# SPU_Rev_2_1.net
KiCad netlist of a schematic drawn in EAGLE
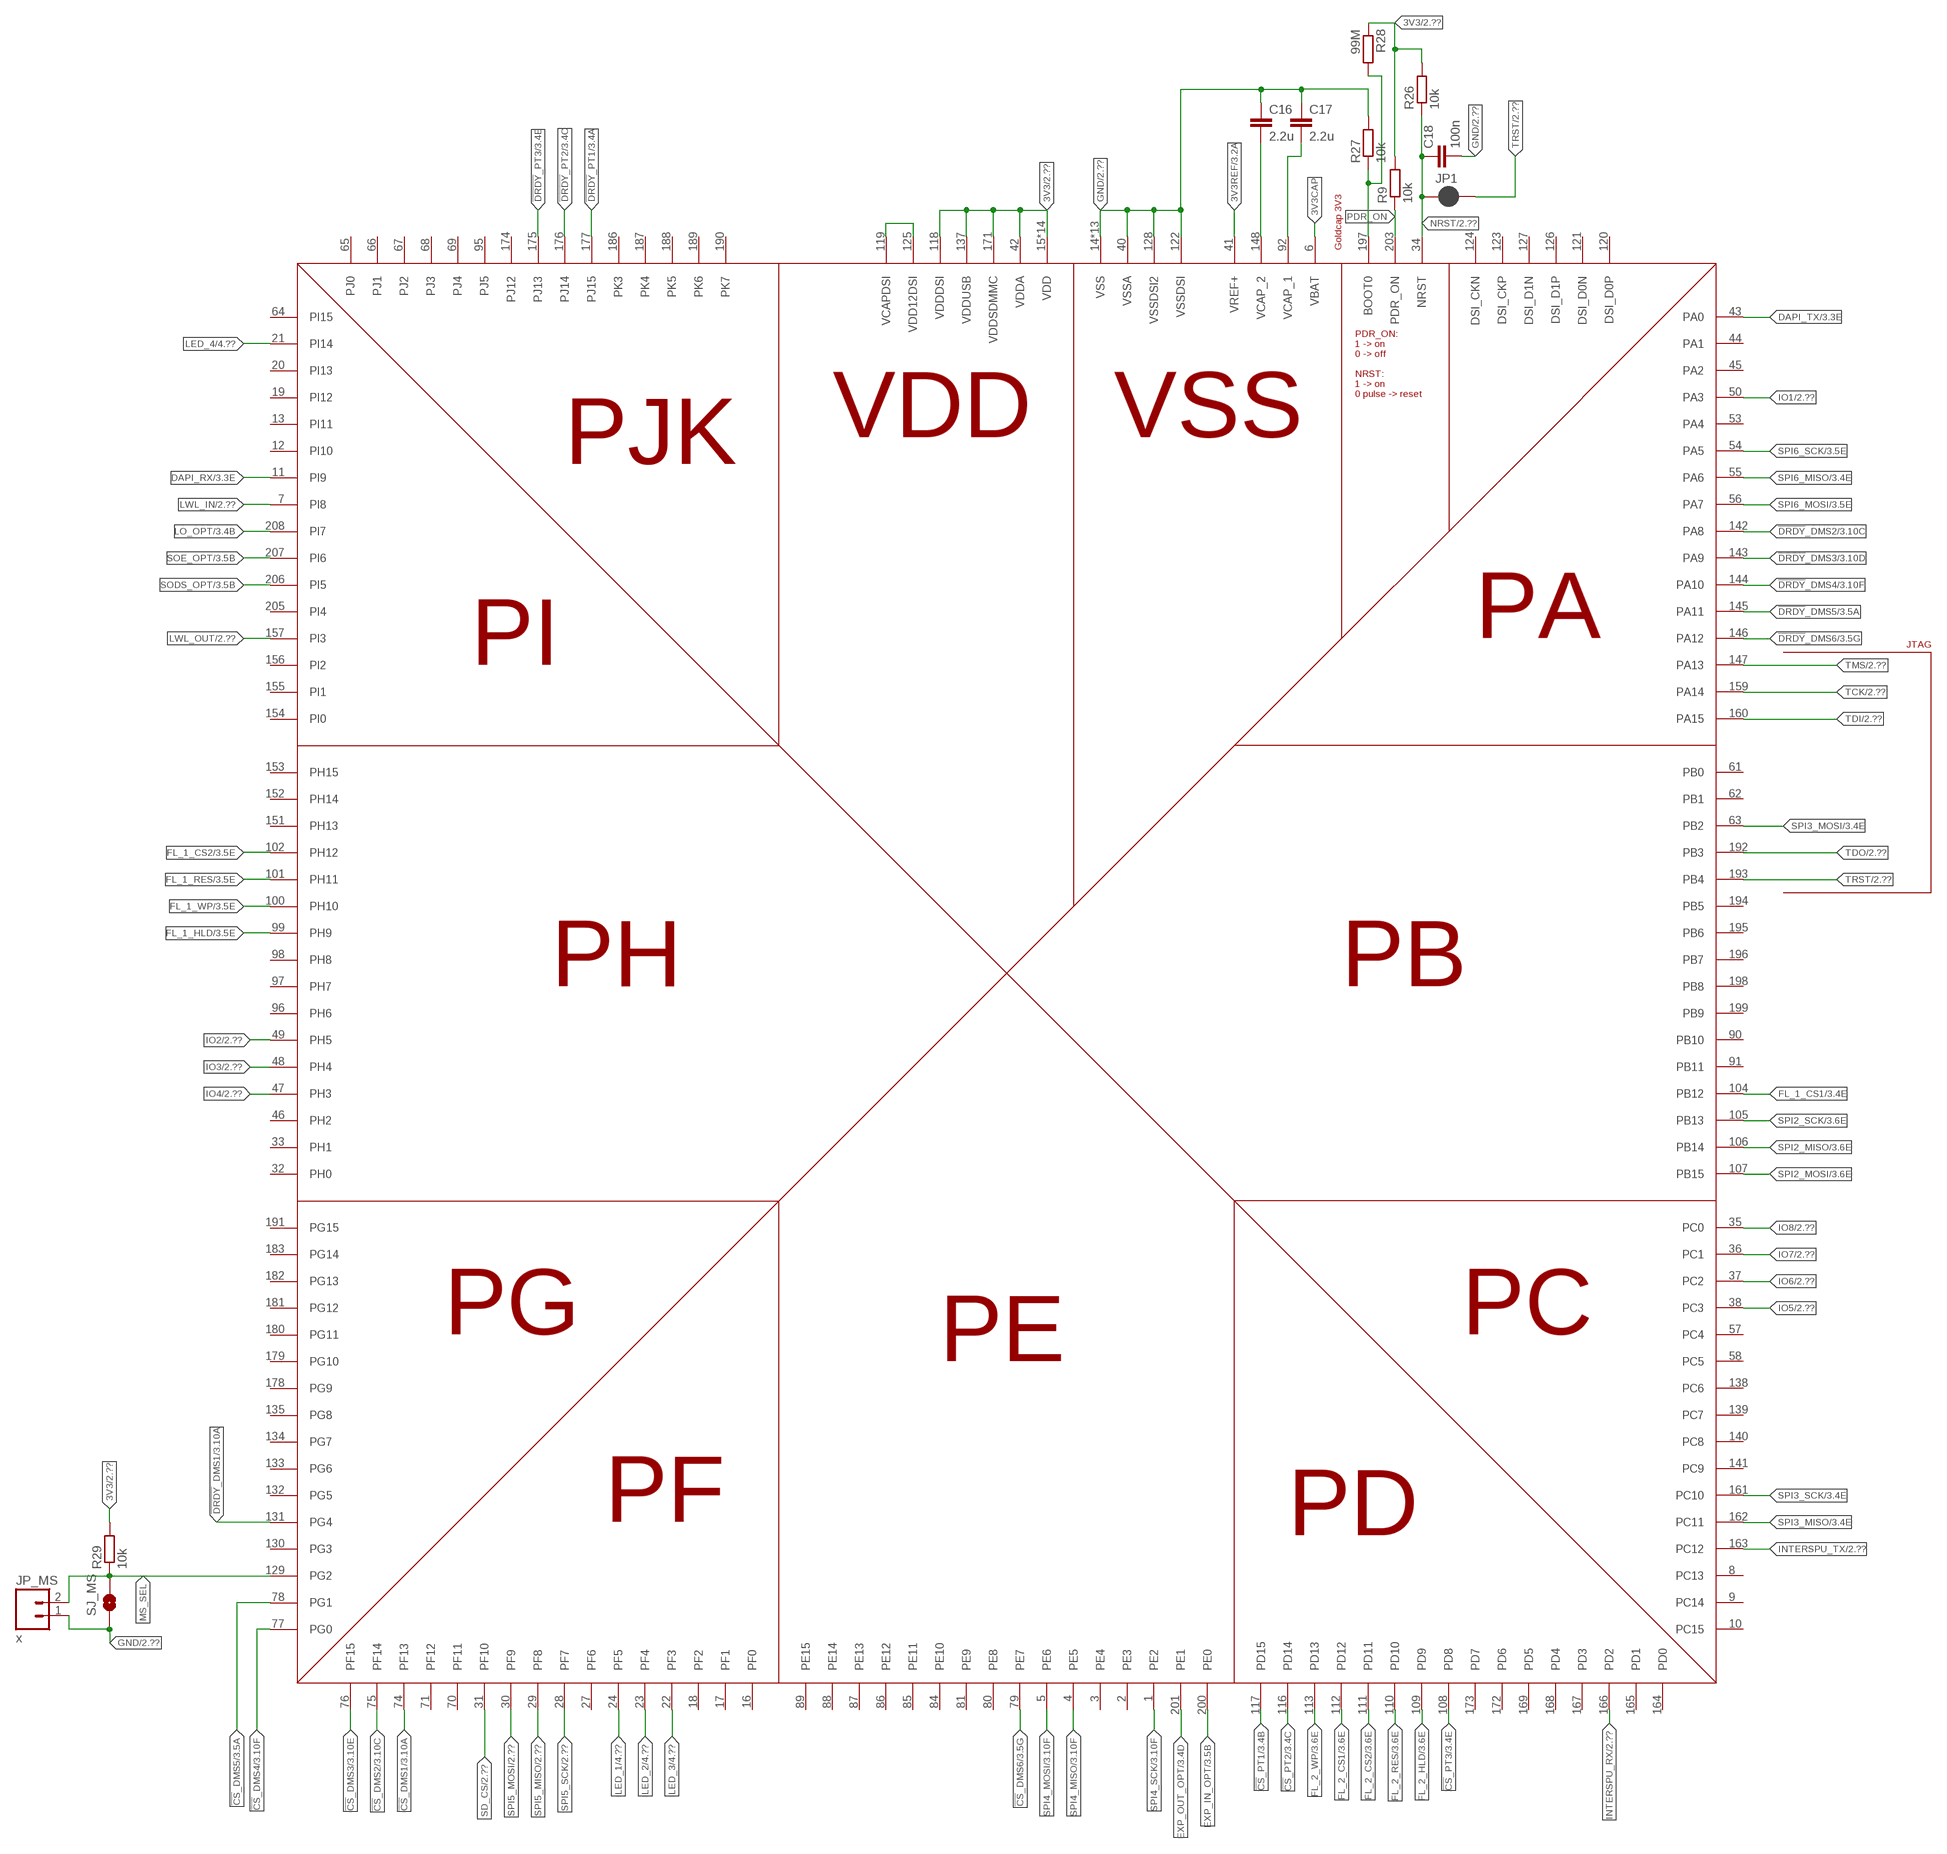
[diagram p0: schematic, sheet 1]
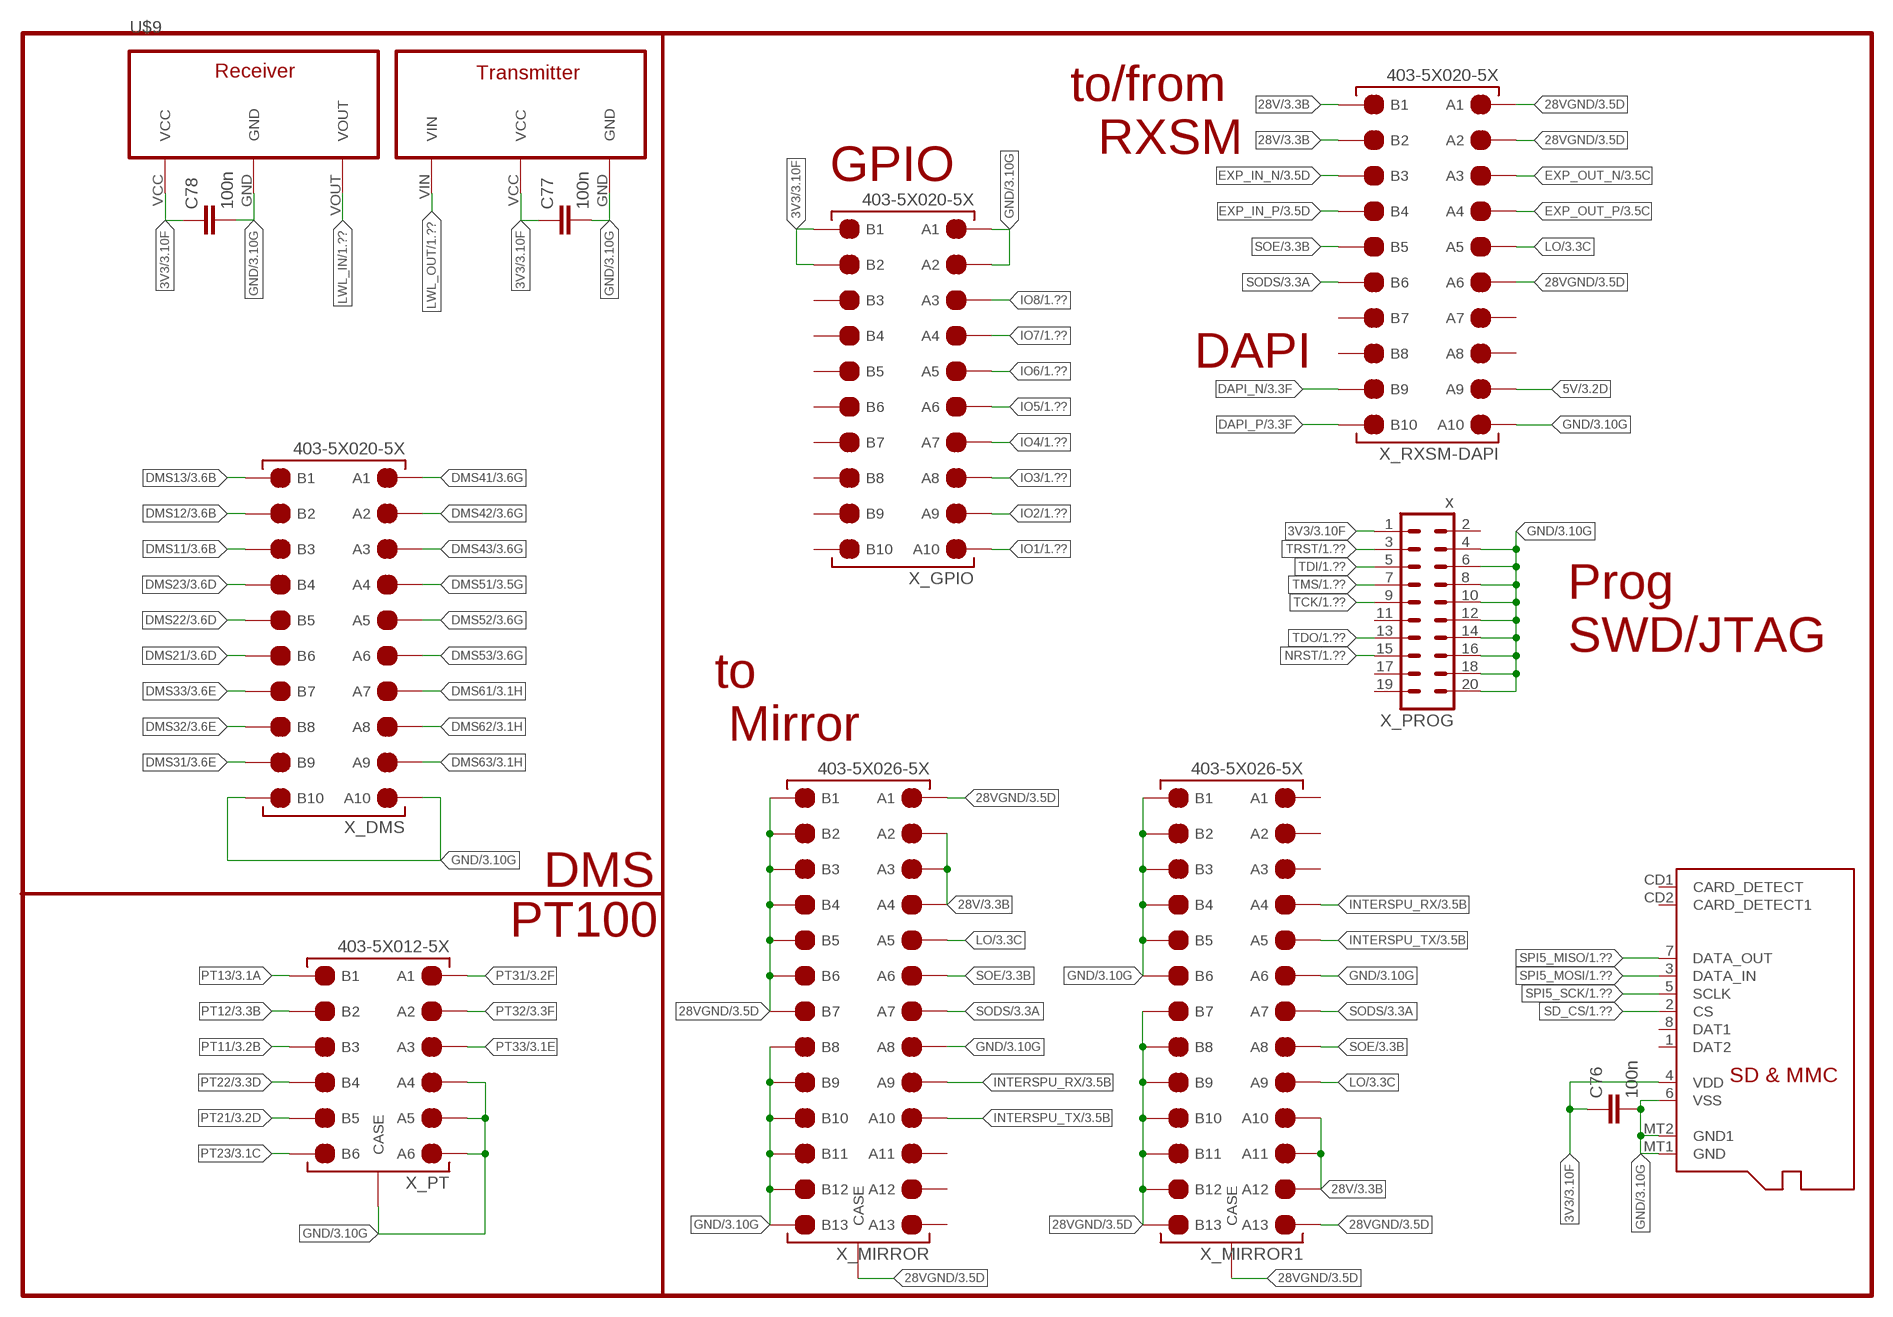
[diagram p1: schematic, sheet 2]
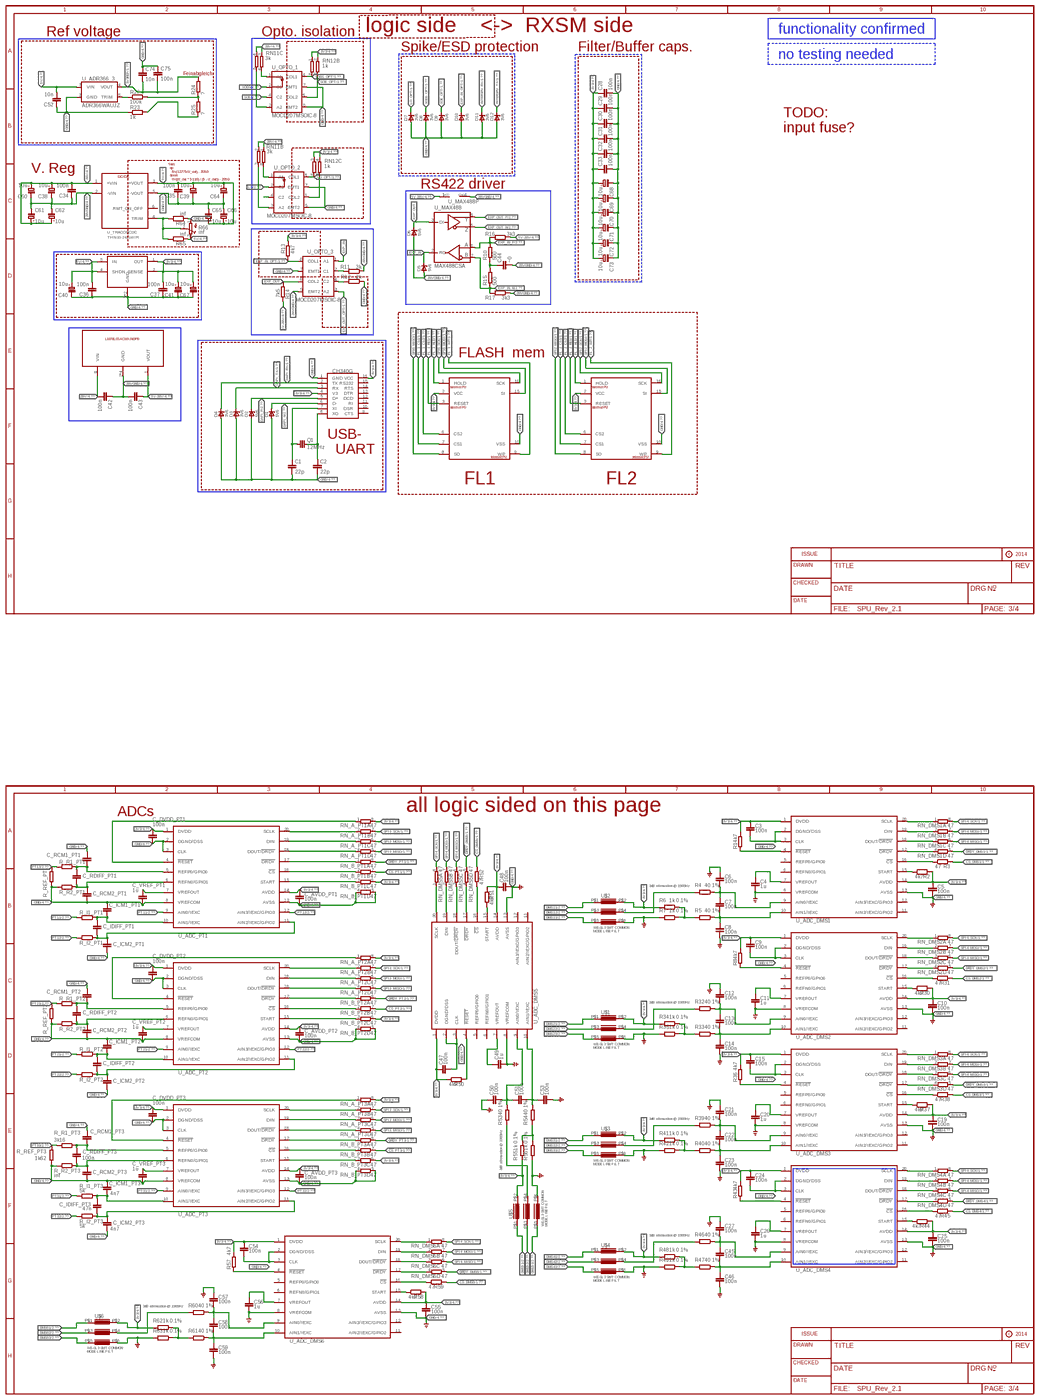
[diagram p2: schematic, sheet 3, overview]
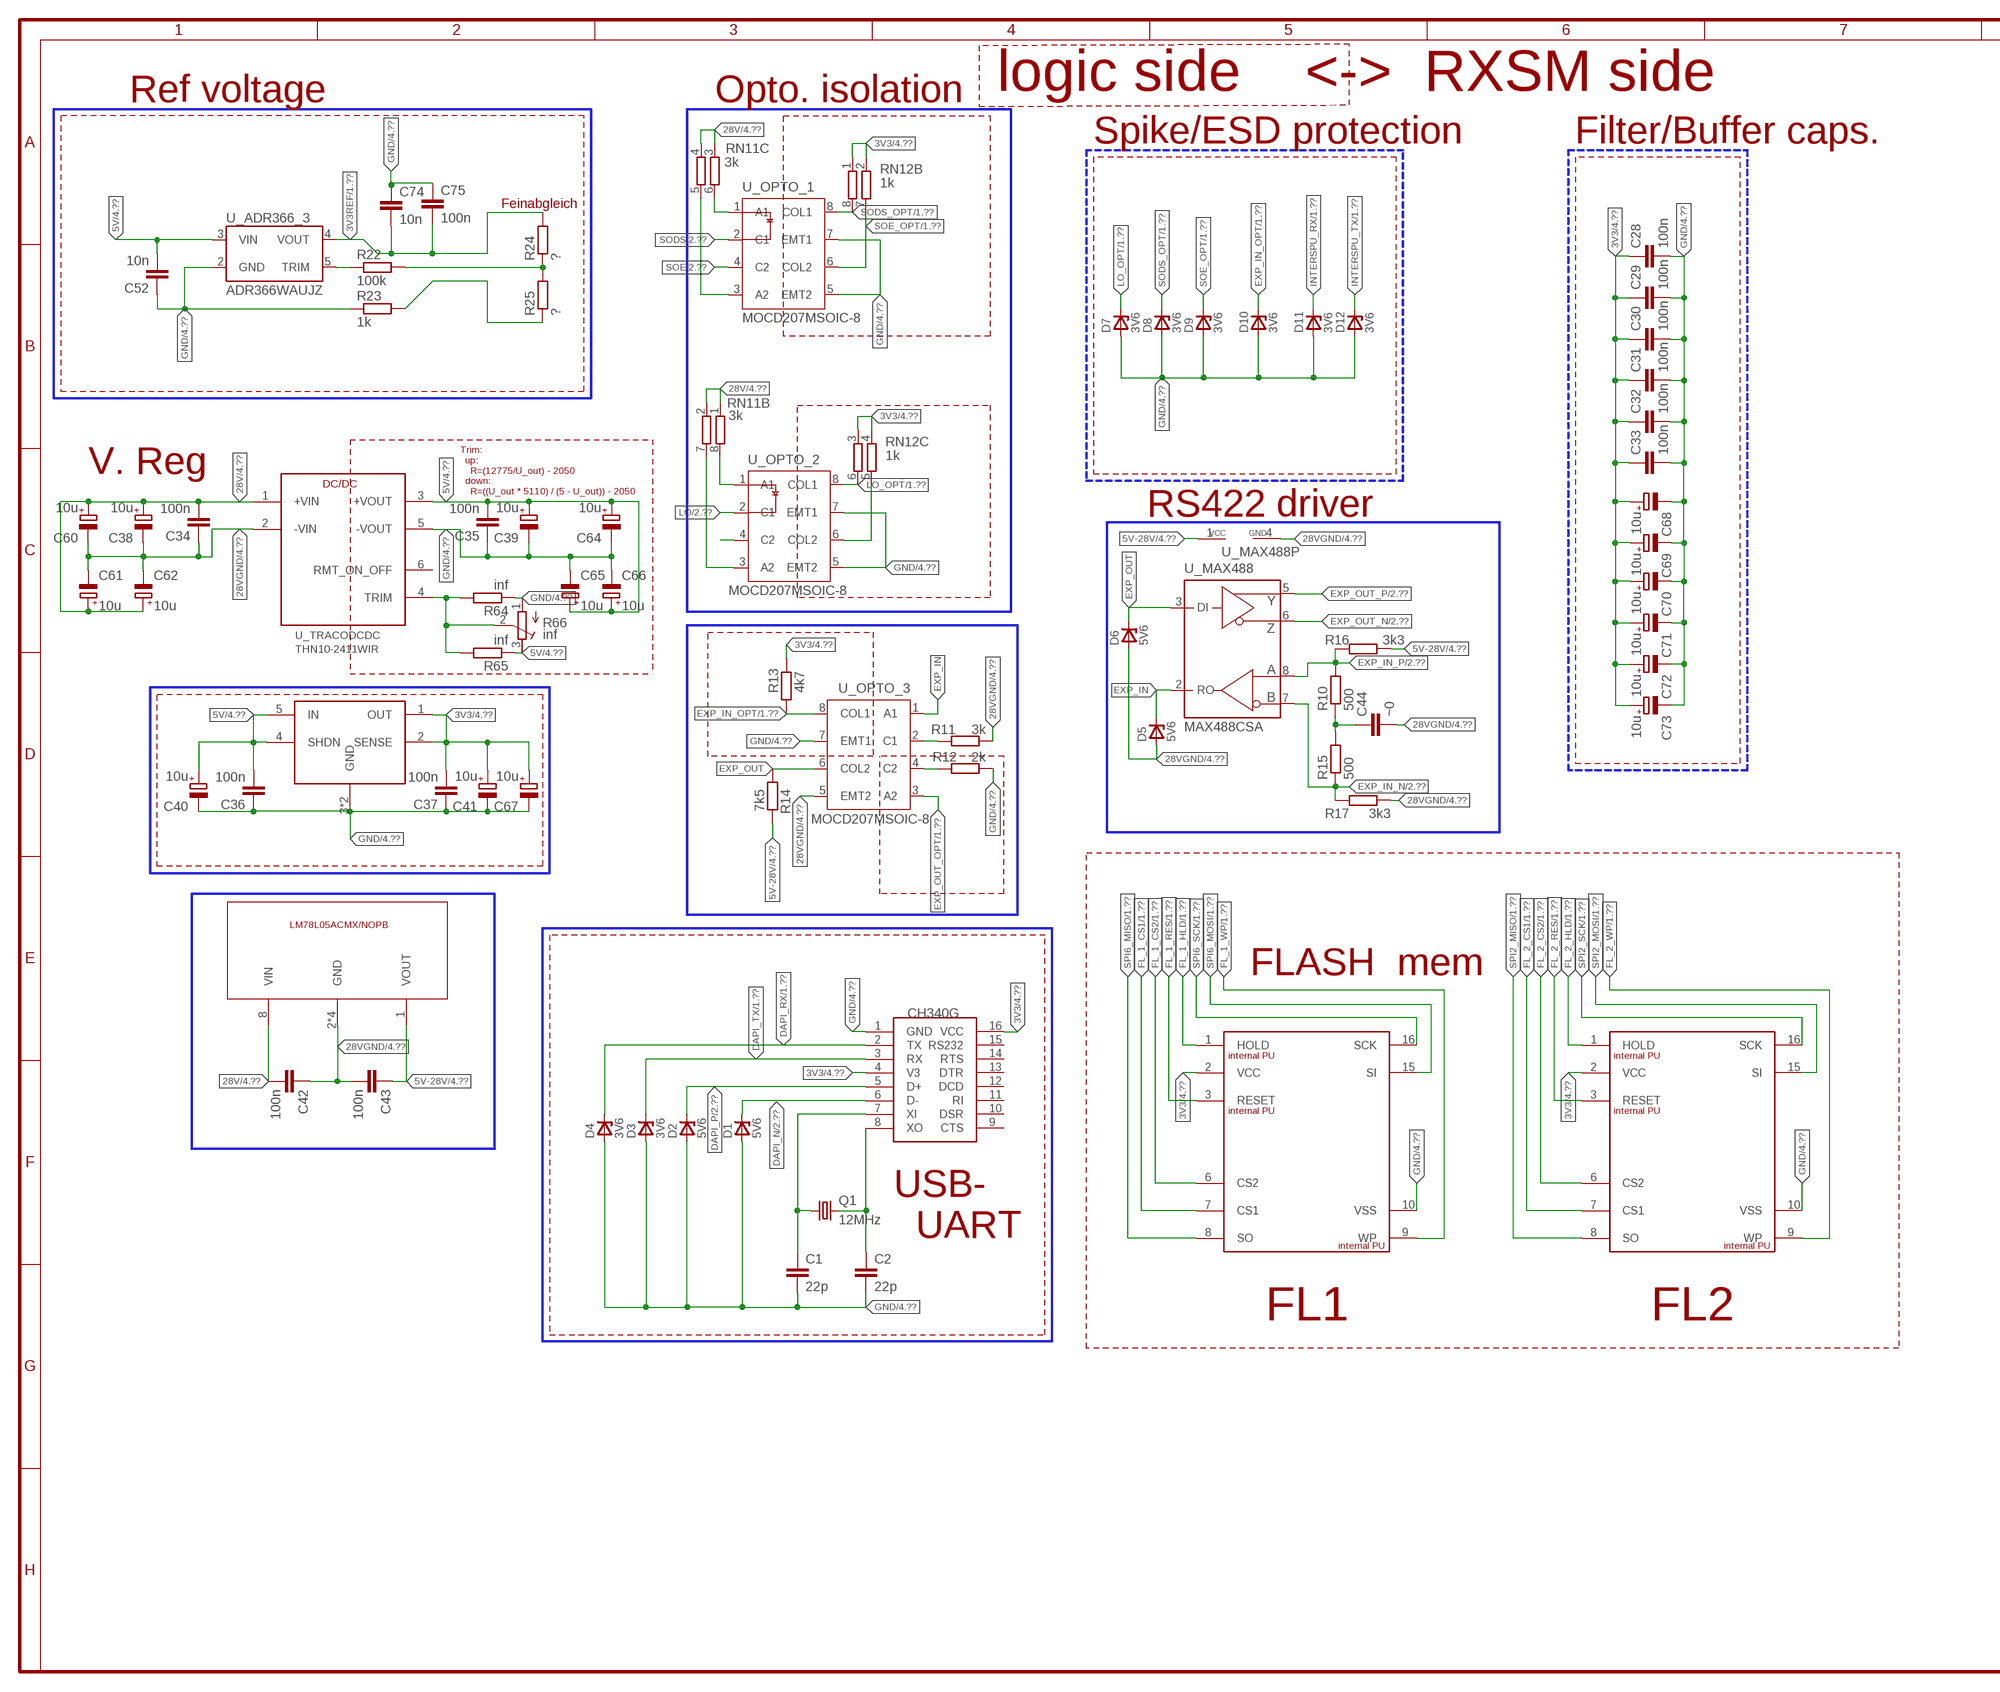
[diagram p3: schematic, sheet 3, part 1 of 4]
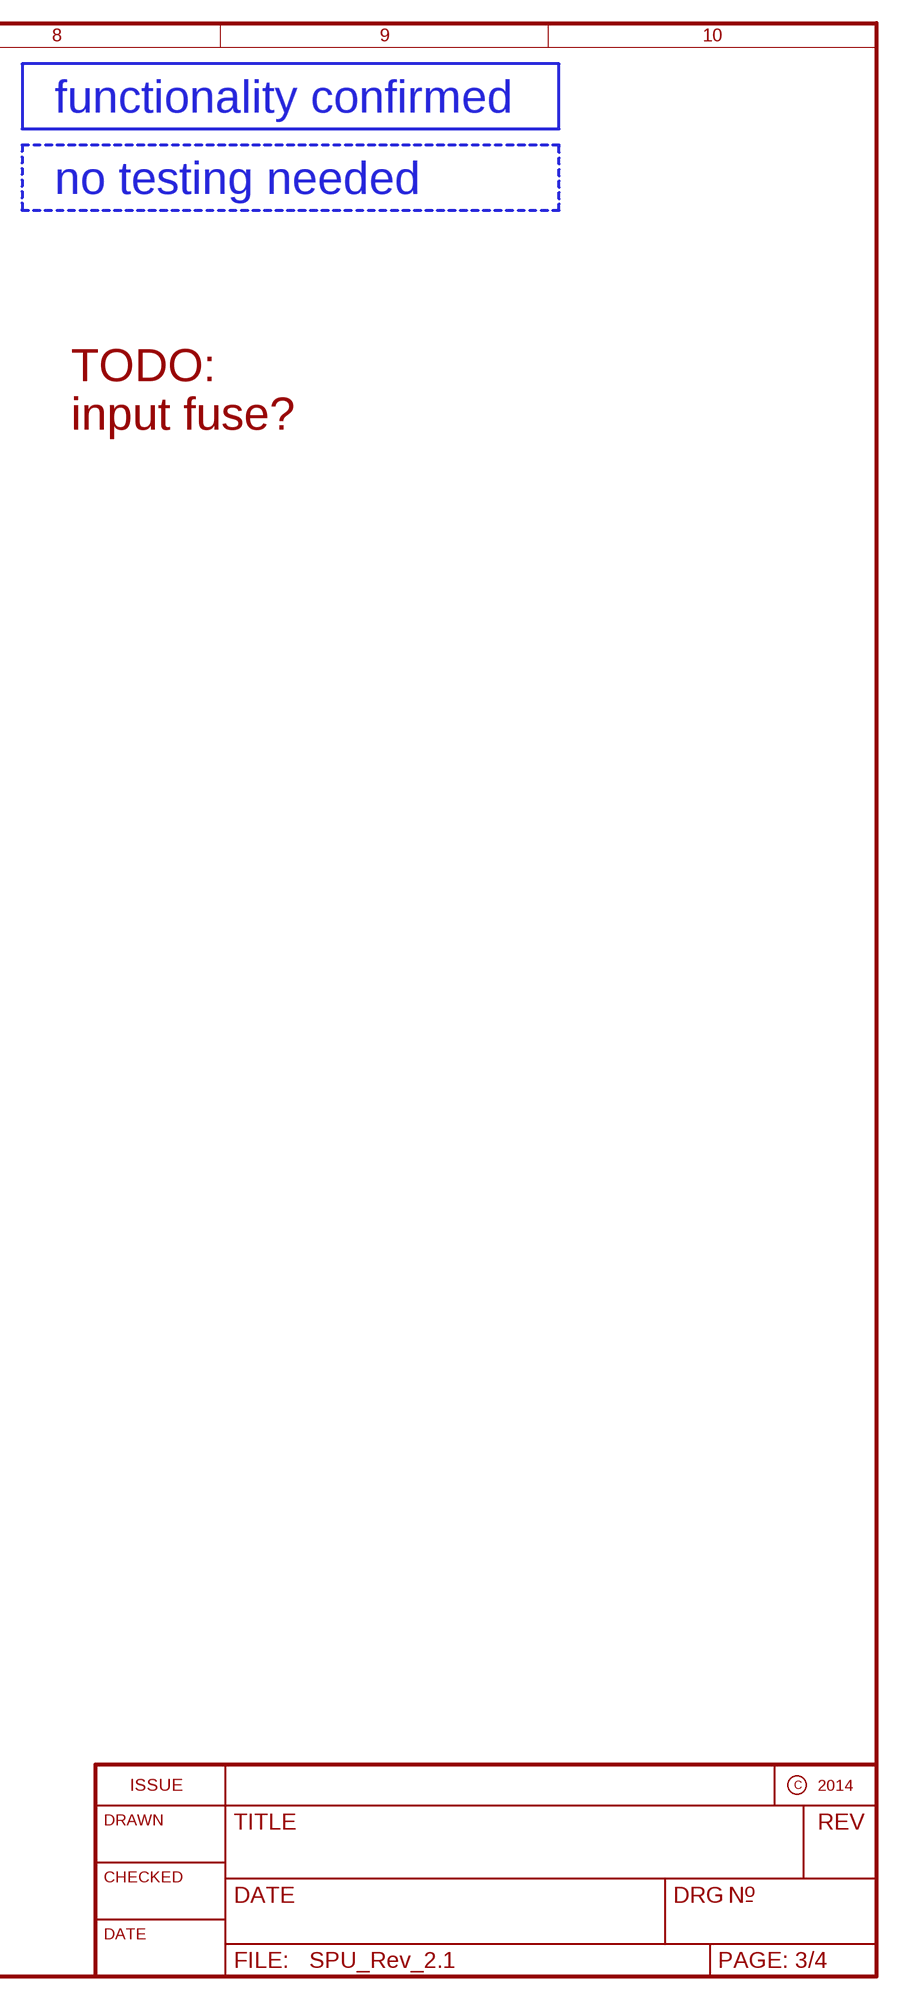
[diagram p4: schematic, sheet 3, part 2 of 4]
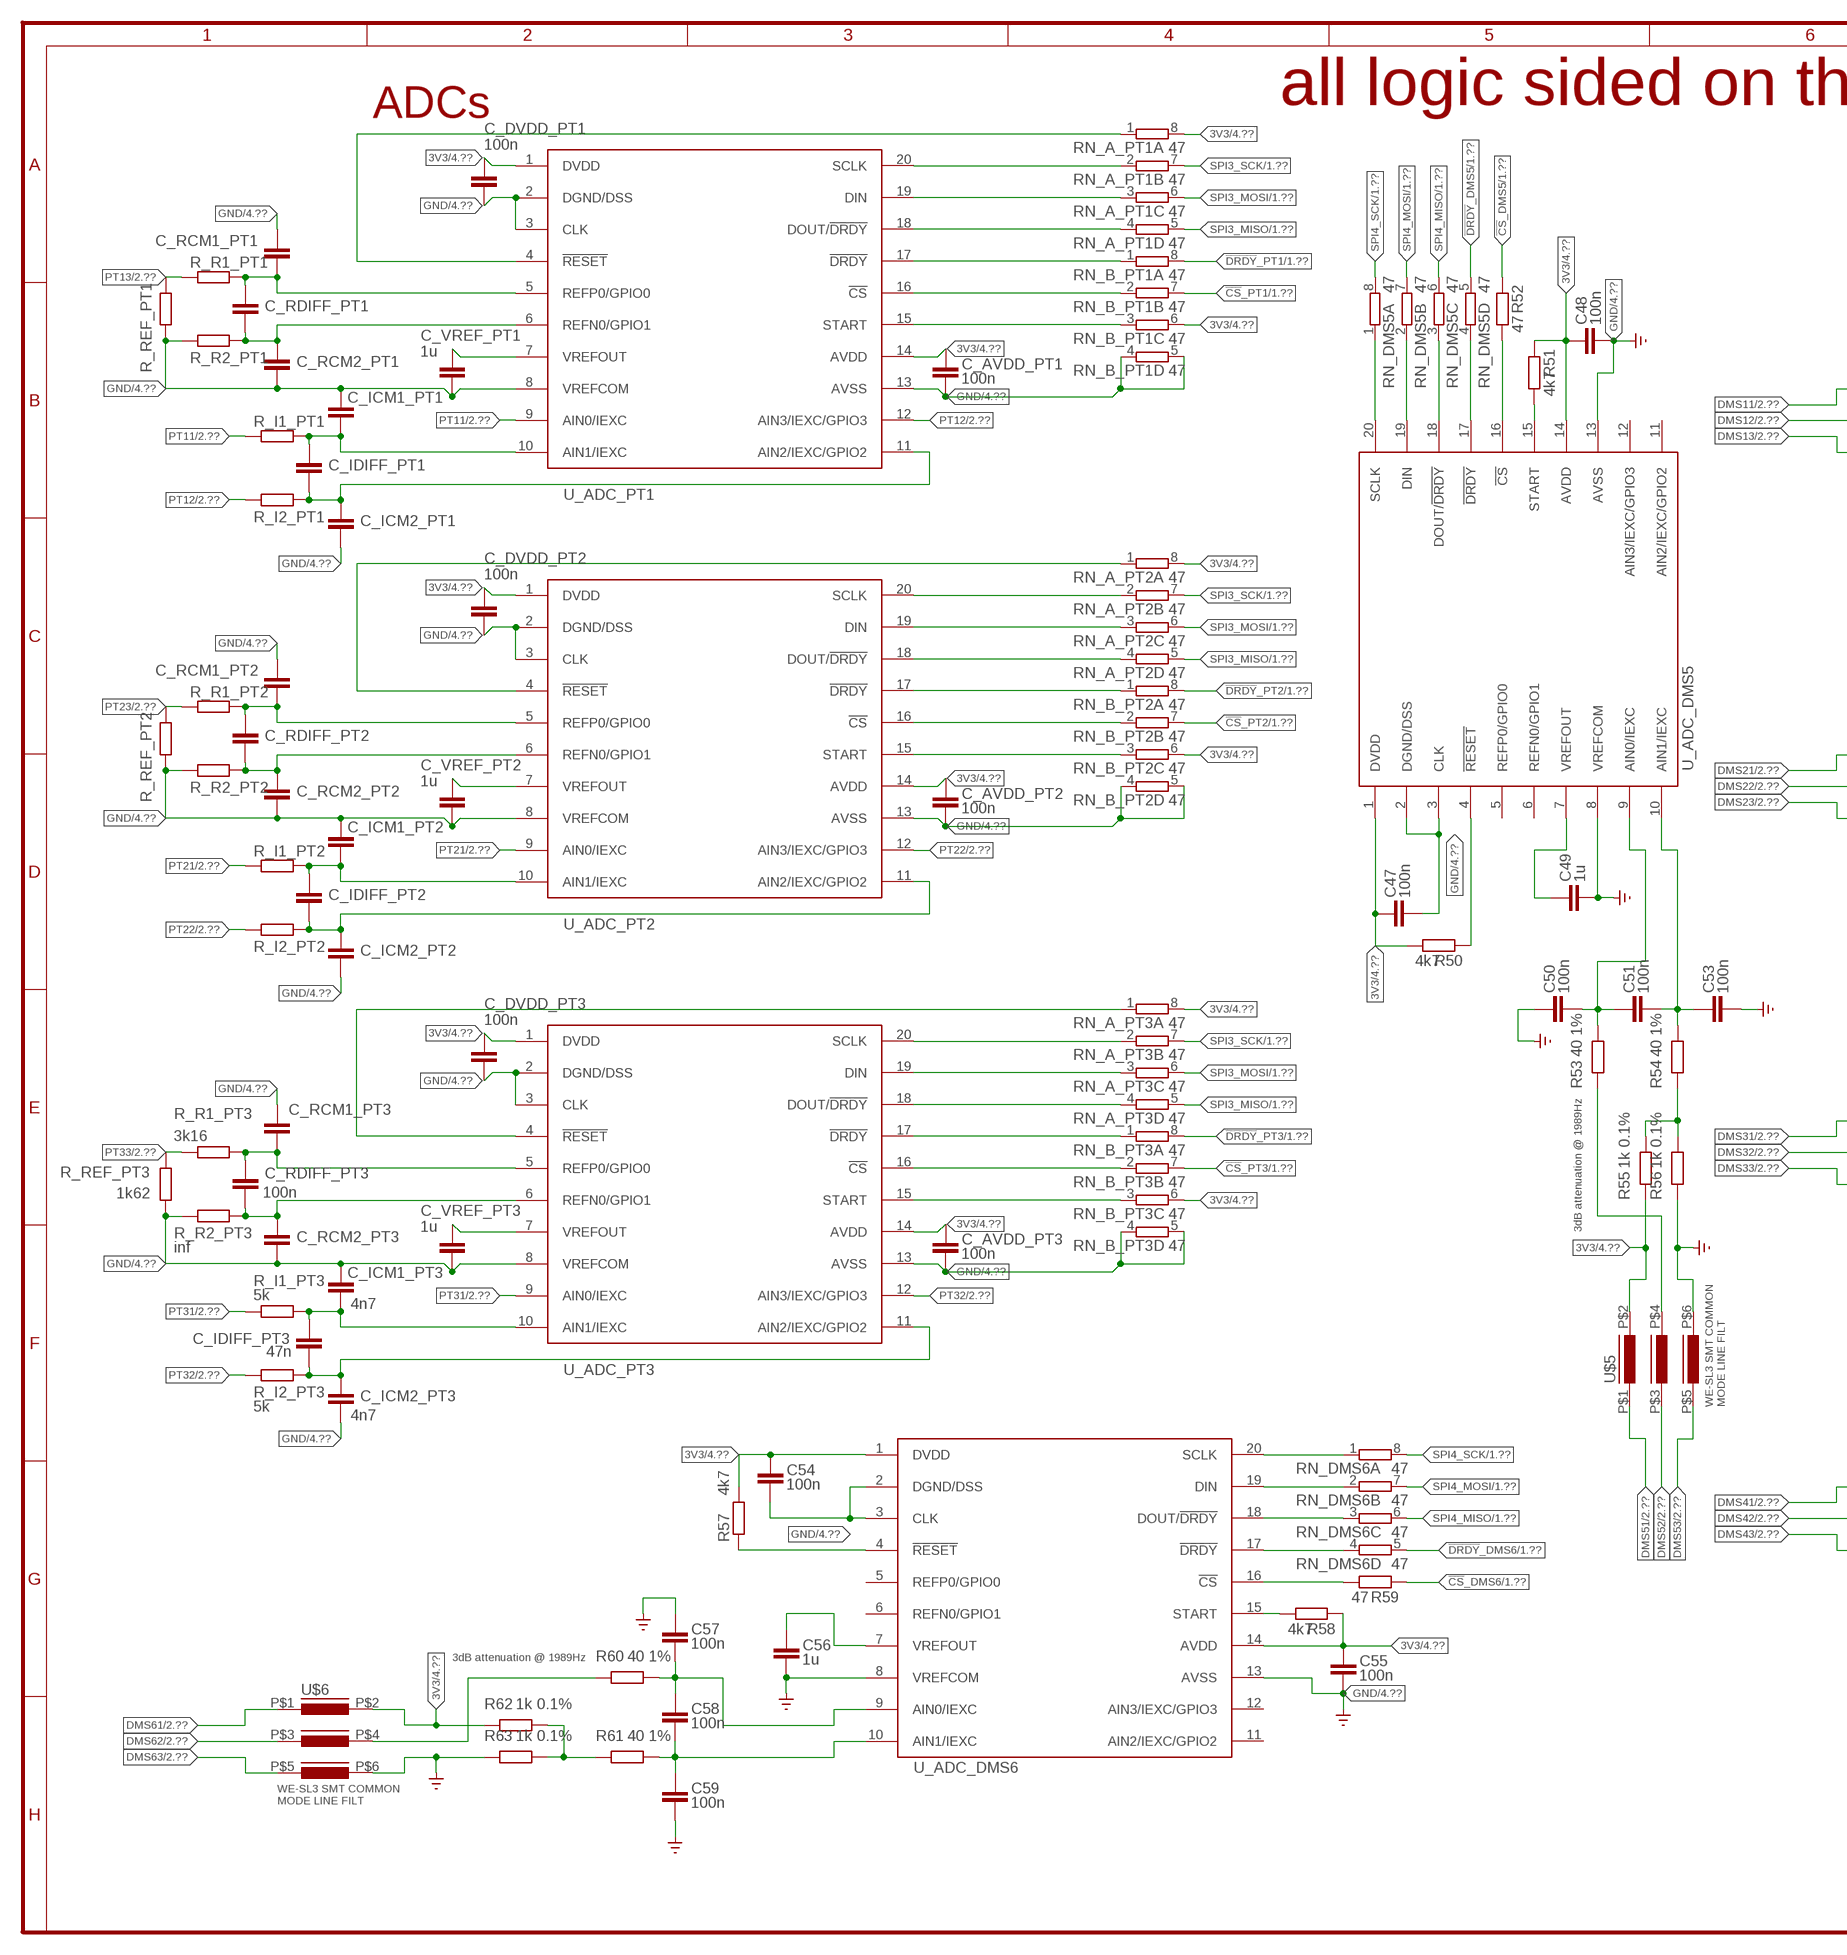
[diagram p5: schematic, sheet 3, part 3 of 4]
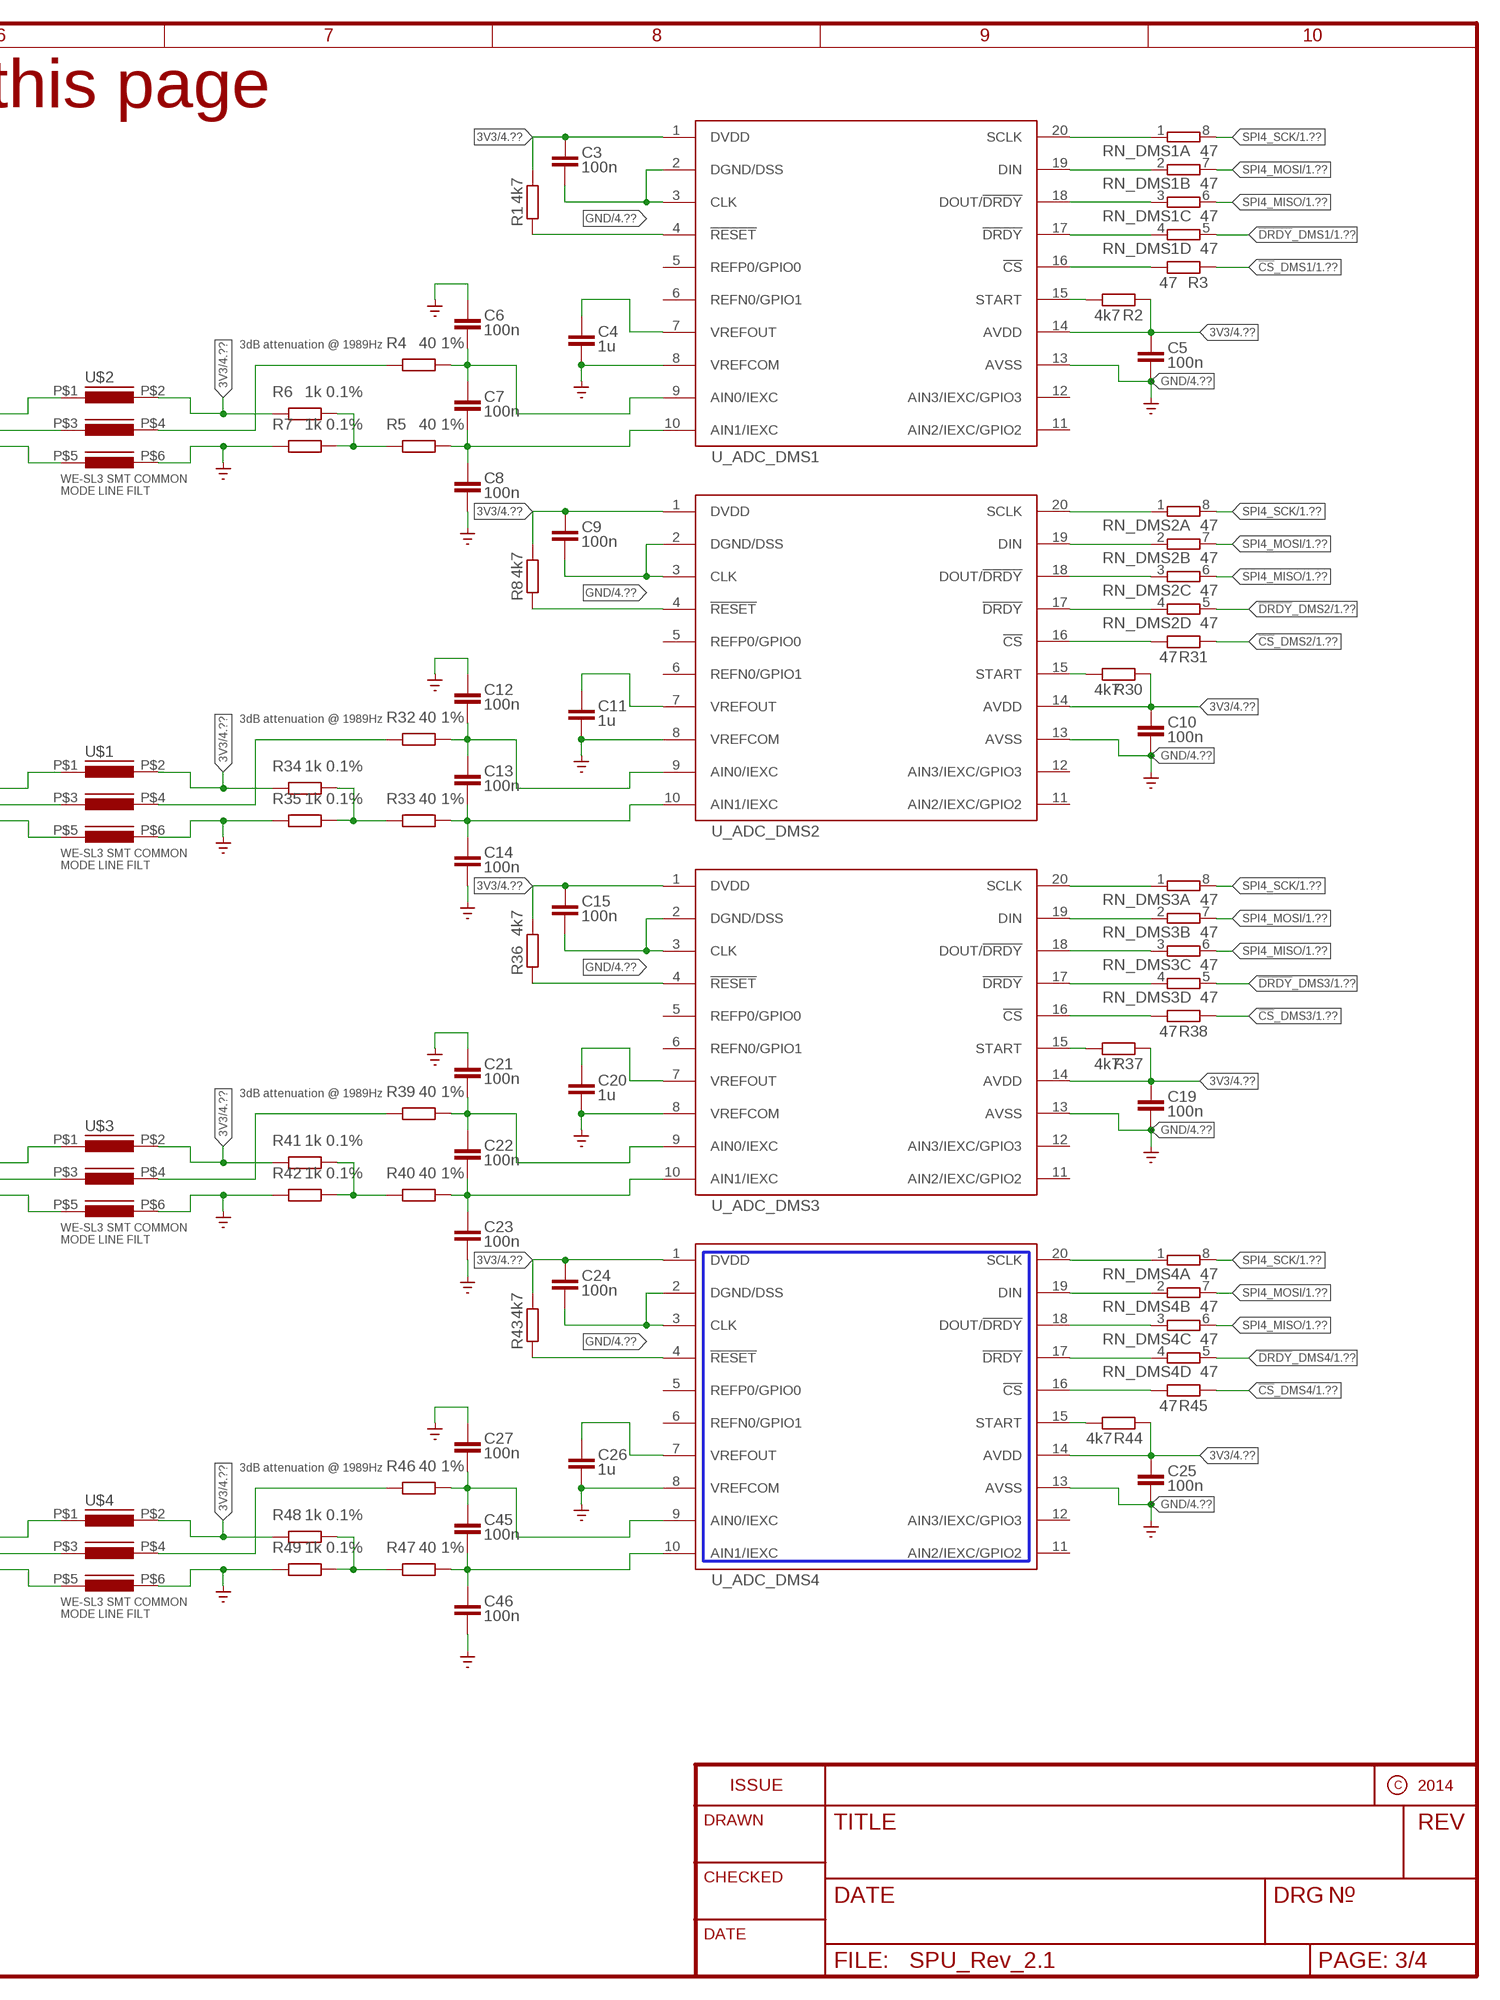
[diagram p6: schematic, sheet 3, part 4 of 4]
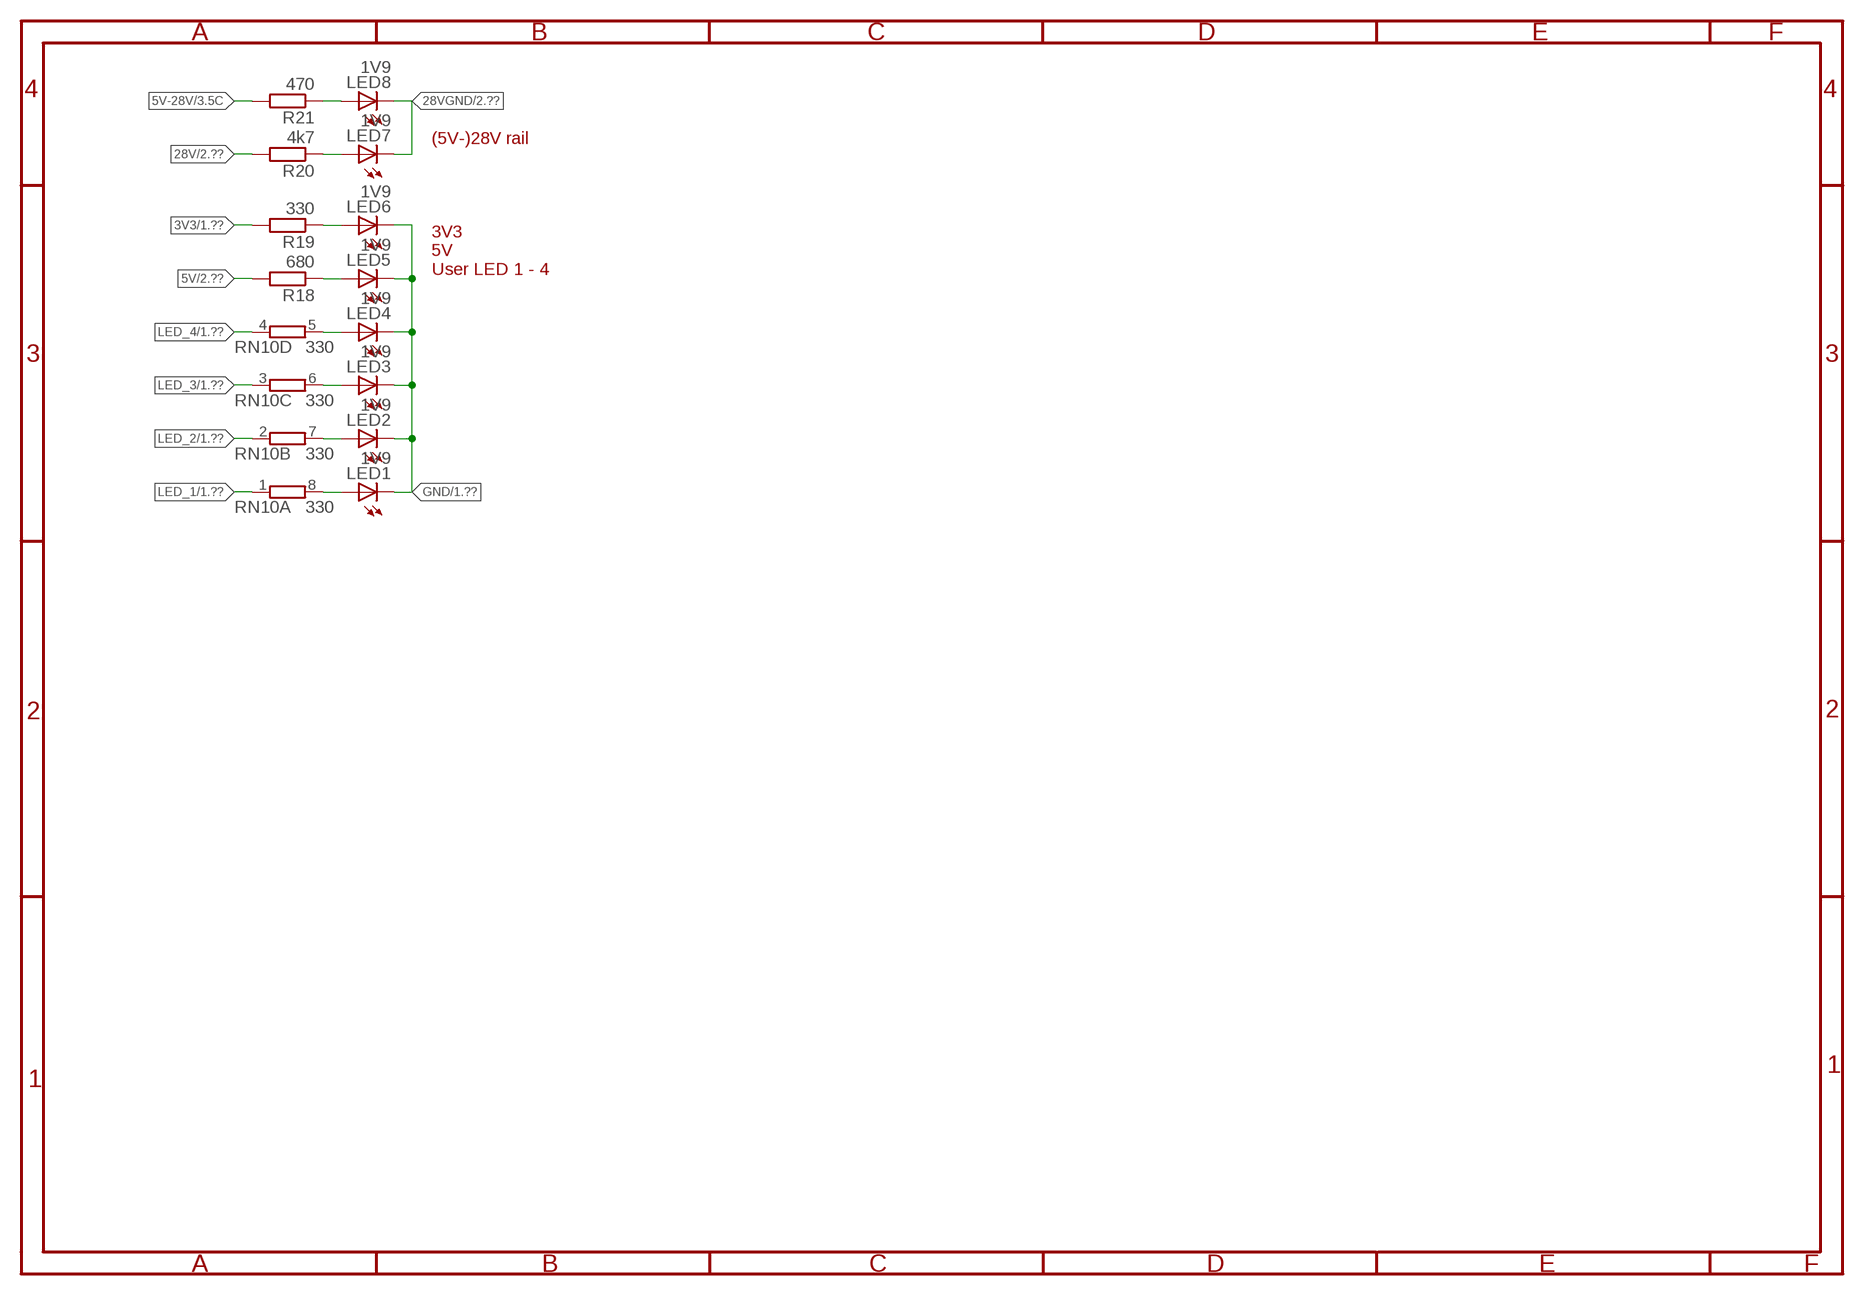
[diagram p7: schematic, sheet 4]

(export (version "E")
  (design (tool "Eeschema 10.0.6"))
  (components
    (comp (ref "C1")
      (value "22p")
      (footprint "eagle-import:C0603")
      (libsource (lib "eagle-import") (part "C-EUC0603"))
    )
    (comp (ref "C2")
      (value "22p")
      (footprint "eagle-import:C0603")
      (libsource (lib "eagle-import") (part "C-EUC0603"))
    )
    (comp (ref "C3")
      (value "100n")
      (footprint "eagle-import:C0603")
      (libsource (lib "eagle-import") (part "rcl_334_C-EUC0603"))
    )
    (comp (ref "C4")
      (value "1u")
      (footprint "eagle-import:C1206")
      (libsource (lib "eagle-import") (part "rcl_334_C-EUC1206"))
    )
    (comp (ref "C5")
      (value "100n")
      (footprint "eagle-import:C0603")
      (libsource (lib "eagle-import") (part "rcl_334_C-EUC0603"))
    )
    (comp (ref "C6")
      (value "100n")
      (footprint "eagle-import:C0603")
      (libsource (lib "eagle-import") (part "rcl_334_C-EUC0603"))
    )
    (comp (ref "C7")
      (value "100n")
      (footprint "eagle-import:C0603")
      (libsource (lib "eagle-import") (part "rcl_334_C-EUC0603"))
    )
    (comp (ref "C8")
      (value "100n")
      (footprint "eagle-import:C0603")
      (libsource (lib "eagle-import") (part "rcl_334_C-EUC0603"))
    )
    (comp (ref "C9")
      (value "100n")
      (footprint "eagle-import:C0603")
      (libsource (lib "eagle-import") (part "rcl_334_C-EUC0603"))
    )
    (comp (ref "C10")
      (value "100n")
      (footprint "eagle-import:C0603")
      (libsource (lib "eagle-import") (part "rcl_334_C-EUC0603"))
    )
    (comp (ref "C11")
      (value "1u")
      (footprint "eagle-import:C1206")
      (libsource (lib "eagle-import") (part "rcl_334_C-EUC1206"))
    )
    (comp (ref "C12")
      (value "100n")
      (footprint "eagle-import:C0603")
      (libsource (lib "eagle-import") (part "rcl_334_C-EUC0603"))
    )
    (comp (ref "C13")
      (value "100n")
      (footprint "eagle-import:C0603")
      (libsource (lib "eagle-import") (part "rcl_334_C-EUC0603"))
    )
    (comp (ref "C14")
      (value "100n")
      (footprint "eagle-import:C0603")
      (libsource (lib "eagle-import") (part "rcl_334_C-EUC0603"))
    )
    (comp (ref "C15")
      (value "100n")
      (footprint "eagle-import:C0603")
      (libsource (lib "eagle-import") (part "rcl_334_C-EUC0603"))
    )
    (comp (ref "C19")
      (value "100n")
      (footprint "eagle-import:C0603")
      (libsource (lib "eagle-import") (part "rcl_334_C-EUC0603"))
    )
    (comp (ref "C20")
      (value "1u")
      (footprint "eagle-import:C1206")
      (libsource (lib "eagle-import") (part "rcl_334_C-EUC1206"))
    )
    (comp (ref "C21")
      (value "100n")
      (footprint "eagle-import:C0603")
      (libsource (lib "eagle-import") (part "rcl_334_C-EUC0603"))
    )
    (comp (ref "C22")
      (value "100n")
      (footprint "eagle-import:C0603")
      (libsource (lib "eagle-import") (part "rcl_334_C-EUC0603"))
    )
    (comp (ref "C23")
      (value "100n")
      (footprint "eagle-import:C0603")
      (libsource (lib "eagle-import") (part "rcl_334_C-EUC0603"))
    )
    (comp (ref "C24")
      (value "100n")
      (footprint "eagle-import:C0603")
      (libsource (lib "eagle-import") (part "rcl_334_C-EUC0603"))
    )
    (comp (ref "C25")
      (value "100n")
      (footprint "eagle-import:C0603")
      (libsource (lib "eagle-import") (part "rcl_334_C-EUC0603"))
    )
    (comp (ref "C26")
      (value "1u")
      (footprint "eagle-import:C1206")
      (libsource (lib "eagle-import") (part "rcl_334_C-EUC1206"))
    )
    (comp (ref "C27")
      (value "100n")
      (footprint "eagle-import:C0603")
      (libsource (lib "eagle-import") (part "rcl_334_C-EUC0603"))
    )
    (comp (ref "C28")
      (value "100n")
      (footprint "eagle-import:C0805")
      (libsource (lib "eagle-import") (part "rcl_334_C-EUC0805"))
    )
    (comp (ref "C29")
      (value "100n")
      (footprint "eagle-import:C0805")
      (libsource (lib "eagle-import") (part "rcl_334_C-EUC0805"))
    )
    (comp (ref "C30")
      (value "100n")
      (footprint "eagle-import:C0805")
      (libsource (lib "eagle-import") (part "rcl_334_C-EUC0805"))
    )
    (comp (ref "C31")
      (value "100n")
      (footprint "eagle-import:C0805")
      (libsource (lib "eagle-import") (part "rcl_334_C-EUC0805"))
    )
    (comp (ref "C32")
      (value "100n")
      (footprint "eagle-import:C0805")
      (libsource (lib "eagle-import") (part "rcl_334_C-EUC0805"))
    )
    (comp (ref "C33")
      (value "100n")
      (footprint "eagle-import:C0805")
      (libsource (lib "eagle-import") (part "rcl_334_C-EUC0805"))
    )
    (comp (ref "C34")
      (value "100n")
      (footprint "eagle-import:C0805")
      (libsource (lib "eagle-import") (part "rcl_334_C-EUC0805"))
    )
    (comp (ref "C35")
      (value "100n")
      (footprint "eagle-import:C0805")
      (libsource (lib "eagle-import") (part "rcl_334_C-EUC0805"))
    )
    (comp (ref "C36")
      (value "100n")
      (footprint "eagle-import:C0805")
      (libsource (lib "eagle-import") (part "rcl_334_C-EUC0805"))
    )
    (comp (ref "C37")
      (value "100n")
      (footprint "eagle-import:C0805")
      (libsource (lib "eagle-import") (part "rcl_334_C-EUC0805"))
    )
    (comp (ref "C38")
      (value "10u")
      (footprint "eagle-import:E_7260-38W")
      (libsource (lib "eagle-import") (part "CPOL-EUE/7260-38W"))
    )
    (comp (ref "C39")
      (value "10u")
      (footprint "eagle-import:E_7260-38W")
      (libsource (lib "eagle-import") (part "CPOL-EUE/7260-38W"))
    )
    (comp (ref "C40")
      (value "10u")
      (footprint "eagle-import:E_7260-38W")
      (libsource (lib "eagle-import") (part "CPOL-EUE/7260-38W"))
    )
    (comp (ref "C41")
      (value "10u")
      (footprint "eagle-import:E_7260-38W")
      (libsource (lib "eagle-import") (part "CPOL-EUE/7260-38W"))
    )
    (comp (ref "C42")
      (value "100n")
      (footprint "eagle-import:C0805")
      (libsource (lib "eagle-import") (part "rcl_334_C-EUC0805"))
    )
    (comp (ref "C43")
      (value "100n")
      (footprint "eagle-import:C0805")
      (libsource (lib "eagle-import") (part "rcl_334_C-EUC0805"))
    )
    (comp (ref "C44")
      (value "~0")
      (footprint "eagle-import:C0805")
      (libsource (lib "eagle-import") (part "rcl_334_C-EUC0805"))
    )
    (comp (ref "C45")
      (value "100n")
      (footprint "eagle-import:C0603")
      (libsource (lib "eagle-import") (part "rcl_334_C-EUC0603"))
    )
    (comp (ref "C46")
      (value "100n")
      (footprint "eagle-import:C0603")
      (libsource (lib "eagle-import") (part "rcl_334_C-EUC0603"))
    )
    (comp (ref "C47")
      (value "100n")
      (footprint "eagle-import:C0603")
      (libsource (lib "eagle-import") (part "rcl_334_C-EUC0603"))
    )
    (comp (ref "C48")
      (value "100n")
      (footprint "eagle-import:C0603")
      (libsource (lib "eagle-import") (part "rcl_334_C-EUC0603"))
    )
    (comp (ref "C49")
      (value "1u")
      (footprint "eagle-import:C1206")
      (libsource (lib "eagle-import") (part "rcl_334_C-EUC1206"))
    )
    (comp (ref "C50")
      (value "100n")
      (footprint "eagle-import:C0603")
      (libsource (lib "eagle-import") (part "rcl_334_C-EUC0603"))
    )
    (comp (ref "C51")
      (value "100n")
      (footprint "eagle-import:C0603")
      (libsource (lib "eagle-import") (part "rcl_334_C-EUC0603"))
    )
    (comp (ref "C52")
      (value "10n")
      (footprint "eagle-import:C0805")
      (libsource (lib "eagle-import") (part "rcl_334_C-EUC0805"))
    )
    (comp (ref "C53")
      (value "100n")
      (footprint "eagle-import:C0603")
      (libsource (lib "eagle-import") (part "rcl_334_C-EUC0603"))
    )
    (comp (ref "C54")
      (value "100n")
      (footprint "eagle-import:C0603")
      (libsource (lib "eagle-import") (part "rcl_334_C-EUC0603"))
    )
    (comp (ref "C55")
      (value "100n")
      (footprint "eagle-import:C0603")
      (libsource (lib "eagle-import") (part "rcl_334_C-EUC0603"))
    )
    (comp (ref "C56")
      (value "1u")
      (footprint "eagle-import:C1206")
      (libsource (lib "eagle-import") (part "rcl_334_C-EUC1206"))
    )
    (comp (ref "C57")
      (value "100n")
      (footprint "eagle-import:C0603")
      (libsource (lib "eagle-import") (part "rcl_334_C-EUC0603"))
    )
    (comp (ref "C58")
      (value "100n")
      (footprint "eagle-import:C0603")
      (libsource (lib "eagle-import") (part "rcl_334_C-EUC0603"))
    )
    (comp (ref "C59")
      (value "100n")
      (footprint "eagle-import:C0603")
      (libsource (lib "eagle-import") (part "rcl_334_C-EUC0603"))
    )
    (comp (ref "C60")
      (value "10u")
      (footprint "eagle-import:E_7260-38W")
      (libsource (lib "eagle-import") (part "CPOL-EUE/7260-38W"))
    )
    (comp (ref "C61")
      (value "10u")
      (footprint "eagle-import:E_7260-38W")
      (libsource (lib "eagle-import") (part "CPOL-EUE/7260-38W"))
    )
    (comp (ref "C62")
      (value "10u")
      (footprint "eagle-import:E_7260-38W")
      (libsource (lib "eagle-import") (part "CPOL-EUE/7260-38W"))
    )
    (comp (ref "C64")
      (value "10u")
      (footprint "eagle-import:E_7260-38W")
      (libsource (lib "eagle-import") (part "CPOL-EUE/7260-38W"))
    )
    (comp (ref "C65")
      (value "10u")
      (footprint "eagle-import:E_7260-38W")
      (libsource (lib "eagle-import") (part "CPOL-EUE/7260-38W"))
    )
    (comp (ref "C66")
      (value "10u")
      (footprint "eagle-import:E_7260-38W")
      (libsource (lib "eagle-import") (part "CPOL-EUE/7260-38W"))
    )
    (comp (ref "C67")
      (value "10u")
      (footprint "eagle-import:E_7260-38W")
      (libsource (lib "eagle-import") (part "CPOL-EUE/7260-38W"))
    )
    (comp (ref "C68")
      (value "10u")
      (footprint "eagle-import:E_7260-38W")
      (libsource (lib "eagle-import") (part "CPOL-EUE/7260-38W"))
    )
    (comp (ref "C69")
      (value "10u")
      (footprint "eagle-import:E_7260-38W")
      (libsource (lib "eagle-import") (part "CPOL-EUE/7260-38W"))
    )
    (comp (ref "C70")
      (value "10u")
      (footprint "eagle-import:E_7260-38W")
      (libsource (lib "eagle-import") (part "CPOL-EUE/7260-38W"))
    )
    (comp (ref "C71")
      (value "10u")
      (footprint "eagle-import:E_7260-38W")
      (libsource (lib "eagle-import") (part "CPOL-EUE/7260-38W"))
    )
    (comp (ref "C72")
      (value "10u")
      (footprint "eagle-import:E_7260-38W")
      (libsource (lib "eagle-import") (part "CPOL-EUE/7260-38W"))
    )
    (comp (ref "C73")
      (value "10u")
      (footprint "eagle-import:E_7260-38W")
      (libsource (lib "eagle-import") (part "CPOL-EUE/7260-38W"))
    )
    (comp (ref "C74")
      (value "10n")
      (footprint "eagle-import:C0805")
      (libsource (lib "eagle-import") (part "rcl_334_C-EUC0805"))
    )
    (comp (ref "C75")
      (value "100n")
      (footprint "eagle-import:C0805")
      (libsource (lib "eagle-import") (part "rcl_334_C-EUC0805"))
    )
    (comp (ref "C_AVDD_PT1")
      (value "100n")
      (footprint "eagle-import:C0603")
      (libsource (lib "eagle-import") (part "rcl_334_C-EUC0603"))
    )
    (comp (ref "C_AVDD_PT2")
      (value "100n")
      (footprint "eagle-import:C0603")
      (libsource (lib "eagle-import") (part "rcl_334_C-EUC0603"))
    )
    (comp (ref "C_AVDD_PT3")
      (value "100n")
      (footprint "eagle-import:C0603")
      (libsource (lib "eagle-import") (part "rcl_334_C-EUC0603"))
    )
    (comp (ref "C_DVDD_PT1")
      (value "100n")
      (footprint "eagle-import:C0603")
      (libsource (lib "eagle-import") (part "rcl_334_C-EUC0603"))
    )
    (comp (ref "C_DVDD_PT2")
      (value "100n")
      (footprint "eagle-import:C0603")
      (libsource (lib "eagle-import") (part "rcl_334_C-EUC0603"))
    )
    (comp (ref "C_DVDD_PT3")
      (value "100n")
      (footprint "eagle-import:C0603")
      (libsource (lib "eagle-import") (part "rcl_334_C-EUC0603"))
    )
    (comp (ref "C_ICM1_PT1")
      (value "C-EUC0603")
      (footprint "eagle-import:C0603")
      (libsource (lib "eagle-import") (part "rcl_334_C-EUC0603"))
    )
    (comp (ref "C_ICM1_PT2")
      (value "C-EUC0603")
      (footprint "eagle-import:C0603")
      (libsource (lib "eagle-import") (part "rcl_334_C-EUC0603"))
    )
    (comp (ref "C_ICM1_PT3")
      (value "4n7")
      (footprint "eagle-import:C0603")
      (libsource (lib "eagle-import") (part "rcl_334_C-EUC0603"))
    )
    (comp (ref "C_ICM2_PT1")
      (value "C-EUC0603")
      (footprint "eagle-import:C0603")
      (libsource (lib "eagle-import") (part "rcl_334_C-EUC0603"))
    )
    (comp (ref "C_ICM2_PT2")
      (value "C-EUC0603")
      (footprint "eagle-import:C0603")
      (libsource (lib "eagle-import") (part "rcl_334_C-EUC0603"))
    )
    (comp (ref "C_ICM2_PT3")
      (value "4n7")
      (footprint "eagle-import:C0603")
      (libsource (lib "eagle-import") (part "rcl_334_C-EUC0603"))
    )
    (comp (ref "C_IDIFF_PT1")
      (value "C-EUC0603")
      (footprint "eagle-import:C0603")
      (libsource (lib "eagle-import") (part "rcl_334_C-EUC0603"))
    )
    (comp (ref "C_IDIFF_PT2")
      (value "C-EUC0603")
      (footprint "eagle-import:C0603")
      (libsource (lib "eagle-import") (part "rcl_334_C-EUC0603"))
    )
    (comp (ref "C_IDIFF_PT3")
      (value "47n")
      (footprint "eagle-import:C0603")
      (libsource (lib "eagle-import") (part "rcl_334_C-EUC0603"))
    )
    (comp (ref "C_RCM1_PT1")
      (value "C-EUC0603")
      (footprint "eagle-import:C0603")
      (libsource (lib "eagle-import") (part "rcl_334_C-EUC0603"))
    )
    (comp (ref "C_RCM1_PT2")
      (value "C-EUC0603")
      (footprint "eagle-import:C0603")
      (libsource (lib "eagle-import") (part "rcl_334_C-EUC0603"))
    )
    (comp (ref "C_RCM1_PT3")
      (value "C-EUC0603")
      (footprint "eagle-import:C0603")
      (libsource (lib "eagle-import") (part "rcl_334_C-EUC0603"))
    )
    (comp (ref "C_RCM2_PT1")
      (value "C-EUC0603")
      (footprint "eagle-import:C0603")
      (libsource (lib "eagle-import") (part "rcl_334_C-EUC0603"))
    )
    (comp (ref "C_RCM2_PT2")
      (value "C-EUC0603")
      (footprint "eagle-import:C0603")
      (libsource (lib "eagle-import") (part "rcl_334_C-EUC0603"))
    )
    (comp (ref "C_RCM2_PT3")
      (value "C-EUC0603")
      (footprint "eagle-import:C0603")
      (libsource (lib "eagle-import") (part "rcl_334_C-EUC0603"))
    )
    (comp (ref "C_RDIFF_PT1")
      (value "C-EUC0603")
      (footprint "eagle-import:C0603")
      (libsource (lib "eagle-import") (part "rcl_334_C-EUC0603"))
    )
    (comp (ref "C_RDIFF_PT2")
      (value "C-EUC0603")
      (footprint "eagle-import:C0603")
      (libsource (lib "eagle-import") (part "rcl_334_C-EUC0603"))
    )
    (comp (ref "C_RDIFF_PT3")
      (value "100n")
      (footprint "eagle-import:C0603")
      (libsource (lib "eagle-import") (part "rcl_334_C-EUC0603"))
    )
    (comp (ref "C_VREF_PT1")
      (value "1u")
      (footprint "eagle-import:C0603")
      (libsource (lib "eagle-import") (part "rcl_334_C-EUC0603"))
    )
    (comp (ref "C_VREF_PT2")
      (value "1u")
      (footprint "eagle-import:C0603")
      (libsource (lib "eagle-import") (part "rcl_334_C-EUC0603"))
    )
    (comp (ref "C_VREF_PT3")
      (value "1u")
      (footprint "eagle-import:C0603")
      (libsource (lib "eagle-import") (part "rcl_334_C-EUC0603"))
    )
    (comp (ref "D1")
      (value "5V6")
      (footprint "eagle-import:DMELF")
      (libsource (lib "eagle-import") (part "DZMELF"))
    )
    (comp (ref "D2")
      (value "5V6")
      (footprint "eagle-import:DMELF")
      (libsource (lib "eagle-import") (part "DZMELF"))
    )
    (comp (ref "D3")
      (value "3V6")
      (footprint "eagle-import:DMELF")
      (libsource (lib "eagle-import") (part "DZMELF"))
    )
    (comp (ref "D4")
      (value "3V6")
      (footprint "eagle-import:DMELF")
      (libsource (lib "eagle-import") (part "DZMELF"))
    )
    (comp (ref "D5")
      (value "5V6")
      (footprint "eagle-import:DMELF")
      (libsource (lib "eagle-import") (part "DZMELF"))
    )
    (comp (ref "D6")
      (value "5V6")
      (footprint "eagle-import:DMELF")
      (libsource (lib "eagle-import") (part "DZMELF"))
    )
    (comp (ref "D7")
      (value "3V6")
      (footprint "eagle-import:DMELF")
      (libsource (lib "eagle-import") (part "DZMELF"))
    )
    (comp (ref "D8")
      (value "3V6")
      (footprint "eagle-import:DMELF")
      (libsource (lib "eagle-import") (part "DZMELF"))
    )
    (comp (ref "D9")
      (value "3V6")
      (footprint "eagle-import:DMELF")
      (libsource (lib "eagle-import") (part "DZMELF"))
    )
    (comp (ref "D10")
      (value "3V6")
      (footprint "eagle-import:DMELF")
      (libsource (lib "eagle-import") (part "DZMELF"))
    )
    (comp (ref "D11")
      (value "3V6")
      (footprint "eagle-import:DMELF")
      (libsource (lib "eagle-import") (part "DZMELF"))
    )
    (comp (ref "D12")
      (value "3V6")
      (footprint "eagle-import:DMELF")
      (libsource (lib "eagle-import") (part "DZMELF"))
    )
    (comp (ref "Q1")
      (value "12MHz")
      (footprint "eagle-import:SM49")
      (libsource (lib "eagle-import") (part "CRYSTALSM49"))
    )
    (comp (ref "R1")
      (value "4k7")
      (footprint "eagle-import:R0603")
      (libsource (lib "eagle-import") (part "R-EU_R0603"))
    )
    (comp (ref "R2")
      (value "4k7")
      (footprint "eagle-import:R0603")
      (libsource (lib "eagle-import") (part "R-EU_R0603"))
    )
    (comp (ref "R3")
      (value "47")
      (footprint "eagle-import:R0603")
      (libsource (lib "eagle-import") (part "R-EU_R0603"))
    )
    (comp (ref "R4")
      (value "40 1%")
      (footprint "eagle-import:R0805")
      (libsource (lib "eagle-import") (part "R-EU_R0805"))
    )
    (comp (ref "R5")
      (value "40 1%")
      (footprint "eagle-import:R0805")
      (libsource (lib "eagle-import") (part "R-EU_R0805"))
    )
    (comp (ref "R6")
      (value "1k 0.1%")
      (footprint "eagle-import:R0805")
      (libsource (lib "eagle-import") (part "R-EU_R0805"))
    )
    (comp (ref "R7")
      (value "1k 0.1%")
      (footprint "eagle-import:R0805")
      (libsource (lib "eagle-import") (part "R-EU_R0805"))
    )
    (comp (ref "R8")
      (value "4k7")
      (footprint "eagle-import:R0603")
      (libsource (lib "eagle-import") (part "R-EU_R0603"))
    )
    (comp (ref "R10")
      (value "500")
      (footprint "eagle-import:R0805")
      (libsource (lib "eagle-import") (part "rcl_R-EU_R0805"))
    )
    (comp (ref "R11")
      (value "3k")
      (footprint "eagle-import:R0805")
      (libsource (lib "eagle-import") (part "rcl_334_R-EU_R0805"))
    )
    (comp (ref "R12")
      (value "2k")
      (footprint "eagle-import:R0805")
      (libsource (lib "eagle-import") (part "rcl_334_R-EU_R0805"))
    )
    (comp (ref "R13")
      (value "4k7")
      (footprint "eagle-import:R0805")
      (libsource (lib "eagle-import") (part "rcl_334_R-EU_R0805"))
    )
    (comp (ref "R14")
      (value "7k5")
      (footprint "eagle-import:R0805")
      (libsource (lib "eagle-import") (part "rcl_334_R-EU_R0805"))
    )
    (comp (ref "R15")
      (value "500")
      (footprint "eagle-import:R0805")
      (libsource (lib "eagle-import") (part "rcl_R-EU_R0805"))
    )
    (comp (ref "R16")
      (value "3k3")
      (footprint "eagle-import:R0805")
      (libsource (lib "eagle-import") (part "rcl_R-EU_R0805"))
    )
    (comp (ref "R17")
      (value "3k3")
      (footprint "eagle-import:R0805")
      (libsource (lib "eagle-import") (part "rcl_R-EU_R0805"))
    )
    (comp (ref "R22")
      (value "100k")
      (footprint "eagle-import:R0805")
      (libsource (lib "eagle-import") (part "rcl_334_R-EU_R0805"))
    )
    (comp (ref "R23")
      (value "1k")
      (footprint "eagle-import:R0805")
      (libsource (lib "eagle-import") (part "rcl_334_R-EU_R0805"))
    )
    (comp (ref "R24")
      (value "?")
      (footprint "eagle-import:R0805")
      (libsource (lib "eagle-import") (part "rcl_334_R-EU_R0805"))
    )
    (comp (ref "R25")
      (value "?")
      (footprint "eagle-import:R0805")
      (libsource (lib "eagle-import") (part "rcl_334_R-EU_R0805"))
    )
    (comp (ref "R30")
      (value "4k7")
      (footprint "eagle-import:R0603")
      (libsource (lib "eagle-import") (part "R-EU_R0603"))
    )
    (comp (ref "R31")
      (value "47")
      (footprint "eagle-import:R0603")
      (libsource (lib "eagle-import") (part "R-EU_R0603"))
    )
    (comp (ref "R32")
      (value "40 1%")
      (footprint "eagle-import:R0805")
      (libsource (lib "eagle-import") (part "R-EU_R0805"))
    )
    (comp (ref "R33")
      (value "40 1%")
      (footprint "eagle-import:R0805")
      (libsource (lib "eagle-import") (part "R-EU_R0805"))
    )
    (comp (ref "R34")
      (value "1k 0.1%")
      (footprint "eagle-import:R0805")
      (libsource (lib "eagle-import") (part "R-EU_R0805"))
    )
    (comp (ref "R35")
      (value "1k 0.1%")
      (footprint "eagle-import:R0805")
      (libsource (lib "eagle-import") (part "R-EU_R0805"))
    )
    (comp (ref "R36")
      (value "4k7")
      (footprint "eagle-import:R0603")
      (libsource (lib "eagle-import") (part "R-EU_R0603"))
    )
    (comp (ref "R37")
      (value "4k7")
      (footprint "eagle-import:R0603")
      (libsource (lib "eagle-import") (part "R-EU_R0603"))
    )
    (comp (ref "R38")
      (value "47")
      (footprint "eagle-import:R0603")
      (libsource (lib "eagle-import") (part "R-EU_R0603"))
    )
    (comp (ref "R39")
      (value "40 1%")
      (footprint "eagle-import:R0805")
      (libsource (lib "eagle-import") (part "R-EU_R0805"))
    )
    (comp (ref "R40")
      (value "40 1%")
      (footprint "eagle-import:R0805")
      (libsource (lib "eagle-import") (part "R-EU_R0805"))
    )
    (comp (ref "R41")
      (value "1k 0.1%")
      (footprint "eagle-import:R0805")
      (libsource (lib "eagle-import") (part "R-EU_R0805"))
    )
    (comp (ref "R42")
      (value "1k 0.1%")
      (footprint "eagle-import:R0805")
      (libsource (lib "eagle-import") (part "R-EU_R0805"))
    )
    (comp (ref "R43")
      (value "4k7")
      (footprint "eagle-import:R0603")
      (libsource (lib "eagle-import") (part "R-EU_R0603"))
    )
    (comp (ref "R44")
      (value "4k7")
      (footprint "eagle-import:R0603")
      (libsource (lib "eagle-import") (part "R-EU_R0603"))
    )
    (comp (ref "R45")
      (value "47")
      (footprint "eagle-import:R0603")
      (libsource (lib "eagle-import") (part "R-EU_R0603"))
    )
    (comp (ref "R46")
      (value "40 1%")
      (footprint "eagle-import:R0805")
      (libsource (lib "eagle-import") (part "R-EU_R0805"))
    )
    (comp (ref "R47")
      (value "40 1%")
      (footprint "eagle-import:R0805")
      (libsource (lib "eagle-import") (part "R-EU_R0805"))
    )
    (comp (ref "R48")
      (value "1k 0.1%")
      (footprint "eagle-import:R0805")
      (libsource (lib "eagle-import") (part "R-EU_R0805"))
    )
    (comp (ref "R49")
      (value "1k 0.1%")
      (footprint "eagle-import:R0805")
      (libsource (lib "eagle-import") (part "R-EU_R0805"))
    )
    (comp (ref "R50")
      (value "4k7")
      (footprint "eagle-import:R0603")
      (libsource (lib "eagle-import") (part "R-EU_R0603"))
    )
    (comp (ref "R51")
      (value "4k7")
      (footprint "eagle-import:R0603")
      (libsource (lib "eagle-import") (part "R-EU_R0603"))
    )
    (comp (ref "R52")
      (value "47")
      (footprint "eagle-import:R0603")
      (libsource (lib "eagle-import") (part "R-EU_R0603"))
    )
    (comp (ref "R53")
      (value "40 1%")
      (footprint "eagle-import:R0805")
      (libsource (lib "eagle-import") (part "R-EU_R0805"))
    )
    (comp (ref "R54")
      (value "40 1%")
      (footprint "eagle-import:R0805")
      (libsource (lib "eagle-import") (part "R-EU_R0805"))
    )
    (comp (ref "R55")
      (value "1k 0.1%")
      (footprint "eagle-import:R0805")
      (libsource (lib "eagle-import") (part "R-EU_R0805"))
    )
    (comp (ref "R56")
      (value "1k 0.1%")
      (footprint "eagle-import:R0805")
      (libsource (lib "eagle-import") (part "R-EU_R0805"))
    )
    (comp (ref "R57")
      (value "4k7")
      (footprint "eagle-import:R0603")
      (libsource (lib "eagle-import") (part "R-EU_R0603"))
    )
    (comp (ref "R58")
      (value "4k7")
      (footprint "eagle-import:R0603")
      (libsource (lib "eagle-import") (part "R-EU_R0603"))
    )
    (comp (ref "R59")
      (value "47")
      (footprint "eagle-import:R0603")
      (libsource (lib "eagle-import") (part "R-EU_R0603"))
    )
    (comp (ref "R60")
      (value "40 1%")
      (footprint "eagle-import:R0805")
      (libsource (lib "eagle-import") (part "R-EU_R0805"))
    )
    (comp (ref "R61")
      (value "40 1%")
      (footprint "eagle-import:R0805")
      (libsource (lib "eagle-import") (part "R-EU_R0805"))
    )
    (comp (ref "R62")
      (value "1k 0.1%")
      (footprint "eagle-import:R0805")
      (libsource (lib "eagle-import") (part "R-EU_R0805"))
    )
    (comp (ref "R63")
      (value "1k 0.1%")
      (footprint "eagle-import:R0805")
      (libsource (lib "eagle-import") (part "R-EU_R0805"))
    )
    (comp (ref "R64")
      (value "inf")
      (footprint "eagle-import:R0805")
      (libsource (lib "eagle-import") (part "rcl_334_R-EU_R0805"))
    )
    (comp (ref "R65")
      (value "inf")
      (footprint "eagle-import:R0805")
      (libsource (lib "eagle-import") (part "rcl_334_R-EU_R0805"))
    )
    (comp (ref "R66")
      (value "inf")
      (footprint "eagle-import:RTRIM3224X")
      (libsource (lib "eagle-import") (part "R-TRIMM3224X"))
    )
    (comp (ref "RN11")
      (value "3k")
      (footprint "eagle-import:EXBS8V")
      (libsource (lib "eagle-import") (part "4R-NEXBS8V"))
    )
    (comp (ref "RN12")
      (value "1k")
      (footprint "eagle-import:EXBS8V")
      (libsource (lib "eagle-import") (part "4R-NEXBS8V"))
    )
    (comp (ref "RN_A_PT1")
      (value "47")
      (footprint "eagle-import:0603-ARC")
      (libsource (lib "eagle-import") (part "4R-N0603-ARC"))
    )
    (comp (ref "RN_A_PT2")
      (value "47")
      (footprint "eagle-import:0603-ARC")
      (libsource (lib "eagle-import") (part "4R-N0603-ARC"))
    )
    (comp (ref "RN_A_PT3")
      (value "47")
      (footprint "eagle-import:0603-ARC")
      (libsource (lib "eagle-import") (part "4R-N0603-ARC"))
    )
    (comp (ref "RN_B_PT1")
      (value "47")
      (footprint "eagle-import:0603-ARC")
      (libsource (lib "eagle-import") (part "4R-N0603-ARC"))
    )
    (comp (ref "RN_B_PT2")
      (value "47")
      (footprint "eagle-import:0603-ARC")
      (libsource (lib "eagle-import") (part "4R-N0603-ARC"))
    )
    (comp (ref "RN_B_PT3")
      (value "47")
      (footprint "eagle-import:0603-ARC")
      (libsource (lib "eagle-import") (part "4R-N0603-ARC"))
    )
    (comp (ref "RN_DMS1")
      (value "47")
      (footprint "eagle-import:0603-ARC")
      (libsource (lib "eagle-import") (part "4R-N0603-ARC"))
    )
    (comp (ref "RN_DMS2")
      (value "47")
      (footprint "eagle-import:0603-ARC")
      (libsource (lib "eagle-import") (part "4R-N0603-ARC"))
    )
    (comp (ref "RN_DMS3")
      (value "47")
      (footprint "eagle-import:0603-ARC")
      (libsource (lib "eagle-import") (part "4R-N0603-ARC"))
    )
    (comp (ref "RN_DMS4")
      (value "47")
      (footprint "eagle-import:0603-ARC")
      (libsource (lib "eagle-import") (part "4R-N0603-ARC"))
    )
    (comp (ref "RN_DMS5")
      (value "47")
      (footprint "eagle-import:0603-ARC")
      (libsource (lib "eagle-import") (part "4R-N0603-ARC"))
    )
    (comp (ref "RN_DMS6")
      (value "47")
      (footprint "eagle-import:0603-ARC")
      (libsource (lib "eagle-import") (part "4R-N0603-ARC"))
    )
    (comp (ref "R_I1_PT1")
      (value "R-EU_R0603")
      (footprint "eagle-import:R0603")
      (libsource (lib "eagle-import") (part "R-EU_R0603"))
    )
    (comp (ref "R_I1_PT2")
      (value "R-EU_R0603")
      (footprint "eagle-import:R0603")
      (libsource (lib "eagle-import") (part "R-EU_R0603"))
    )
    (comp (ref "R_I1_PT3")
      (value "5k")
      (footprint "eagle-import:R0603")
      (libsource (lib "eagle-import") (part "R-EU_R0603"))
    )
    (comp (ref "R_I2_PT1")
      (value "R-EU_R0603")
      (footprint "eagle-import:R0603")
      (libsource (lib "eagle-import") (part "R-EU_R0603"))
    )
    (comp (ref "R_I2_PT2")
      (value "R-EU_R0603")
      (footprint "eagle-import:R0603")
      (libsource (lib "eagle-import") (part "R-EU_R0603"))
    )
    (comp (ref "R_I2_PT3")
      (value "5k")
      (footprint "eagle-import:R0603")
      (libsource (lib "eagle-import") (part "R-EU_R0603"))
    )
    (comp (ref "R_R1_PT1")
      (value "R-EU_R0603")
      (footprint "eagle-import:R0603")
      (libsource (lib "eagle-import") (part "R-EU_R0603"))
    )
    (comp (ref "R_R1_PT2")
      (value "R-EU_R0603")
      (footprint "eagle-import:R0603")
      (libsource (lib "eagle-import") (part "R-EU_R0603"))
    )
    (comp (ref "R_R1_PT3")
      (value "3k16")
      (footprint "eagle-import:R0603")
      (libsource (lib "eagle-import") (part "R-EU_R0603"))
    )
    (comp (ref "R_R2_PT1")
      (value "R-EU_R0603")
      (footprint "eagle-import:R0603")
      (libsource (lib "eagle-import") (part "R-EU_R0603"))
    )
    (comp (ref "R_R2_PT2")
      (value "R-EU_R0603")
      (footprint "eagle-import:R0603")
      (libsource (lib "eagle-import") (part "R-EU_R0603"))
    )
    (comp (ref "R_R2_PT3")
      (value "inf")
      (footprint "eagle-import:R0603")
      (libsource (lib "eagle-import") (part "R-EU_R0603"))
    )
    (comp (ref "R_REF_PT1")
      (value "R-EU_R0603")
      (footprint "eagle-import:R0603")
      (libsource (lib "eagle-import") (part "R-EU_R0603"))
    )
    (comp (ref "R_REF_PT2")
      (value "R-EU_R0603")
      (footprint "eagle-import:R0603")
      (libsource (lib "eagle-import") (part "R-EU_R0603"))
    )
    (comp (ref "R_REF_PT3")
      (value "1k62")
      (footprint "eagle-import:R0603")
      (libsource (lib "eagle-import") (part "R-EU_R0603"))
    )
    (comp (ref "U$1")
      (value "COMMON_MODE_CHOKE")
      (footprint "eagle-import:COMMON_MODE_CHOKE")
      (libsource (lib "eagle-import") (part "COMMON_MODE_CHOKE"))
    )
    (comp (ref "U$2")
      (value "COMMON_MODE_CHOKE")
      (footprint "eagle-import:COMMON_MODE_CHOKE")
      (libsource (lib "eagle-import") (part "COMMON_MODE_CHOKE"))
    )
    (comp (ref "U$3")
      (value "COMMON_MODE_CHOKE")
      (footprint "eagle-import:COMMON_MODE_CHOKE")
      (libsource (lib "eagle-import") (part "COMMON_MODE_CHOKE"))
    )
    (comp (ref "U$4")
      (value "COMMON_MODE_CHOKE")
      (footprint "eagle-import:COMMON_MODE_CHOKE")
      (libsource (lib "eagle-import") (part "COMMON_MODE_CHOKE"))
    )
    (comp (ref "U$5")
      (value "COMMON_MODE_CHOKE")
      (footprint "eagle-import:COMMON_MODE_CHOKE")
      (libsource (lib "eagle-import") (part "COMMON_MODE_CHOKE"))
    )
    (comp (ref "U$6")
      (value "COMMON_MODE_CHOKE")
      (footprint "eagle-import:COMMON_MODE_CHOKE")
      (libsource (lib "eagle-import") (part "COMMON_MODE_CHOKE"))
    )
    (comp (ref "U_7805")
      (value "LM78L05ACMX/NOPB")
      (footprint "eagle-import:SOIC8")
      (libsource (lib "eagle-import") (part "LM78L05ACMX/NOPB"))
    )
    (comp (ref "U_ADC_DMS1")
      (value "ADS1147TSSOP20")
      (footprint "eagle-import:TSSOP20")
      (libsource (lib "eagle-import") (part "ADS1147TSSOP20"))
    )
    (comp (ref "U_ADC_DMS2")
      (value "ADS1147TSSOP20")
      (footprint "eagle-import:TSSOP20")
      (libsource (lib "eagle-import") (part "ADS1147TSSOP20"))
    )
    (comp (ref "U_ADC_DMS3")
      (value "ADS1147TSSOP20")
      (footprint "eagle-import:TSSOP20")
      (libsource (lib "eagle-import") (part "ADS1147TSSOP20"))
    )
    (comp (ref "U_ADC_DMS4")
      (value "ADS1147TSSOP20")
      (footprint "eagle-import:TSSOP20")
      (libsource (lib "eagle-import") (part "ADS1147TSSOP20"))
    )
    (comp (ref "U_ADC_DMS5")
      (value "ADS1147TSSOP20")
      (footprint "eagle-import:TSSOP20")
      (libsource (lib "eagle-import") (part "ADS1147TSSOP20"))
    )
    (comp (ref "U_ADC_DMS6")
      (value "ADS1147TSSOP20")
      (footprint "eagle-import:TSSOP20")
      (libsource (lib "eagle-import") (part "ADS1147TSSOP20"))
    )
    (comp (ref "U_ADC_PT1")
      (value "ADS1147TSSOP20")
      (footprint "eagle-import:TSSOP20")
      (libsource (lib "eagle-import") (part "ADS1147TSSOP20"))
    )
    (comp (ref "U_ADC_PT2")
      (value "ADS1147TSSOP20")
      (footprint "eagle-import:TSSOP20")
      (libsource (lib "eagle-import") (part "ADS1147TSSOP20"))
    )
    (comp (ref "U_ADC_PT3")
      (value "ADS1147TSSOP20")
      (footprint "eagle-import:TSSOP20")
      (libsource (lib "eagle-import") (part "ADS1147TSSOP20"))
    )
    (comp (ref "U_ADR366_3")
      (value "ADR366WAUJZ")
      (footprint "eagle-import:SOT23-5")
      (libsource (lib "eagle-import") (part "ADR36UJZ_"))
    )
    (comp (ref "U_CH340G")
      (value "CH340G")
      (footprint "eagle-import:SOIC16")
      (libsource (lib "eagle-import") (part "CH340G"))
    )
    (comp (ref "U_FLASH1")
      (value "S70FL01GS")
      (footprint "eagle-import:SO16")
      (libsource (lib "eagle-import") (part "S70FL01GS"))
    )
    (comp (ref "U_FLASH2")
      (value "S70FL01GS")
      (footprint "eagle-import:SO16")
      (libsource (lib "eagle-import") (part "S70FL01GS"))
    )
    (comp (ref "U_LT1528")
      (value "LT1528")
      (footprint "eagle-import:Q5-DD")
      (libsource (lib "eagle-import") (part "LT1528"))
    )
    (comp (ref "U_MAX488")
      (value "MAX488CSA")
      (footprint "eagle-import:SO08")
      (fields (field (name "MF") "MAXIM"))
      (libsource (lib "eagle-import") (part "MAX488CSA"))
    )
    (comp (ref "U_OPTO_1")
      (value "MOCD207MSOIC-8")
      (footprint "eagle-import:SOIC127P594X363-8N")
      (fields (field (name "MANUFACTURER") "ON Semiconductor") (field (name "MPN") "MOCD207M"))
      (libsource (lib "eagle-import") (part "MOCD207MSOIC-8"))
    )
    (comp (ref "U_OPTO_2")
      (value "MOCD207MSOIC-8")
      (footprint "eagle-import:SOIC127P594X363-8N")
      (fields (field (name "MANUFACTURER") "ON Semiconductor") (field (name "MPN") "MOCD207M"))
      (libsource (lib "eagle-import") (part "MOCD207MSOIC-8"))
    )
    (comp (ref "U_OPTO_3")
      (value "MOCD207MSOIC-8")
      (footprint "eagle-import:SOIC127P594X363-8N")
      (fields (field (name "MANUFACTURER") "ON Semiconductor") (field (name "MPN") "MOCD207M"))
      (libsource (lib "eagle-import") (part "MOCD207MSOIC-8"))
    )
    (comp (ref "U_TRACODCDC")
      (value "THN10-2411WIR")
      (footprint "eagle-import:THL_20WI_SERIES")
      (libsource (lib "eagle-import") (part "THL_20WI_SERIES"))
    )
    (comp (ref "C76")
      (value "100n")
      (footprint "eagle-import:0603-CAP")
      (libsource (lib "eagle-import") (part "CAP0603-CAP"))
    )
    (comp (ref "C77")
      (value "100n")
      (footprint "eagle-import:C1206")
      (libsource (lib "eagle-import") (part "rcl_334_C-EUC1206"))
    )
    (comp (ref "C78")
      (value "100n")
      (footprint "eagle-import:C1206")
      (libsource (lib "eagle-import") (part "rcl_334_C-EUC1206"))
    )
    (comp (ref "U$7")
      (value "MICROSD")
      (footprint "eagle-import:MICROSD")
      (libsource (lib "eagle-import") (part "MICROSD"))
    )
    (comp (ref "U$8")
      (value "PLT131PLT131-T1")
      (footprint "eagle-import:PLT131-T1")
      (libsource (lib "eagle-import") (part "PLT131PLT131-T1"))
    )
    (comp (ref "U$9")
      (value "PLR135")
      (footprint "eagle-import:PLR135-T1")
      (libsource (lib "eagle-import") (part "PLR135"))
    )
    (comp (ref "X_DMS")
      (value "403-5X020-5X")
      (footprint "eagle-import:403-5X020-5X")
      (libsource (lib "eagle-import") (part "403-5X020-5X"))
    )
    (comp (ref "X_GPIO")
      (value "403-5X020-5X")
      (footprint "eagle-import:403-5X020-5X")
      (libsource (lib "eagle-import") (part "403-5X020-5X"))
    )
    (comp (ref "X_MIRROR")
      (value "403-5X026-5X")
      (footprint "eagle-import:403-5X026-5X")
      (libsource (lib "eagle-import") (part "403-5X026-5X"))
    )
    (comp (ref "X_MIRROR1")
      (value "403-5X026-5X")
      (footprint "eagle-import:403-5X026-5X")
      (libsource (lib "eagle-import") (part "403-5X026-5X"))
    )
    (comp (ref "X_PROG")
      (value "x")
      (footprint "eagle-import:MA10-2")
      (libsource (lib "eagle-import") (part "MA10-2"))
    )
    (comp (ref "X_PT")
      (value "403-5X012-5X")
      (footprint "eagle-import:403-5X012-5X")
      (libsource (lib "eagle-import") (part "403-5X012-5X"))
    )
    (comp (ref "X_RXSM-DAPI")
      (value "403-5X020-5X")
      (footprint "eagle-import:403-5X020-5X")
      (libsource (lib "eagle-import") (part "403-5X020-5X"))
    )
    (comp (ref "LED1")
      (value "1V9")
      (footprint "eagle-import:CHIP-LED0805")
      (libsource (lib "eagle-import") (part "LEDCHIP-LED0805"))
    )
    (comp (ref "LED2")
      (value "1V9")
      (footprint "eagle-import:CHIP-LED0805")
      (libsource (lib "eagle-import") (part "LEDCHIP-LED0805"))
    )
    (comp (ref "LED3")
      (value "1V9")
      (footprint "eagle-import:CHIP-LED0805")
      (libsource (lib "eagle-import") (part "LEDCHIP-LED0805"))
    )
    (comp (ref "LED4")
      (value "1V9")
      (footprint "eagle-import:CHIP-LED0805")
      (libsource (lib "eagle-import") (part "LEDCHIP-LED0805"))
    )
    (comp (ref "LED5")
      (value "1V9")
      (footprint "eagle-import:CHIP-LED0805")
      (libsource (lib "eagle-import") (part "LEDCHIP-LED0805"))
    )
    (comp (ref "LED6")
      (value "1V9")
      (footprint "eagle-import:CHIP-LED0805")
      (libsource (lib "eagle-import") (part "LEDCHIP-LED0805"))
    )
    (comp (ref "LED7")
      (value "1V9")
      (footprint "eagle-import:CHIP-LED0805")
      (libsource (lib "eagle-import") (part "LEDCHIP-LED0805"))
    )
    (comp (ref "LED8")
      (value "1V9")
      (footprint "eagle-import:CHIP-LED0805")
      (libsource (lib "eagle-import") (part "LEDCHIP-LED0805"))
    )
    (comp (ref "R18")
      (value "680")
      (footprint "eagle-import:R0805")
      (libsource (lib "eagle-import") (part "rcl_334_R-EU_R0805"))
    )
    (comp (ref "R19")
      (value "330")
      (footprint "eagle-import:R0805")
      (libsource (lib "eagle-import") (part "rcl_334_R-EU_R0805"))
    )
    (comp (ref "R20")
      (value "4k7")
      (footprint "eagle-import:R0805")
      (libsource (lib "eagle-import") (part "rcl_334_R-EU_R0805"))
    )
    (comp (ref "R21")
      (value "470")
      (footprint "eagle-import:R0805")
      (libsource (lib "eagle-import") (part "rcl_334_R-EU_R0805"))
    )
    (comp (ref "RN10")
      (value "330")
      (footprint "eagle-import:EXBS8V")
      (libsource (lib "eagle-import") (part "4R-NEXBS8V"))
    )
    (comp (ref "C16")
      (value "2.2u")
      (footprint "eagle-import:C1206")
      (libsource (lib "eagle-import") (part "rcl_334_C-EUC1206"))
    )
    (comp (ref "C17")
      (value "2.2u")
      (footprint "eagle-import:C1206")
      (libsource (lib "eagle-import") (part "rcl_334_C-EUC1206"))
    )
    (comp (ref "C18")
      (value "100n")
      (footprint "eagle-import:0603-CAP")
      (libsource (lib "eagle-import") (part "CAP0603-CAP"))
    )
    (comp (ref "JP1")
      (value "JUMPER-SMT_2_NC_PASTE_SILK")
      (footprint "eagle-import:SMT-JUMPER_2_NC_PASTE_SILK")
      (libsource (lib "eagle-import") (part "JUMPER-SMT_2_NC_PASTE_SILK"))
    )
    (comp (ref "JP_MS")
      (value "x")
      (footprint "eagle-import:1X02")
      (libsource (lib "eagle-import") (part "M02PTH"))
    )
    (comp (ref "R9")
      (value "10k")
      (footprint "eagle-import:R0805")
      (libsource (lib "eagle-import") (part "rcl_334_R-EU_R0805"))
    )
    (comp (ref "R26")
      (value "10k")
      (footprint "eagle-import:R0805")
      (libsource (lib "eagle-import") (part "rcl_334_R-EU_R0805"))
    )
    (comp (ref "R27")
      (value "10k")
      (footprint "eagle-import:R0805")
      (libsource (lib "eagle-import") (part "rcl_334_R-EU_R0805"))
    )
    (comp (ref "R28")
      (value "99M")
      (footprint "eagle-import:R0805")
      (libsource (lib "eagle-import") (part "rcl_334_R-EU_R0805"))
    )
    (comp (ref "R29")
      (value "10k")
      (footprint "eagle-import:R0805")
      (libsource (lib "eagle-import") (part "rcl_334_R-EU_R0805"))
    )
    (comp (ref "SJ_MS")
      (value "SOLDERJUMPERNO")
      (footprint "eagle-import:SJ_2S-NO")
      (libsource (lib "eagle-import") (part "SOLDERJUMPERNO"))
    )
    (comp (ref "U_STM32F779")
      (value "STM32F77XXXLQFP208")
      (footprint "eagle-import:QFP50P3060X3060X385-208")
      (libsource (lib "eagle-import") (part "STM32F77XXXLQFP208"))
    )
  )
  (nets
    (net (code "1") (name "3V3") (class "Default")
      (node (ref "C10") (pin "1") (pinfunction "1_1") (pintype "passive"))
      (node (ref "C15") (pin "1") (pinfunction "1_1") (pintype "passive"))
      (node (ref "C19") (pin "1") (pinfunction "1_1") (pintype "passive"))
      (node (ref "C24") (pin "1") (pinfunction "1_1") (pintype "passive"))
      (node (ref "C25") (pin "1") (pinfunction "1_1") (pintype "passive"))
      (node (ref "C28") (pin "1") (pinfunction "1_1") (pintype "passive"))
      (node (ref "C29") (pin "1") (pinfunction "1_1") (pintype "passive"))
      (node (ref "C3") (pin "1") (pinfunction "1_1") (pintype "passive"))
      (node (ref "C30") (pin "1") (pinfunction "1_1") (pintype "passive"))
      (node (ref "C31") (pin "1") (pinfunction "1_1") (pintype "passive"))
      (node (ref "C32") (pin "1") (pinfunction "1_1") (pintype "passive"))
      (node (ref "C33") (pin "1") (pinfunction "1_1") (pintype "passive"))
      (node (ref "C37") (pin "2") (pinfunction "2_2") (pintype "passive"))
      (node (ref "C41") (pin "+") (pinfunction "+_+") (pintype "passive"))
      (node (ref "C47") (pin "1") (pinfunction "1_1") (pintype "passive"))
      (node (ref "C48") (pin "1") (pinfunction "1_1") (pintype "passive"))
      (node (ref "C5") (pin "1") (pinfunction "1_1") (pintype "passive"))
      (node (ref "C54") (pin "1") (pinfunction "1_1") (pintype "passive"))
      (node (ref "C55") (pin "1") (pinfunction "1_1") (pintype "passive"))
      (node (ref "C67") (pin "+") (pinfunction "+_+") (pintype "passive"))
      (node (ref "C68") (pin "+") (pinfunction "+_+") (pintype "passive"))
      (node (ref "C69") (pin "+") (pinfunction "+_+") (pintype "passive"))
      (node (ref "C70") (pin "+") (pinfunction "+_+") (pintype "passive"))
      (node (ref "C71") (pin "+") (pinfunction "+_+") (pintype "passive"))
      (node (ref "C72") (pin "+") (pinfunction "+_+") (pintype "passive"))
      (node (ref "C73") (pin "+") (pinfunction "+_+") (pintype "passive"))
      (node (ref "C76") (pin "1") (pinfunction "1_1") (pintype "passive"))
      (node (ref "C77") (pin "1") (pinfunction "1_1") (pintype "passive"))
      (node (ref "C78") (pin "1") (pinfunction "1_1") (pintype "passive"))
      (node (ref "C9") (pin "1") (pinfunction "1_1") (pintype "passive"))
      (node (ref "C_AVDD_PT1") (pin "1") (pinfunction "1_1") (pintype "passive"))
      (node (ref "C_AVDD_PT2") (pin "1") (pinfunction "1_1") (pintype "passive"))
      (node (ref "C_AVDD_PT3") (pin "1") (pinfunction "1_1") (pintype "passive"))
      (node (ref "C_DVDD_PT1") (pin "1") (pinfunction "1_1") (pintype "passive"))
      (node (ref "C_DVDD_PT2") (pin "1") (pinfunction "1_1") (pintype "passive"))
      (node (ref "C_DVDD_PT3") (pin "1") (pinfunction "1_1") (pintype "passive"))
      (node (ref "R1") (pin "1") (pinfunction "1_1") (pintype "passive"))
      (node (ref "R13") (pin "2") (pinfunction "2_2") (pintype "passive"))
      (node (ref "R19") (pin "2") (pinfunction "2_2") (pintype "passive"))
      (node (ref "R2") (pin "2") (pinfunction "2_2") (pintype "passive"))
      (node (ref "R26") (pin "2") (pinfunction "2_2") (pintype "passive"))
      (node (ref "R28") (pin "1") (pinfunction "1_1") (pintype "passive"))
      (node (ref "R29") (pin "2") (pinfunction "2_2") (pintype "passive"))
      (node (ref "R30") (pin "2") (pinfunction "2_2") (pintype "passive"))
      (node (ref "R34") (pin "2") (pinfunction "2_2") (pintype "passive"))
      (node (ref "R36") (pin "1") (pinfunction "1_1") (pintype "passive"))
      (node (ref "R37") (pin "2") (pinfunction "2_2") (pintype "passive"))
      (node (ref "R41") (pin "2") (pinfunction "2_2") (pintype "passive"))
      (node (ref "R43") (pin "1") (pinfunction "1_1") (pintype "passive"))
      (node (ref "R44") (pin "2") (pinfunction "2_2") (pintype "passive"))
      (node (ref "R48") (pin "2") (pinfunction "2_2") (pintype "passive"))
      (node (ref "R50") (pin "1") (pinfunction "1_1") (pintype "passive"))
      (node (ref "R51") (pin "2") (pinfunction "2_2") (pintype "passive"))
      (node (ref "R55") (pin "2") (pinfunction "2_2") (pintype "passive"))
      (node (ref "R57") (pin "1") (pinfunction "1_1") (pintype "passive"))
      (node (ref "R58") (pin "2") (pinfunction "2_2") (pintype "passive"))
      (node (ref "R6") (pin "2") (pinfunction "2_2") (pintype "passive"))
      (node (ref "R62") (pin "2") (pinfunction "2_2") (pintype "passive"))
      (node (ref "R8") (pin "1") (pinfunction "1_1") (pintype "passive"))
      (node (ref "R9") (pin "2") (pinfunction "2_2") (pintype "passive"))
      (node (ref "RN12") (pin "1") (pinfunction "1_1") (pintype "passive"))
      (node (ref "RN12") (pin "2") (pinfunction "1_2") (pintype "passive"))
      (node (ref "RN12") (pin "3") (pinfunction "1_3") (pintype "passive"))
      (node (ref "RN12") (pin "4") (pinfunction "1_4") (pintype "passive"))
      (node (ref "RN_A_PT1") (pin "8") (pinfunction "2_8") (pintype "passive"))
      (node (ref "RN_A_PT2") (pin "8") (pinfunction "2_8") (pintype "passive"))
      (node (ref "RN_A_PT3") (pin "8") (pinfunction "2_8") (pintype "passive"))
      (node (ref "RN_B_PT1") (pin "6") (pinfunction "2_6") (pintype "passive"))
      (node (ref "RN_B_PT2") (pin "6") (pinfunction "2_6") (pintype "passive"))
      (node (ref "RN_B_PT3") (pin "6") (pinfunction "2_6") (pintype "passive"))
      (node (ref "U$1") (pin "P$2") (pinfunction "2_P$2") (pintype "passive"))
      (node (ref "U$2") (pin "P$2") (pinfunction "2_P$2") (pintype "passive"))
      (node (ref "U$3") (pin "P$2") (pinfunction "2_P$2") (pintype "passive"))
      (node (ref "U$4") (pin "P$2") (pinfunction "2_P$2") (pintype "passive"))
      (node (ref "U$5") (pin "P$2") (pinfunction "2_P$2") (pintype "passive"))
      (node (ref "U$6") (pin "P$2") (pinfunction "2_P$2") (pintype "passive"))
      (node (ref "U$7") (pin "4") (pinfunction "VDD_4") (pintype "power_in"))
      (node (ref "U$8") (pin "VCC") (pinfunction "VCC_VCC") (pintype "bidirectional"))
      (node (ref "U$9") (pin "VCC") (pinfunction "VCC_VCC") (pintype "bidirectional"))
      (node (ref "U_ADC_DMS1") (pin "1") (pinfunction "DVDD_1") (pintype "bidirectional"))
      (node (ref "U_ADC_DMS1") (pin "14") (pinfunction "AVDD_14") (pintype "bidirectional"))
      (node (ref "U_ADC_DMS2") (pin "1") (pinfunction "DVDD_1") (pintype "bidirectional"))
      (node (ref "U_ADC_DMS2") (pin "14") (pinfunction "AVDD_14") (pintype "bidirectional"))
      (node (ref "U_ADC_DMS3") (pin "1") (pinfunction "DVDD_1") (pintype "bidirectional"))
      (node (ref "U_ADC_DMS3") (pin "14") (pinfunction "AVDD_14") (pintype "bidirectional"))
      (node (ref "U_ADC_DMS4") (pin "1") (pinfunction "DVDD_1") (pintype "bidirectional"))
      (node (ref "U_ADC_DMS4") (pin "14") (pinfunction "AVDD_14") (pintype "bidirectional"))
      (node (ref "U_ADC_DMS5") (pin "1") (pinfunction "DVDD_1") (pintype "bidirectional"))
      (node (ref "U_ADC_DMS5") (pin "14") (pinfunction "AVDD_14") (pintype "bidirectional"))
      (node (ref "U_ADC_DMS6") (pin "1") (pinfunction "DVDD_1") (pintype "bidirectional"))
      (node (ref "U_ADC_DMS6") (pin "14") (pinfunction "AVDD_14") (pintype "bidirectional"))
      (node (ref "U_ADC_PT1") (pin "1") (pinfunction "DVDD_1") (pintype "bidirectional"))
      (node (ref "U_ADC_PT1") (pin "14") (pinfunction "AVDD_14") (pintype "bidirectional"))
      (node (ref "U_ADC_PT2") (pin "1") (pinfunction "DVDD_1") (pintype "bidirectional"))
      (node (ref "U_ADC_PT2") (pin "14") (pinfunction "AVDD_14") (pintype "bidirectional"))
      (node (ref "U_ADC_PT3") (pin "1") (pinfunction "DVDD_1") (pintype "bidirectional"))
      (node (ref "U_ADC_PT3") (pin "14") (pinfunction "AVDD_14") (pintype "bidirectional"))
      (node (ref "U_CH340G") (pin "16") (pinfunction "VCC_16") (pintype "bidirectional"))
      (node (ref "U_CH340G") (pin "4") (pinfunction "V3_4") (pintype "bidirectional"))
      (node (ref "U_FLASH1") (pin "2") (pinfunction "VCC_2") (pintype "bidirectional"))
      (node (ref "U_FLASH2") (pin "2") (pinfunction "VCC_2") (pintype "bidirectional"))
      (node (ref "U_LT1528") (pin "1") (pinfunction "OUT_1") (pintype "bidirectional"))
      (node (ref "U_LT1528") (pin "2") (pinfunction "SENSE_2") (pintype "bidirectional"))
      (node (ref "U_STM32F779") (pin "103") (pinfunction "VDD_103") (pintype "bidirectional"))
      (node (ref "U_STM32F779") (pin "115") (pinfunction "VDD_115") (pintype "bidirectional"))
      (node (ref "U_STM32F779") (pin "118") (pinfunction "VDDDSI_118") (pintype "bidirectional"))
      (node (ref "U_STM32F779") (pin "137") (pinfunction "VDDUSB_137") (pintype "bidirectional"))
      (node (ref "U_STM32F779") (pin "15") (pinfunction "VDD_15") (pintype "bidirectional"))
      (node (ref "U_STM32F779") (pin "150") (pinfunction "VDD_150") (pintype "bidirectional"))
      (node (ref "U_STM32F779") (pin "158") (pinfunction "VDD_158") (pintype "bidirectional"))
      (node (ref "U_STM32F779") (pin "171") (pinfunction "VDDSDMMC_171") (pintype "bidirectional"))
      (node (ref "U_STM32F779") (pin "185") (pinfunction "VDD_185") (pintype "bidirectional"))
      (node (ref "U_STM32F779") (pin "204") (pinfunction "VDD_204") (pintype "bidirectional"))
      (node (ref "U_STM32F779") (pin "26") (pinfunction "VDD_26") (pintype "bidirectional"))
      (node (ref "U_STM32F779") (pin "39") (pinfunction "VDD_39") (pintype "bidirectional"))
      (node (ref "U_STM32F779") (pin "42") (pinfunction "VDDA_42") (pintype "bidirectional"))
      (node (ref "U_STM32F779") (pin "52") (pinfunction "VDD_52") (pintype "bidirectional"))
      (node (ref "U_STM32F779") (pin "59") (pinfunction "VDD_59") (pintype "bidirectional"))
      (node (ref "U_STM32F779") (pin "73") (pinfunction "VDD_73") (pintype "bidirectional"))
      (node (ref "U_STM32F779") (pin "83") (pinfunction "VDD_83") (pintype "bidirectional"))
      (node (ref "U_STM32F779") (pin "94") (pinfunction "VDD_94") (pintype "bidirectional"))
      (node (ref "X_GPIO") (pin "P$B1") (pinfunction "B1_P$B1") (pintype "passive"))
      (node (ref "X_GPIO") (pin "P$B2") (pinfunction "B2_P$B2") (pintype "passive"))
      (node (ref "X_PROG") (pin "1") (pinfunction "1_1") (pintype "passive"))
    )
    (net (code "2") (name "3V3CAP") (class "Default")
      (node (ref "U_STM32F779") (pin "6") (pinfunction "VBAT_6") (pintype "bidirectional"))
    )
    (net (code "3") (name "3V3REF") (class "Default")
      (node (ref "C74") (pin "2") (pinfunction "2_2") (pintype "passive"))
      (node (ref "C75") (pin "2") (pinfunction "2_2") (pintype "passive"))
      (node (ref "R24") (pin "2") (pinfunction "2_2") (pintype "passive"))
      (node (ref "U_ADR366_3") (pin "4") (pinfunction "VOUT_4") (pintype "power_in"))
      (node (ref "U_STM32F779") (pin "41") (pinfunction "VREF+_41") (pintype "bidirectional"))
    )
    (net (code "4") (name "5V") (class "Default")
      (node (ref "C35") (pin "2") (pinfunction "2_2") (pintype "passive"))
      (node (ref "C36") (pin "2") (pinfunction "2_2") (pintype "passive"))
      (node (ref "C39") (pin "+") (pinfunction "+_+") (pintype "passive"))
      (node (ref "C40") (pin "+") (pinfunction "+_+") (pintype "passive"))
      (node (ref "C52") (pin "2") (pinfunction "2_2") (pintype "passive"))
      (node (ref "C64") (pin "+") (pinfunction "+_+") (pintype "passive"))
      (node (ref "C65") (pin "+") (pinfunction "+_+") (pintype "passive"))
      (node (ref "C66") (pin "+") (pinfunction "+_+") (pintype "passive"))
      (node (ref "R18") (pin "2") (pinfunction "2_2") (pintype "passive"))
      (node (ref "R65") (pin "1") (pinfunction "1_1") (pintype "passive"))
      (node (ref "R66") (pin "3") (pinfunction "E_3") (pintype "passive"))
      (node (ref "U_ADR366_3") (pin "3") (pinfunction "VIN_3") (pintype "power_in"))
      (node (ref "U_LT1528") (pin "4") (pinfunction "SHDN_4") (pintype "bidirectional"))
      (node (ref "U_LT1528") (pin "5") (pinfunction "IN_5") (pintype "bidirectional"))
      (node (ref "U_TRACODCDC") (pin "3") (pinfunction "+VOUT_3") (pintype "passive"))
      (node (ref "X_RXSM-DAPI") (pin "P$A9") (pinfunction "A9_P$A9") (pintype "passive"))
    )
    (net (code "5") (name "5V-28V") (class "Default")
      (node (ref "C43") (pin "1") (pinfunction "1_1") (pintype "passive"))
      (node (ref "R14") (pin "2") (pinfunction "2_2") (pintype "passive"))
      (node (ref "R16") (pin "1") (pinfunction "1_1") (pintype "passive"))
      (node (ref "R21") (pin "2") (pinfunction "2_2") (pintype "passive"))
      (node (ref "U_7805") (pin "1") (pinfunction "VOUT_1") (pintype "bidirectional"))
      (node (ref "U_MAX488") (pin "1") (pinfunction "VCC_1") (pintype "power_in"))
    )
    (net (code "6") (name "28V") (class "Default")
      (node (ref "C34") (pin "2") (pinfunction "2_2") (pintype "passive"))
      (node (ref "C38") (pin "+") (pinfunction "+_+") (pintype "passive"))
      (node (ref "C42") (pin "2") (pinfunction "2_2") (pintype "passive"))
      (node (ref "C60") (pin "+") (pinfunction "+_+") (pintype "passive"))
      (node (ref "C61") (pin "+") (pinfunction "+_+") (pintype "passive"))
      (node (ref "C62") (pin "+") (pinfunction "+_+") (pintype "passive"))
      (node (ref "R20") (pin "2") (pinfunction "2_2") (pintype "passive"))
      (node (ref "RN11") (pin "1") (pinfunction "1_1") (pintype "passive"))
      (node (ref "RN11") (pin "2") (pinfunction "1_2") (pintype "passive"))
      (node (ref "RN11") (pin "3") (pinfunction "1_3") (pintype "passive"))
      (node (ref "RN11") (pin "4") (pinfunction "1_4") (pintype "passive"))
      (node (ref "U_7805") (pin "8") (pinfunction "VIN_8") (pintype "bidirectional"))
      (node (ref "U_TRACODCDC") (pin "1") (pinfunction "+VIN_1") (pintype "input"))
      (node (ref "X_MIRROR") (pin "P$A2") (pinfunction "A2_P$A2") (pintype "passive"))
      (node (ref "X_MIRROR") (pin "P$A3") (pinfunction "A3_P$A3") (pintype "passive"))
      (node (ref "X_MIRROR") (pin "P$A4") (pinfunction "A4_P$A4") (pintype "passive"))
      (node (ref "X_MIRROR1") (pin "P$A10") (pinfunction "A10_P$A10") (pintype "passive"))
      (node (ref "X_MIRROR1") (pin "P$A11") (pinfunction "A11_P$A11") (pintype "passive"))
      (node (ref "X_MIRROR1") (pin "P$A12") (pinfunction "A12_P$A12") (pintype "passive"))
      (node (ref "X_RXSM-DAPI") (pin "P$B1") (pinfunction "B1_P$B1") (pintype "passive"))
      (node (ref "X_RXSM-DAPI") (pin "P$B2") (pinfunction "B2_P$B2") (pintype "passive"))
    )
    (net (code "7") (name "28VGND") (class "Default")
      (node (ref "C34") (pin "1") (pinfunction "1_1") (pintype "passive"))
      (node (ref "C38") (pin "-") (pinfunction "-_-") (pintype "passive"))
      (node (ref "C42") (pin "1") (pinfunction "1_1") (pintype "passive"))
      (node (ref "C43") (pin "2") (pinfunction "2_2") (pintype "passive"))
      (node (ref "C44") (pin "2") (pinfunction "2_2") (pintype "passive"))
      (node (ref "C60") (pin "-") (pinfunction "-_-") (pintype "passive"))
      (node (ref "C61") (pin "-") (pinfunction "-_-") (pintype "passive"))
      (node (ref "C62") (pin "-") (pinfunction "-_-") (pintype "passive"))
      (node (ref "D5") (pin "A") (pinfunction "A_A") (pintype "passive"))
      (node (ref "D6") (pin "A") (pinfunction "A_A") (pintype "passive"))
      (node (ref "LED7") (pin "C") (pinfunction "C_C") (pintype "passive"))
      (node (ref "LED8") (pin "C") (pinfunction "C_C") (pintype "passive"))
      (node (ref "R11") (pin "1") (pinfunction "1_1") (pintype "passive"))
      (node (ref "R17") (pin "1") (pinfunction "1_1") (pintype "passive"))
      (node (ref "U_7805") (pin "2") (pinfunction "GND_2") (pintype "bidirectional"))
      (node (ref "U_7805") (pin "3") (pinfunction "GND_3") (pintype "bidirectional"))
      (node (ref "U_7805") (pin "6") (pinfunction "GND_6") (pintype "bidirectional"))
      (node (ref "U_7805") (pin "7") (pinfunction "GND_7") (pintype "bidirectional"))
      (node (ref "U_MAX488") (pin "4") (pinfunction "GND_4") (pintype "power_in"))
      (node (ref "U_OPTO_3") (pin "5") (pinfunction "EMT2_5") (pintype "output"))
      (node (ref "U_TRACODCDC") (pin "2") (pinfunction "-VIN_2") (pintype "input"))
      (node (ref "X_MIRROR") (pin "P$A1") (pinfunction "A1_P$A1") (pintype "passive"))
      (node (ref "X_MIRROR") (pin "P$B1") (pinfunction "B1_P$B1") (pintype "passive"))
      (node (ref "X_MIRROR") (pin "P$B2") (pinfunction "B2_P$B2") (pintype "passive"))
      (node (ref "X_MIRROR") (pin "P$B3") (pinfunction "B3_P$B3") (pintype "passive"))
      (node (ref "X_MIRROR") (pin "P$B4") (pinfunction "B4_P$B4") (pintype "passive"))
      (node (ref "X_MIRROR") (pin "P$B5") (pinfunction "B5_P$B5") (pintype "passive"))
      (node (ref "X_MIRROR") (pin "P$B6") (pinfunction "B6_P$B6") (pintype "passive"))
      (node (ref "X_MIRROR") (pin "P$B7") (pinfunction "B7_P$B7") (pintype "passive"))
      (node (ref "X_MIRROR") (pin "P$BL1") (pinfunction "CASE_P$BL1") (pintype "passive"))
      (node (ref "X_MIRROR") (pin "P$BL2") (pinfunction "CASE_P$BL2") (pintype "passive"))
      (node (ref "X_MIRROR") (pin "P$BL3") (pinfunction "CASE_P$BL3") (pintype "passive"))
      (node (ref "X_MIRROR") (pin "P$BL4") (pinfunction "CASE_P$BL4") (pintype "passive"))
      (node (ref "X_MIRROR1") (pin "P$A13") (pinfunction "A13_P$A13") (pintype "passive"))
      (node (ref "X_MIRROR1") (pin "P$B10") (pinfunction "B10_P$B10") (pintype "passive"))
      (node (ref "X_MIRROR1") (pin "P$B11") (pinfunction "B11_P$B11") (pintype "passive"))
      (node (ref "X_MIRROR1") (pin "P$B12") (pinfunction "B12_P$B12") (pintype "passive"))
      (node (ref "X_MIRROR1") (pin "P$B13") (pinfunction "B13_P$B13") (pintype "passive"))
      (node (ref "X_MIRROR1") (pin "P$B7") (pinfunction "B7_P$B7") (pintype "passive"))
      (node (ref "X_MIRROR1") (pin "P$B8") (pinfunction "B8_P$B8") (pintype "passive"))
      (node (ref "X_MIRROR1") (pin "P$B9") (pinfunction "B9_P$B9") (pintype "passive"))
      (node (ref "X_MIRROR1") (pin "P$BL1") (pinfunction "CASE_P$BL1") (pintype "passive"))
      (node (ref "X_MIRROR1") (pin "P$BL2") (pinfunction "CASE_P$BL2") (pintype "passive"))
      (node (ref "X_MIRROR1") (pin "P$BL3") (pinfunction "CASE_P$BL3") (pintype "passive"))
      (node (ref "X_MIRROR1") (pin "P$BL4") (pinfunction "CASE_P$BL4") (pintype "passive"))
      (node (ref "X_RXSM-DAPI") (pin "P$A1") (pinfunction "A1_P$A1") (pintype "passive"))
      (node (ref "X_RXSM-DAPI") (pin "P$A2") (pinfunction "A2_P$A2") (pintype "passive"))
      (node (ref "X_RXSM-DAPI") (pin "P$A6") (pinfunction "A6_P$A6") (pintype "passive"))
    )
    (net (code "8") (name "DAPI_N") (class "Default")
      (node (ref "D1") (pin "C") (pinfunction "C_C") (pintype "passive"))
      (node (ref "U_CH340G") (pin "6") (pinfunction "D-_6") (pintype "bidirectional"))
      (node (ref "X_RXSM-DAPI") (pin "P$B9") (pinfunction "B9_P$B9") (pintype "passive"))
    )
    (net (code "9") (name "DAPI_P") (class "Default")
      (node (ref "D2") (pin "C") (pinfunction "C_C") (pintype "passive"))
      (node (ref "U_CH340G") (pin "5") (pinfunction "D+_5") (pintype "bidirectional"))
      (node (ref "X_RXSM-DAPI") (pin "P$B10") (pinfunction "B10_P$B10") (pintype "passive"))
    )
    (net (code "10") (name "DAPI_RX") (class "Default")
      (node (ref "D4") (pin "C") (pinfunction "C_C") (pintype "passive"))
      (node (ref "U_CH340G") (pin "2") (pinfunction "TX_2") (pintype "bidirectional"))
      (node (ref "U_STM32F779") (pin "11") (pinfunction "PI9_11") (pintype "bidirectional"))
    )
    (net (code "11") (name "DAPI_TX") (class "Default")
      (node (ref "D3") (pin "C") (pinfunction "C_C") (pintype "passive"))
      (node (ref "U_CH340G") (pin "3") (pinfunction "RX_3") (pintype "bidirectional"))
      (node (ref "U_STM32F779") (pin "43") (pinfunction "PA0_43") (pintype "bidirectional"))
    )
    (net (code "12") (name "DMS11") (class "Default")
      (node (ref "U$2") (pin "P$1") (pinfunction "1_P$1") (pintype "passive"))
      (node (ref "X_DMS") (pin "P$B3") (pinfunction "B3_P$B3") (pintype "passive"))
    )
    (net (code "13") (name "DMS12") (class "Default")
      (node (ref "U$2") (pin "P$3") (pinfunction "3_P$3") (pintype "passive"))
      (node (ref "X_DMS") (pin "P$B2") (pinfunction "B2_P$B2") (pintype "passive"))
    )
    (net (code "14") (name "DMS13") (class "Default")
      (node (ref "U$2") (pin "P$5") (pinfunction "5_P$5") (pintype "passive"))
      (node (ref "X_DMS") (pin "P$B1") (pinfunction "B1_P$B1") (pintype "passive"))
    )
    (net (code "15") (name "DMS21") (class "Default")
      (node (ref "U$1") (pin "P$1") (pinfunction "1_P$1") (pintype "passive"))
      (node (ref "X_DMS") (pin "P$B6") (pinfunction "B6_P$B6") (pintype "passive"))
    )
    (net (code "16") (name "DMS22") (class "Default")
      (node (ref "U$1") (pin "P$3") (pinfunction "3_P$3") (pintype "passive"))
      (node (ref "X_DMS") (pin "P$B5") (pinfunction "B5_P$B5") (pintype "passive"))
    )
    (net (code "17") (name "DMS23") (class "Default")
      (node (ref "U$1") (pin "P$5") (pinfunction "5_P$5") (pintype "passive"))
      (node (ref "X_DMS") (pin "P$B4") (pinfunction "B4_P$B4") (pintype "passive"))
    )
    (net (code "18") (name "DMS31") (class "Default")
      (node (ref "U$3") (pin "P$1") (pinfunction "1_P$1") (pintype "passive"))
      (node (ref "X_DMS") (pin "P$B9") (pinfunction "B9_P$B9") (pintype "passive"))
    )
    (net (code "19") (name "DMS32") (class "Default")
      (node (ref "U$3") (pin "P$3") (pinfunction "3_P$3") (pintype "passive"))
      (node (ref "X_DMS") (pin "P$B8") (pinfunction "B8_P$B8") (pintype "passive"))
    )
    (net (code "20") (name "DMS33") (class "Default")
      (node (ref "U$3") (pin "P$5") (pinfunction "5_P$5") (pintype "passive"))
      (node (ref "X_DMS") (pin "P$B7") (pinfunction "B7_P$B7") (pintype "passive"))
    )
    (net (code "21") (name "DMS41") (class "Default")
      (node (ref "U$4") (pin "P$1") (pinfunction "1_P$1") (pintype "passive"))
      (node (ref "X_DMS") (pin "P$A1") (pinfunction "A1_P$A1") (pintype "passive"))
    )
    (net (code "22") (name "DMS42") (class "Default")
      (node (ref "U$4") (pin "P$3") (pinfunction "3_P$3") (pintype "passive"))
      (node (ref "X_DMS") (pin "P$A2") (pinfunction "A2_P$A2") (pintype "passive"))
    )
    (net (code "23") (name "DMS43") (class "Default")
      (node (ref "U$4") (pin "P$5") (pinfunction "5_P$5") (pintype "passive"))
      (node (ref "X_DMS") (pin "P$A3") (pinfunction "A3_P$A3") (pintype "passive"))
    )
    (net (code "24") (name "DMS51") (class "Default")
      (node (ref "U$5") (pin "P$1") (pinfunction "1_P$1") (pintype "passive"))
      (node (ref "X_DMS") (pin "P$A4") (pinfunction "A4_P$A4") (pintype "passive"))
    )
    (net (code "25") (name "DMS52") (class "Default")
      (node (ref "U$5") (pin "P$3") (pinfunction "3_P$3") (pintype "passive"))
      (node (ref "X_DMS") (pin "P$A5") (pinfunction "A5_P$A5") (pintype "passive"))
    )
    (net (code "26") (name "DMS53") (class "Default")
      (node (ref "U$5") (pin "P$5") (pinfunction "5_P$5") (pintype "passive"))
      (node (ref "X_DMS") (pin "P$A6") (pinfunction "A6_P$A6") (pintype "passive"))
    )
    (net (code "27") (name "DMS61") (class "Default")
      (node (ref "U$6") (pin "P$1") (pinfunction "1_P$1") (pintype "passive"))
      (node (ref "X_DMS") (pin "P$A7") (pinfunction "A7_P$A7") (pintype "passive"))
    )
    (net (code "28") (name "DMS62") (class "Default")
      (node (ref "U$6") (pin "P$3") (pinfunction "3_P$3") (pintype "passive"))
      (node (ref "X_DMS") (pin "P$A8") (pinfunction "A8_P$A8") (pintype "passive"))
    )
    (net (code "29") (name "DMS63") (class "Default")
      (node (ref "U$6") (pin "P$5") (pinfunction "5_P$5") (pintype "passive"))
      (node (ref "X_DMS") (pin "P$A9") (pinfunction "A9_P$A9") (pintype "passive"))
    )
    (net (code "30") (name "EXP_IN") (class "Default")
      (node (ref "D5") (pin "C") (pinfunction "C_C") (pintype "passive"))
      (node (ref "U_MAX488") (pin "2") (pinfunction "RO_2") (pintype "output"))
      (node (ref "U_OPTO_3") (pin "1") (pinfunction "A1_1") (pintype "bidirectional"))
    )
    (net (code "31") (name "EXP_IN_N") (class "Default")
      (node (ref "R15") (pin "1") (pinfunction "1_1") (pintype "passive"))
      (node (ref "R17") (pin "2") (pinfunction "2_2") (pintype "passive"))
      (node (ref "U_MAX488") (pin "7") (pinfunction "B_7") (pintype "input"))
      (node (ref "X_RXSM-DAPI") (pin "P$B3") (pinfunction "B3_P$B3") (pintype "passive"))
    )
    (net (code "32") (name "EXP_IN_OPT") (class "Default")
      (node (ref "D10") (pin "C") (pinfunction "C_C") (pintype "passive"))
      (node (ref "R13") (pin "1") (pinfunction "1_1") (pintype "passive"))
      (node (ref "U_OPTO_3") (pin "8") (pinfunction "COL1_8") (pintype "input"))
      (node (ref "U_STM32F779") (pin "200") (pinfunction "PE0_200") (pintype "bidirectional"))
    )
    (net (code "33") (name "EXP_IN_P") (class "Default")
      (node (ref "R10") (pin "2") (pinfunction "2_2") (pintype "passive"))
      (node (ref "R16") (pin "2") (pinfunction "2_2") (pintype "passive"))
      (node (ref "U_MAX488") (pin "8") (pinfunction "A_8") (pintype "input"))
      (node (ref "X_RXSM-DAPI") (pin "P$B4") (pinfunction "B4_P$B4") (pintype "passive"))
    )
    (net (code "34") (name "EXP_OUT") (class "Default")
      (node (ref "D6") (pin "C") (pinfunction "C_C") (pintype "passive"))
      (node (ref "R14") (pin "1") (pinfunction "1_1") (pintype "passive"))
      (node (ref "U_MAX488") (pin "3") (pinfunction "DI_3") (pintype "input"))
      (node (ref "U_OPTO_3") (pin "6") (pinfunction "COL2_6") (pintype "input"))
    )
    (net (code "35") (name "EXP_OUT_N") (class "Default")
      (node (ref "U_MAX488") (pin "6") (pinfunction "Z_6") (pintype "output"))
      (node (ref "X_RXSM-DAPI") (pin "P$A3") (pinfunction "A3_P$A3") (pintype "passive"))
    )
    (net (code "36") (name "EXP_OUT_OPT") (class "Default")
      (node (ref "U_OPTO_3") (pin "3") (pinfunction "A2_3") (pintype "bidirectional"))
      (node (ref "U_STM32F779") (pin "201") (pinfunction "PE1_201") (pintype "bidirectional"))
    )
    (net (code "37") (name "EXP_OUT_P") (class "Default")
      (node (ref "U_MAX488") (pin "5") (pinfunction "Y_5") (pintype "output"))
      (node (ref "X_RXSM-DAPI") (pin "P$A4") (pinfunction "A4_P$A4") (pintype "passive"))
    )
    (net (code "38") (name "FL_1_CS1") (class "Default")
      (node (ref "U_FLASH1") (pin "7") (pinfunction "CS1_7") (pintype "bidirectional"))
      (node (ref "U_STM32F779") (pin "104") (pinfunction "PB12_104") (pintype "bidirectional"))
    )
    (net (code "39") (name "FL_1_CS2") (class "Default")
      (node (ref "U_FLASH1") (pin "6") (pinfunction "CS2_6") (pintype "bidirectional"))
      (node (ref "U_STM32F779") (pin "102") (pinfunction "PH12_102") (pintype "bidirectional"))
    )
    (net (code "40") (name "FL_1_HLD") (class "Default")
      (node (ref "U_FLASH1") (pin "1") (pinfunction "HOLD_1") (pintype "bidirectional"))
      (node (ref "U_STM32F779") (pin "99") (pinfunction "PH9_99") (pintype "bidirectional"))
    )
    (net (code "41") (name "FL_1_RES") (class "Default")
      (node (ref "U_FLASH1") (pin "3") (pinfunction "RESET_3") (pintype "bidirectional"))
      (node (ref "U_STM32F779") (pin "101") (pinfunction "PH11_101") (pintype "bidirectional"))
    )
    (net (code "42") (name "FL_1_WP") (class "Default")
      (node (ref "U_FLASH1") (pin "9") (pinfunction "WP_9") (pintype "bidirectional"))
      (node (ref "U_STM32F779") (pin "100") (pinfunction "PH10_100") (pintype "bidirectional"))
    )
    (net (code "43") (name "FL_2_CS1") (class "Default")
      (node (ref "U_FLASH2") (pin "7") (pinfunction "CS1_7") (pintype "bidirectional"))
      (node (ref "U_STM32F779") (pin "112") (pinfunction "PD12_112") (pintype "bidirectional"))
    )
    (net (code "44") (name "FL_2_CS2") (class "Default")
      (node (ref "U_FLASH2") (pin "6") (pinfunction "CS2_6") (pintype "bidirectional"))
      (node (ref "U_STM32F779") (pin "111") (pinfunction "PD11_111") (pintype "bidirectional"))
    )
    (net (code "45") (name "FL_2_HLD") (class "Default")
      (node (ref "U_FLASH2") (pin "1") (pinfunction "HOLD_1") (pintype "bidirectional"))
      (node (ref "U_STM32F779") (pin "109") (pinfunction "PD9_109") (pintype "bidirectional"))
    )
    (net (code "46") (name "FL_2_RES") (class "Default")
      (node (ref "U_FLASH2") (pin "3") (pinfunction "RESET_3") (pintype "bidirectional"))
      (node (ref "U_STM32F779") (pin "110") (pinfunction "PD10_110") (pintype "bidirectional"))
    )
    (net (code "47") (name "FL_2_WP") (class "Default")
      (node (ref "U_FLASH2") (pin "9") (pinfunction "WP_9") (pintype "bidirectional"))
      (node (ref "U_STM32F779") (pin "113") (pinfunction "PD13_113") (pintype "bidirectional"))
    )
    (net (code "48") (name "GND") (class "Default")
      (node (ref "C1") (pin "2") (pinfunction "2_2") (pintype "passive"))
      (node (ref "C10") (pin "2") (pinfunction "2_2") (pintype "passive"))
      (node (ref "C11") (pin "2") (pinfunction "2_2") (pintype "passive"))
      (node (ref "C12") (pin "1") (pinfunction "1_1") (pintype "passive"))
      (node (ref "C14") (pin "2") (pinfunction "2_2") (pintype "passive"))
      (node (ref "C15") (pin "2") (pinfunction "2_2") (pintype "passive"))
      (node (ref "C16") (pin "1") (pinfunction "1_1") (pintype "passive"))
      (node (ref "C17") (pin "1") (pinfunction "1_1") (pintype "passive"))
      (node (ref "C18") (pin "2") (pinfunction "2_2") (pintype "passive"))
      (node (ref "C19") (pin "2") (pinfunction "2_2") (pintype "passive"))
      (node (ref "C2") (pin "2") (pinfunction "2_2") (pintype "passive"))
      (node (ref "C20") (pin "2") (pinfunction "2_2") (pintype "passive"))
      (node (ref "C21") (pin "1") (pinfunction "1_1") (pintype "passive"))
      (node (ref "C23") (pin "2") (pinfunction "2_2") (pintype "passive"))
      (node (ref "C24") (pin "2") (pinfunction "2_2") (pintype "passive"))
      (node (ref "C25") (pin "2") (pinfunction "2_2") (pintype "passive"))
      (node (ref "C26") (pin "2") (pinfunction "2_2") (pintype "passive"))
      (node (ref "C27") (pin "1") (pinfunction "1_1") (pintype "passive"))
      (node (ref "C28") (pin "2") (pinfunction "2_2") (pintype "passive"))
      (node (ref "C29") (pin "2") (pinfunction "2_2") (pintype "passive"))
      (node (ref "C3") (pin "2") (pinfunction "2_2") (pintype "passive"))
      (node (ref "C30") (pin "2") (pinfunction "2_2") (pintype "passive"))
      (node (ref "C31") (pin "2") (pinfunction "2_2") (pintype "passive"))
      (node (ref "C32") (pin "2") (pinfunction "2_2") (pintype "passive"))
      (node (ref "C33") (pin "2") (pinfunction "2_2") (pintype "passive"))
      (node (ref "C35") (pin "1") (pinfunction "1_1") (pintype "passive"))
      (node (ref "C36") (pin "1") (pinfunction "1_1") (pintype "passive"))
      (node (ref "C37") (pin "1") (pinfunction "1_1") (pintype "passive"))
      (node (ref "C39") (pin "-") (pinfunction "-_-") (pintype "passive"))
      (node (ref "C4") (pin "2") (pinfunction "2_2") (pintype "passive"))
      (node (ref "C40") (pin "-") (pinfunction "-_-") (pintype "passive"))
      (node (ref "C41") (pin "-") (pinfunction "-_-") (pintype "passive"))
      (node (ref "C46") (pin "2") (pinfunction "2_2") (pintype "passive"))
      (node (ref "C47") (pin "2") (pinfunction "2_2") (pintype "passive"))
      (node (ref "C48") (pin "2") (pinfunction "2_2") (pintype "passive"))
      (node (ref "C49") (pin "2") (pinfunction "2_2") (pintype "passive"))
      (node (ref "C5") (pin "2") (pinfunction "2_2") (pintype "passive"))
      (node (ref "C50") (pin "1") (pinfunction "1_1") (pintype "passive"))
      (node (ref "C52") (pin "1") (pinfunction "1_1") (pintype "passive"))
      (node (ref "C53") (pin "2") (pinfunction "2_2") (pintype "passive"))
      (node (ref "C54") (pin "2") (pinfunction "2_2") (pintype "passive"))
      (node (ref "C55") (pin "2") (pinfunction "2_2") (pintype "passive"))
      (node (ref "C56") (pin "2") (pinfunction "2_2") (pintype "passive"))
      (node (ref "C57") (pin "1") (pinfunction "1_1") (pintype "passive"))
      (node (ref "C59") (pin "2") (pinfunction "2_2") (pintype "passive"))
      (node (ref "C6") (pin "1") (pinfunction "1_1") (pintype "passive"))
      (node (ref "C64") (pin "-") (pinfunction "-_-") (pintype "passive"))
      (node (ref "C65") (pin "-") (pinfunction "-_-") (pintype "passive"))
      (node (ref "C66") (pin "-") (pinfunction "-_-") (pintype "passive"))
      (node (ref "C67") (pin "-") (pinfunction "-_-") (pintype "passive"))
      (node (ref "C68") (pin "-") (pinfunction "-_-") (pintype "passive"))
      (node (ref "C69") (pin "-") (pinfunction "-_-") (pintype "passive"))
      (node (ref "C70") (pin "-") (pinfunction "-_-") (pintype "passive"))
      (node (ref "C71") (pin "-") (pinfunction "-_-") (pintype "passive"))
      (node (ref "C72") (pin "-") (pinfunction "-_-") (pintype "passive"))
      (node (ref "C73") (pin "-") (pinfunction "-_-") (pintype "passive"))
      (node (ref "C74") (pin "1") (pinfunction "1_1") (pintype "passive"))
      (node (ref "C75") (pin "1") (pinfunction "1_1") (pintype "passive"))
      (node (ref "C76") (pin "2") (pinfunction "2_2") (pintype "passive"))
      (node (ref "C77") (pin "2") (pinfunction "2_2") (pintype "passive"))
      (node (ref "C78") (pin "2") (pinfunction "2_2") (pintype "passive"))
      (node (ref "C8") (pin "2") (pinfunction "2_2") (pintype "passive"))
      (node (ref "C9") (pin "2") (pinfunction "2_2") (pintype "passive"))
      (node (ref "C_AVDD_PT1") (pin "2") (pinfunction "2_2") (pintype "passive"))
      (node (ref "C_AVDD_PT2") (pin "2") (pinfunction "2_2") (pintype "passive"))
      (node (ref "C_AVDD_PT3") (pin "2") (pinfunction "2_2") (pintype "passive"))
      (node (ref "C_DVDD_PT1") (pin "2") (pinfunction "2_2") (pintype "passive"))
      (node (ref "C_DVDD_PT2") (pin "2") (pinfunction "2_2") (pintype "passive"))
      (node (ref "C_DVDD_PT3") (pin "2") (pinfunction "2_2") (pintype "passive"))
      (node (ref "C_ICM1_PT1") (pin "1") (pinfunction "1_1") (pintype "passive"))
      (node (ref "C_ICM1_PT2") (pin "1") (pinfunction "1_1") (pintype "passive"))
      (node (ref "C_ICM1_PT3") (pin "1") (pinfunction "1_1") (pintype "passive"))
      (node (ref "C_ICM2_PT1") (pin "2") (pinfunction "2_2") (pintype "passive"))
      (node (ref "C_ICM2_PT2") (pin "2") (pinfunction "2_2") (pintype "passive"))
      (node (ref "C_ICM2_PT3") (pin "2") (pinfunction "2_2") (pintype "passive"))
      (node (ref "C_RCM1_PT1") (pin "1") (pinfunction "1_1") (pintype "passive"))
      (node (ref "C_RCM1_PT2") (pin "1") (pinfunction "1_1") (pintype "passive"))
      (node (ref "C_RCM1_PT3") (pin "1") (pinfunction "1_1") (pintype "passive"))
      (node (ref "C_RCM2_PT1") (pin "2") (pinfunction "2_2") (pintype "passive"))
      (node (ref "C_RCM2_PT2") (pin "2") (pinfunction "2_2") (pintype "passive"))
      (node (ref "C_RCM2_PT3") (pin "2") (pinfunction "2_2") (pintype "passive"))
      (node (ref "C_VREF_PT1") (pin "2") (pinfunction "2_2") (pintype "passive"))
      (node (ref "C_VREF_PT2") (pin "2") (pinfunction "2_2") (pintype "passive"))
      (node (ref "C_VREF_PT3") (pin "2") (pinfunction "2_2") (pintype "passive"))
      (node (ref "D1") (pin "A") (pinfunction "A_A") (pintype "passive"))
      (node (ref "D10") (pin "A") (pinfunction "A_A") (pintype "passive"))
      (node (ref "D11") (pin "A") (pinfunction "A_A") (pintype "passive"))
      (node (ref "D12") (pin "A") (pinfunction "A_A") (pintype "passive"))
      (node (ref "D2") (pin "A") (pinfunction "A_A") (pintype "passive"))
      (node (ref "D3") (pin "A") (pinfunction "A_A") (pintype "passive"))
      (node (ref "D4") (pin "A") (pinfunction "A_A") (pintype "passive"))
      (node (ref "D7") (pin "A") (pinfunction "A_A") (pintype "passive"))
      (node (ref "D8") (pin "A") (pinfunction "A_A") (pintype "passive"))
      (node (ref "D9") (pin "A") (pinfunction "A_A") (pintype "passive"))
      (node (ref "JP_MS") (pin "1") (pinfunction "1_1") (pintype "passive"))
      (node (ref "LED1") (pin "C") (pinfunction "C_C") (pintype "passive"))
      (node (ref "LED2") (pin "C") (pinfunction "C_C") (pintype "passive"))
      (node (ref "LED3") (pin "C") (pinfunction "C_C") (pintype "passive"))
      (node (ref "LED4") (pin "C") (pinfunction "C_C") (pintype "passive"))
      (node (ref "LED5") (pin "C") (pinfunction "C_C") (pintype "passive"))
      (node (ref "LED6") (pin "C") (pinfunction "C_C") (pintype "passive"))
      (node (ref "R12") (pin "1") (pinfunction "1_1") (pintype "passive"))
      (node (ref "R23") (pin "1") (pinfunction "1_1") (pintype "passive"))
      (node (ref "R27") (pin "2") (pinfunction "2_2") (pintype "passive"))
      (node (ref "R35") (pin "2") (pinfunction "2_2") (pintype "passive"))
      (node (ref "R42") (pin "2") (pinfunction "2_2") (pintype "passive"))
      (node (ref "R49") (pin "2") (pinfunction "2_2") (pintype "passive"))
      (node (ref "R56") (pin "2") (pinfunction "2_2") (pintype "passive"))
      (node (ref "R63") (pin "2") (pinfunction "2_2") (pintype "passive"))
      (node (ref "R64") (pin "1") (pinfunction "1_1") (pintype "passive"))
      (node (ref "R66") (pin "1") (pinfunction "A_1") (pintype "passive"))
      (node (ref "R7") (pin "2") (pinfunction "2_2") (pintype "passive"))
      (node (ref "RN_B_PT1") (pin "4") (pinfunction "1_4") (pintype "passive"))
      (node (ref "RN_B_PT1") (pin "5") (pinfunction "2_5") (pintype "passive"))
      (node (ref "RN_B_PT2") (pin "4") (pinfunction "1_4") (pintype "passive"))
      (node (ref "RN_B_PT2") (pin "5") (pinfunction "2_5") (pintype "passive"))
      (node (ref "RN_B_PT3") (pin "4") (pinfunction "1_4") (pintype "passive"))
      (node (ref "RN_B_PT3") (pin "5") (pinfunction "2_5") (pintype "passive"))
      (node (ref "R_R2_PT1") (pin "2") (pinfunction "2_2") (pintype "passive"))
      (node (ref "R_R2_PT2") (pin "2") (pinfunction "2_2") (pintype "passive"))
      (node (ref "R_R2_PT3") (pin "2") (pinfunction "2_2") (pintype "passive"))
      (node (ref "R_REF_PT1") (pin "1") (pinfunction "1_1") (pintype "passive"))
      (node (ref "R_REF_PT2") (pin "1") (pinfunction "1_1") (pintype "passive"))
      (node (ref "R_REF_PT3") (pin "1") (pinfunction "1_1") (pintype "passive"))
      (node (ref "SJ_MS") (pin "1") (pinfunction "1_1") (pintype "passive"))
      (node (ref "U$1") (pin "P$6") (pinfunction "6_P$6") (pintype "passive"))
      (node (ref "U$2") (pin "P$6") (pinfunction "6_P$6") (pintype "passive"))
      (node (ref "U$3") (pin "P$6") (pinfunction "6_P$6") (pintype "passive"))
      (node (ref "U$4") (pin "P$6") (pinfunction "6_P$6") (pintype "passive"))
      (node (ref "U$5") (pin "P$6") (pinfunction "6_P$6") (pintype "passive"))
      (node (ref "U$6") (pin "P$6") (pinfunction "6_P$6") (pintype "passive"))
      (node (ref "U$7") (pin "6") (pinfunction "VSS_6") (pintype "power_in"))
      (node (ref "U$7") (pin "MT1") (pinfunction "GND_MT1") (pintype "power_in"))
      (node (ref "U$7") (pin "MT2") (pinfunction "GND1_MT2") (pintype "power_in"))
      (node (ref "U$8") (pin "GND") (pinfunction "GND_GND") (pintype "bidirectional"))
      (node (ref "U$9") (pin "GND") (pinfunction "GND_GND") (pintype "bidirectional"))
      (node (ref "U_ADC_DMS1") (pin "13") (pinfunction "AVSS_13") (pintype "bidirectional"))
      (node (ref "U_ADC_DMS1") (pin "2") (pinfunction "DGND/DSS_2") (pintype "bidirectional"))
      (node (ref "U_ADC_DMS1") (pin "3") (pinfunction "CLK_3") (pintype "bidirectional"))
      (node (ref "U_ADC_DMS1") (pin "8") (pinfunction "VREFCOM_8") (pintype "bidirectional"))
      (node (ref "U_ADC_DMS2") (pin "13") (pinfunction "AVSS_13") (pintype "bidirectional"))
      (node (ref "U_ADC_DMS2") (pin "2") (pinfunction "DGND/DSS_2") (pintype "bidirectional"))
      (node (ref "U_ADC_DMS2") (pin "3") (pinfunction "CLK_3") (pintype "bidirectional"))
      (node (ref "U_ADC_DMS2") (pin "8") (pinfunction "VREFCOM_8") (pintype "bidirectional"))
      (node (ref "U_ADC_DMS3") (pin "13") (pinfunction "AVSS_13") (pintype "bidirectional"))
      (node (ref "U_ADC_DMS3") (pin "2") (pinfunction "DGND/DSS_2") (pintype "bidirectional"))
      (node (ref "U_ADC_DMS3") (pin "3") (pinfunction "CLK_3") (pintype "bidirectional"))
      (node (ref "U_ADC_DMS3") (pin "8") (pinfunction "VREFCOM_8") (pintype "bidirectional"))
      (node (ref "U_ADC_DMS4") (pin "13") (pinfunction "AVSS_13") (pintype "bidirectional"))
      (node (ref "U_ADC_DMS4") (pin "2") (pinfunction "DGND/DSS_2") (pintype "bidirectional"))
      (node (ref "U_ADC_DMS4") (pin "3") (pinfunction "CLK_3") (pintype "bidirectional"))
      (node (ref "U_ADC_DMS4") (pin "8") (pinfunction "VREFCOM_8") (pintype "bidirectional"))
      (node (ref "U_ADC_DMS5") (pin "13") (pinfunction "AVSS_13") (pintype "bidirectional"))
      (node (ref "U_ADC_DMS5") (pin "2") (pinfunction "DGND/DSS_2") (pintype "bidirectional"))
      (node (ref "U_ADC_DMS5") (pin "3") (pinfunction "CLK_3") (pintype "bidirectional"))
      (node (ref "U_ADC_DMS5") (pin "8") (pinfunction "VREFCOM_8") (pintype "bidirectional"))
      (node (ref "U_ADC_DMS6") (pin "13") (pinfunction "AVSS_13") (pintype "bidirectional"))
      (node (ref "U_ADC_DMS6") (pin "2") (pinfunction "DGND/DSS_2") (pintype "bidirectional"))
      (node (ref "U_ADC_DMS6") (pin "3") (pinfunction "CLK_3") (pintype "bidirectional"))
      (node (ref "U_ADC_DMS6") (pin "8") (pinfunction "VREFCOM_8") (pintype "bidirectional"))
      (node (ref "U_ADC_PT1") (pin "13") (pinfunction "AVSS_13") (pintype "bidirectional"))
      (node (ref "U_ADC_PT1") (pin "2") (pinfunction "DGND/DSS_2") (pintype "bidirectional"))
      (node (ref "U_ADC_PT1") (pin "3") (pinfunction "CLK_3") (pintype "bidirectional"))
      (node (ref "U_ADC_PT1") (pin "8") (pinfunction "VREFCOM_8") (pintype "bidirectional"))
      (node (ref "U_ADC_PT2") (pin "13") (pinfunction "AVSS_13") (pintype "bidirectional"))
      (node (ref "U_ADC_PT2") (pin "2") (pinfunction "DGND/DSS_2") (pintype "bidirectional"))
      (node (ref "U_ADC_PT2") (pin "3") (pinfunction "CLK_3") (pintype "bidirectional"))
      (node (ref "U_ADC_PT2") (pin "8") (pinfunction "VREFCOM_8") (pintype "bidirectional"))
      (node (ref "U_ADC_PT3") (pin "13") (pinfunction "AVSS_13") (pintype "bidirectional"))
      (node (ref "U_ADC_PT3") (pin "2") (pinfunction "DGND/DSS_2") (pintype "bidirectional"))
      (node (ref "U_ADC_PT3") (pin "3") (pinfunction "CLK_3") (pintype "bidirectional"))
      (node (ref "U_ADC_PT3") (pin "8") (pinfunction "VREFCOM_8") (pintype "bidirectional"))
      (node (ref "U_ADR366_3") (pin "2") (pinfunction "GND_2") (pintype "power_in"))
      (node (ref "U_CH340G") (pin "1") (pinfunction "GND_1") (pintype "bidirectional"))
      (node (ref "U_FLASH1") (pin "10") (pinfunction "VSS_10") (pintype "bidirectional"))
      (node (ref "U_FLASH2") (pin "10") (pinfunction "VSS_10") (pintype "bidirectional"))
      (node (ref "U_LT1528") (pin "3") (pinfunction "GND_3") (pintype "bidirectional"))
      (node (ref "U_LT1528") (pin "6") (pinfunction "GND_6") (pintype "bidirectional"))
      (node (ref "U_OPTO_1") (pin "5") (pinfunction "EMT2_5") (pintype "output"))
      (node (ref "U_OPTO_1") (pin "7") (pinfunction "EMT1_7") (pintype "output"))
      (node (ref "U_OPTO_2") (pin "5") (pinfunction "EMT2_5") (pintype "output"))
      (node (ref "U_OPTO_2") (pin "7") (pinfunction "EMT1_7") (pintype "output"))
      (node (ref "U_OPTO_3") (pin "7") (pinfunction "EMT1_7") (pintype "output"))
      (node (ref "U_STM32F779") (pin "114") (pinfunction "VSS_114") (pintype "bidirectional"))
      (node (ref "U_STM32F779") (pin "122") (pinfunction "VSSDSI_122") (pintype "bidirectional"))
      (node (ref "U_STM32F779") (pin "128") (pinfunction "VSSDSI2_128") (pintype "bidirectional"))
      (node (ref "U_STM32F779") (pin "136") (pinfunction "VSS_136") (pintype "bidirectional"))
      (node (ref "U_STM32F779") (pin "14") (pinfunction "VSS_14") (pintype "bidirectional"))
      (node (ref "U_STM32F779") (pin "149") (pinfunction "VSS_149") (pintype "bidirectional"))
      (node (ref "U_STM32F779") (pin "170") (pinfunction "VSS_170") (pintype "bidirectional"))
      (node (ref "U_STM32F779") (pin "184") (pinfunction "VSS_184") (pintype "bidirectional"))
      (node (ref "U_STM32F779") (pin "202") (pinfunction "VSS_202") (pintype "bidirectional"))
      (node (ref "U_STM32F779") (pin "25") (pinfunction "VSS_25") (pintype "bidirectional"))
      (node (ref "U_STM32F779") (pin "40") (pinfunction "VSSA_40") (pintype "bidirectional"))
      (node (ref "U_STM32F779") (pin "51") (pinfunction "VSS_51") (pintype "bidirectional"))
      (node (ref "U_STM32F779") (pin "60") (pinfunction "VSS_60") (pintype "bidirectional"))
      (node (ref "U_STM32F779") (pin "72") (pinfunction "VSS_72") (pintype "bidirectional"))
      (node (ref "U_STM32F779") (pin "82") (pinfunction "VSS_82") (pintype "bidirectional"))
      (node (ref "U_STM32F779") (pin "93") (pinfunction "VSS_93") (pintype "bidirectional"))
      (node (ref "U_TRACODCDC") (pin "5") (pinfunction "-VOUT_5") (pintype "passive"))
      (node (ref "X_DMS") (pin "P$A10") (pinfunction "A10_P$A10") (pintype "passive"))
      (node (ref "X_DMS") (pin "P$B10") (pinfunction "B10_P$B10") (pintype "passive"))
      (node (ref "X_GPIO") (pin "P$A1") (pinfunction "A1_P$A1") (pintype "passive"))
      (node (ref "X_GPIO") (pin "P$A2") (pinfunction "A2_P$A2") (pintype "passive"))
      (node (ref "X_MIRROR") (pin "P$A8") (pinfunction "A8_P$A8") (pintype "passive"))
      (node (ref "X_MIRROR") (pin "P$B10") (pinfunction "B10_P$B10") (pintype "passive"))
      (node (ref "X_MIRROR") (pin "P$B11") (pinfunction "B11_P$B11") (pintype "passive"))
      (node (ref "X_MIRROR") (pin "P$B12") (pinfunction "B12_P$B12") (pintype "passive"))
      (node (ref "X_MIRROR") (pin "P$B13") (pinfunction "B13_P$B13") (pintype "passive"))
      (node (ref "X_MIRROR") (pin "P$B8") (pinfunction "B8_P$B8") (pintype "passive"))
      (node (ref "X_MIRROR") (pin "P$B9") (pinfunction "B9_P$B9") (pintype "passive"))
      (node (ref "X_MIRROR1") (pin "P$A6") (pinfunction "A6_P$A6") (pintype "passive"))
      (node (ref "X_MIRROR1") (pin "P$B1") (pinfunction "B1_P$B1") (pintype "passive"))
      (node (ref "X_MIRROR1") (pin "P$B2") (pinfunction "B2_P$B2") (pintype "passive"))
      (node (ref "X_MIRROR1") (pin "P$B3") (pinfunction "B3_P$B3") (pintype "passive"))
      (node (ref "X_MIRROR1") (pin "P$B4") (pinfunction "B4_P$B4") (pintype "passive"))
      (node (ref "X_MIRROR1") (pin "P$B5") (pinfunction "B5_P$B5") (pintype "passive"))
      (node (ref "X_MIRROR1") (pin "P$B6") (pinfunction "B6_P$B6") (pintype "passive"))
      (node (ref "X_PROG") (pin "10") (pinfunction "10_10") (pintype "passive"))
      (node (ref "X_PROG") (pin "12") (pinfunction "12_12") (pintype "passive"))
      (node (ref "X_PROG") (pin "14") (pinfunction "14_14") (pintype "passive"))
      (node (ref "X_PROG") (pin "16") (pinfunction "16_16") (pintype "passive"))
      (node (ref "X_PROG") (pin "18") (pinfunction "18_18") (pintype "passive"))
      (node (ref "X_PROG") (pin "20") (pinfunction "20_20") (pintype "passive"))
      (node (ref "X_PROG") (pin "4") (pinfunction "4_4") (pintype "passive"))
      (node (ref "X_PROG") (pin "6") (pinfunction "6_6") (pintype "passive"))
      (node (ref "X_PROG") (pin "8") (pinfunction "8_8") (pintype "passive"))
      (node (ref "X_PT") (pin "P$A4") (pinfunction "A4_P$A4") (pintype "passive"))
      (node (ref "X_PT") (pin "P$A5") (pinfunction "A5_P$A5") (pintype "passive"))
      (node (ref "X_PT") (pin "P$A6") (pinfunction "A6_P$A6") (pintype "passive"))
      (node (ref "X_PT") (pin "P$BL1") (pinfunction "CASE_P$BL1") (pintype "passive"))
      (node (ref "X_PT") (pin "P$BL2") (pinfunction "CASE_P$BL2") (pintype "passive"))
      (node (ref "X_PT") (pin "P$BL3") (pinfunction "CASE_P$BL3") (pintype "passive"))
      (node (ref "X_PT") (pin "P$BL4") (pinfunction "CASE_P$BL4") (pintype "passive"))
      (node (ref "X_RXSM-DAPI") (pin "P$A10") (pinfunction "A10_P$A10") (pintype "passive"))
    )
    (net (code "49") (name "INTERSPU_RX") (class "Default")
      (node (ref "D11") (pin "C") (pinfunction "C_C") (pintype "passive"))
      (node (ref "U_STM32F779") (pin "166") (pinfunction "PD2_166") (pintype "bidirectional"))
      (node (ref "X_MIRROR") (pin "P$A9") (pinfunction "A9_P$A9") (pintype "passive"))
      (node (ref "X_MIRROR1") (pin "P$A4") (pinfunction "A4_P$A4") (pintype "passive"))
    )
    (net (code "50") (name "INTERSPU_TX") (class "Default")
      (node (ref "D12") (pin "C") (pinfunction "C_C") (pintype "passive"))
      (node (ref "U_STM32F779") (pin "163") (pinfunction "PC12_163") (pintype "bidirectional"))
      (node (ref "X_MIRROR") (pin "P$A10") (pinfunction "A10_P$A10") (pintype "passive"))
      (node (ref "X_MIRROR1") (pin "P$A5") (pinfunction "A5_P$A5") (pintype "passive"))
    )
    (net (code "51") (name "IO1") (class "Default")
      (node (ref "U_STM32F779") (pin "50") (pinfunction "PA3_50") (pintype "bidirectional"))
      (node (ref "X_GPIO") (pin "P$A10") (pinfunction "A10_P$A10") (pintype "passive"))
    )
    (net (code "52") (name "IO2") (class "Default")
      (node (ref "U_STM32F779") (pin "49") (pinfunction "PH5_49") (pintype "bidirectional"))
      (node (ref "X_GPIO") (pin "P$A9") (pinfunction "A9_P$A9") (pintype "passive"))
    )
    (net (code "53") (name "IO3") (class "Default")
      (node (ref "U_STM32F779") (pin "48") (pinfunction "PH4_48") (pintype "bidirectional"))
      (node (ref "X_GPIO") (pin "P$A8") (pinfunction "A8_P$A8") (pintype "passive"))
    )
    (net (code "54") (name "IO4") (class "Default")
      (node (ref "U_STM32F779") (pin "47") (pinfunction "PH3_47") (pintype "bidirectional"))
      (node (ref "X_GPIO") (pin "P$A7") (pinfunction "A7_P$A7") (pintype "passive"))
    )
    (net (code "55") (name "IO5") (class "Default")
      (node (ref "U_STM32F779") (pin "38") (pinfunction "PC3_38") (pintype "bidirectional"))
      (node (ref "X_GPIO") (pin "P$A6") (pinfunction "A6_P$A6") (pintype "passive"))
    )
    (net (code "56") (name "IO6") (class "Default")
      (node (ref "U_STM32F779") (pin "37") (pinfunction "PC2_37") (pintype "bidirectional"))
      (node (ref "X_GPIO") (pin "P$A5") (pinfunction "A5_P$A5") (pintype "passive"))
    )
    (net (code "57") (name "IO7") (class "Default")
      (node (ref "U_STM32F779") (pin "36") (pinfunction "PC1_36") (pintype "bidirectional"))
      (node (ref "X_GPIO") (pin "P$A4") (pinfunction "A4_P$A4") (pintype "passive"))
    )
    (net (code "58") (name "IO8") (class "Default")
      (node (ref "U_STM32F779") (pin "35") (pinfunction "PC0_35") (pintype "bidirectional"))
      (node (ref "X_GPIO") (pin "P$A3") (pinfunction "A3_P$A3") (pintype "passive"))
    )
    (net (code "59") (name "LED_1") (class "Default")
      (node (ref "RN10") (pin "1") (pinfunction "1_1") (pintype "passive"))
      (node (ref "U_STM32F779") (pin "24") (pinfunction "PF5_24") (pintype "bidirectional"))
    )
    (net (code "60") (name "LED_2") (class "Default")
      (node (ref "RN10") (pin "2") (pinfunction "1_2") (pintype "passive"))
      (node (ref "U_STM32F779") (pin "23") (pinfunction "PF4_23") (pintype "bidirectional"))
    )
    (net (code "61") (name "LED_3") (class "Default")
      (node (ref "RN10") (pin "3") (pinfunction "1_3") (pintype "passive"))
      (node (ref "U_STM32F779") (pin "22") (pinfunction "PF3_22") (pintype "bidirectional"))
    )
    (net (code "62") (name "LED_4") (class "Default")
      (node (ref "RN10") (pin "4") (pinfunction "1_4") (pintype "passive"))
      (node (ref "U_STM32F779") (pin "21") (pinfunction "PI14_21") (pintype "bidirectional"))
    )
    (net (code "63") (name "LO") (class "Default")
      (node (ref "U_OPTO_2") (pin "2") (pinfunction "C1_2") (pintype "bidirectional"))
      (node (ref "X_MIRROR") (pin "P$A5") (pinfunction "A5_P$A5") (pintype "passive"))
      (node (ref "X_MIRROR1") (pin "P$A9") (pinfunction "A9_P$A9") (pintype "passive"))
      (node (ref "X_RXSM-DAPI") (pin "P$A5") (pinfunction "A5_P$A5") (pintype "passive"))
    )
    (net (code "64") (name "LO_OPT") (class "Default")
      (node (ref "D7") (pin "C") (pinfunction "C_C") (pintype "passive"))
      (node (ref "RN12") (pin "6") (pinfunction "2_6") (pintype "passive"))
      (node (ref "U_OPTO_2") (pin "8") (pinfunction "COL1_8") (pintype "input"))
      (node (ref "U_STM32F779") (pin "208") (pinfunction "PI7_208") (pintype "bidirectional"))
    )
    (net (code "65") (name "LWL_IN") (class "Default")
      (node (ref "U$9") (pin "VOUT") (pinfunction "VOUT_VOUT") (pintype "bidirectional"))
      (node (ref "U_STM32F779") (pin "7") (pinfunction "PI8_7") (pintype "bidirectional"))
    )
    (net (code "66") (name "LWL_OUT") (class "Default")
      (node (ref "U$8") (pin "VIN") (pinfunction "VIN_VIN") (pintype "bidirectional"))
      (node (ref "U_STM32F779") (pin "157") (pinfunction "PI3_157") (pintype "bidirectional"))
    )
    (net (code "67") (name "MS_SEL") (class "Default")
      (node (ref "JP_MS") (pin "2") (pinfunction "2_2") (pintype "passive"))
      (node (ref "R29") (pin "1") (pinfunction "1_1") (pintype "passive"))
      (node (ref "SJ_MS") (pin "2") (pinfunction "2_2") (pintype "passive"))
      (node (ref "U_STM32F779") (pin "129") (pinfunction "PG2_129") (pintype "bidirectional"))
    )
    (net (code "68") (name "NRST") (class "Default")
      (node (ref "C18") (pin "1") (pinfunction "1_1") (pintype "passive"))
      (node (ref "JP1") (pin "1") (pinfunction "1_1") (pintype "passive"))
      (node (ref "R26") (pin "1") (pinfunction "1_1") (pintype "passive"))
      (node (ref "U_STM32F779") (pin "34") (pinfunction "NRST_34") (pintype "bidirectional"))
      (node (ref "X_PROG") (pin "15") (pinfunction "15_15") (pintype "passive"))
    )
    (net (code "69") (name "Net-(C44-Pad1)") (class "Default")
      (node (ref "C44") (pin "1") (pinfunction "1_1") (pintype "passive"))
      (node (ref "R10") (pin "1") (pinfunction "1_1") (pintype "passive"))
      (node (ref "R15") (pin "2") (pinfunction "2_2") (pintype "passive"))
    )
    (net (code "70") (name "Net-(LED5-PadA)") (class "Default")
      (node (ref "LED5") (pin "A") (pinfunction "A_A") (pintype "passive"))
      (node (ref "R18") (pin "1") (pinfunction "1_1") (pintype "passive"))
    )
    (net (code "71") (name "Net-(LED6-PadA)") (class "Default")
      (node (ref "LED6") (pin "A") (pinfunction "A_A") (pintype "passive"))
      (node (ref "R19") (pin "1") (pinfunction "1_1") (pintype "passive"))
    )
    (net (code "72") (name "Net-(LED7-PadA)") (class "Default")
      (node (ref "LED7") (pin "A") (pinfunction "A_A") (pintype "passive"))
      (node (ref "R20") (pin "1") (pinfunction "1_1") (pintype "passive"))
    )
    (net (code "73") (name "Net-(LED8-PadA)") (class "Default")
      (node (ref "LED8") (pin "A") (pinfunction "A_A") (pintype "passive"))
      (node (ref "R21") (pin "1") (pinfunction "1_1") (pintype "passive"))
    )
    (net (code "74") (name "Net-(R5-Pad2)") (class "Default")
      (node (ref "R5") (pin "2") (pinfunction "2_2") (pintype "passive"))
      (node (ref "R6") (pin "1") (pinfunction "1_1") (pintype "passive"))
      (node (ref "R7") (pin "1") (pinfunction "1_1") (pintype "passive"))
    )
    (net (code "75") (name "Net-(R22-Pad2)") (class "Default")
      (node (ref "R22") (pin "2") (pinfunction "2_2") (pintype "passive"))
      (node (ref "R24") (pin "1") (pinfunction "1_1") (pintype "passive"))
      (node (ref "R25") (pin "2") (pinfunction "2_2") (pintype "passive"))
    )
    (net (code "76") (name "Net-(R23-Pad2)") (class "Default")
      (node (ref "R23") (pin "2") (pinfunction "2_2") (pintype "passive"))
      (node (ref "R25") (pin "1") (pinfunction "1_1") (pintype "passive"))
    )
    (net (code "77") (name "Net-(R33-Pad2)") (class "Default")
      (node (ref "R33") (pin "2") (pinfunction "2_2") (pintype "passive"))
      (node (ref "R34") (pin "1") (pinfunction "1_1") (pintype "passive"))
      (node (ref "R35") (pin "1") (pinfunction "1_1") (pintype "passive"))
    )
    (net (code "78") (name "Net-(R40-Pad2)") (class "Default")
      (node (ref "R40") (pin "2") (pinfunction "2_2") (pintype "passive"))
      (node (ref "R41") (pin "1") (pinfunction "1_1") (pintype "passive"))
      (node (ref "R42") (pin "1") (pinfunction "1_1") (pintype "passive"))
    )
    (net (code "79") (name "Net-(R47-Pad2)") (class "Default")
      (node (ref "R47") (pin "2") (pinfunction "2_2") (pintype "passive"))
      (node (ref "R48") (pin "1") (pinfunction "1_1") (pintype "passive"))
      (node (ref "R49") (pin "1") (pinfunction "1_1") (pintype "passive"))
    )
    (net (code "80") (name "Net-(R54-Pad2)") (class "Default")
      (node (ref "R54") (pin "2") (pinfunction "2_2") (pintype "passive"))
      (node (ref "R55") (pin "1") (pinfunction "1_1") (pintype "passive"))
      (node (ref "R56") (pin "1") (pinfunction "1_1") (pintype "passive"))
    )
    (net (code "81") (name "Net-(R61-Pad2)") (class "Default")
      (node (ref "R61") (pin "2") (pinfunction "2_2") (pintype "passive"))
      (node (ref "R62") (pin "1") (pinfunction "1_1") (pintype "passive"))
      (node (ref "R63") (pin "1") (pinfunction "1_1") (pintype "passive"))
    )
    (net (code "82") (name "Net-(R66-S)") (class "Default")
      (node (ref "R64") (pin "2") (pinfunction "2_2") (pintype "passive"))
      (node (ref "R65") (pin "2") (pinfunction "2_2") (pintype "passive"))
      (node (ref "R66") (pin "2") (pinfunction "S_2") (pintype "passive"))
      (node (ref "U_TRACODCDC") (pin "4") (pinfunction "TRIM_4") (pintype "input"))
    )
    (net (code "83") (name "Net-(RN10A-2)") (class "Default")
      (node (ref "LED1") (pin "A") (pinfunction "A_A") (pintype "passive"))
      (node (ref "RN10") (pin "8") (pinfunction "2_8") (pintype "passive"))
    )
    (net (code "84") (name "Net-(RN10B-2)") (class "Default")
      (node (ref "LED2") (pin "A") (pinfunction "A_A") (pintype "passive"))
      (node (ref "RN10") (pin "7") (pinfunction "2_7") (pintype "passive"))
    )
    (net (code "85") (name "Net-(RN10C-2)") (class "Default")
      (node (ref "LED3") (pin "A") (pinfunction "A_A") (pintype "passive"))
      (node (ref "RN10") (pin "6") (pinfunction "2_6") (pintype "passive"))
    )
    (net (code "86") (name "Net-(RN10D-2)") (class "Default")
      (node (ref "LED4") (pin "A") (pinfunction "A_A") (pintype "passive"))
      (node (ref "RN10") (pin "5") (pinfunction "2_5") (pintype "passive"))
    )
    (net (code "87") (name "Net-(RN11A-2)") (class "Default")
      (node (ref "RN11") (pin "8") (pinfunction "2_8") (pintype "passive"))
      (node (ref "U_OPTO_2") (pin "1") (pinfunction "A1_1") (pintype "bidirectional"))
    )
    (net (code "88") (name "Net-(RN11B-2)") (class "Default")
      (node (ref "RN11") (pin "7") (pinfunction "2_7") (pintype "passive"))
      (node (ref "U_OPTO_2") (pin "3") (pinfunction "A2_3") (pintype "bidirectional"))
    )
    (net (code "89") (name "Net-(RN11C-2)") (class "Default")
      (node (ref "RN11") (pin "6") (pinfunction "2_6") (pintype "passive"))
      (node (ref "U_OPTO_1") (pin "1") (pinfunction "A1_1") (pintype "bidirectional"))
    )
    (net (code "90") (name "Net-(RN11D-2)") (class "Default")
      (node (ref "RN11") (pin "5") (pinfunction "2_5") (pintype "passive"))
      (node (ref "U_OPTO_1") (pin "3") (pinfunction "A2_3") (pintype "bidirectional"))
    )
    (net (code "91") (name "Net-(RN12D-2)") (class "Default")
      (node (ref "RN12") (pin "5") (pinfunction "2_5") (pintype "passive"))
      (node (ref "U_OPTO_2") (pin "6") (pinfunction "COL2_6") (pintype "input"))
    )
    (net (code "92") (name "Net-(RN_A_PT1B-1)") (class "Default")
      (node (ref "RN_A_PT1") (pin "2") (pinfunction "1_2") (pintype "passive"))
      (node (ref "U_ADC_PT1") (pin "20") (pinfunction "SCLK_20") (pintype "bidirectional"))
    )
    (net (code "93") (name "Net-(RN_A_PT1C-1)") (class "Default")
      (node (ref "RN_A_PT1") (pin "3") (pinfunction "1_3") (pintype "passive"))
      (node (ref "U_ADC_PT1") (pin "19") (pinfunction "DIN_19") (pintype "bidirectional"))
    )
    (net (code "94") (name "Net-(RN_A_PT1D-1)") (class "Default")
      (node (ref "RN_A_PT1") (pin "4") (pinfunction "1_4") (pintype "passive"))
      (node (ref "U_ADC_PT1") (pin "18") (pinfunction "DOUT/~{DRDY}_18") (pintype "bidirectional"))
    )
    (net (code "95") (name "Net-(RN_A_PT2B-1)") (class "Default")
      (node (ref "RN_A_PT2") (pin "2") (pinfunction "1_2") (pintype "passive"))
      (node (ref "U_ADC_PT2") (pin "20") (pinfunction "SCLK_20") (pintype "bidirectional"))
    )
    (net (code "96") (name "Net-(RN_A_PT2C-1)") (class "Default")
      (node (ref "RN_A_PT2") (pin "3") (pinfunction "1_3") (pintype "passive"))
      (node (ref "U_ADC_PT2") (pin "19") (pinfunction "DIN_19") (pintype "bidirectional"))
    )
    (net (code "97") (name "Net-(RN_A_PT2D-1)") (class "Default")
      (node (ref "RN_A_PT2") (pin "4") (pinfunction "1_4") (pintype "passive"))
      (node (ref "U_ADC_PT2") (pin "18") (pinfunction "DOUT/~{DRDY}_18") (pintype "bidirectional"))
    )
    (net (code "98") (name "Net-(RN_A_PT3B-1)") (class "Default")
      (node (ref "RN_A_PT3") (pin "2") (pinfunction "1_2") (pintype "passive"))
      (node (ref "U_ADC_PT3") (pin "20") (pinfunction "SCLK_20") (pintype "bidirectional"))
    )
    (net (code "99") (name "Net-(RN_A_PT3C-1)") (class "Default")
      (node (ref "RN_A_PT3") (pin "3") (pinfunction "1_3") (pintype "passive"))
      (node (ref "U_ADC_PT3") (pin "19") (pinfunction "DIN_19") (pintype "bidirectional"))
    )
    (net (code "100") (name "Net-(RN_A_PT3D-1)") (class "Default")
      (node (ref "RN_A_PT3") (pin "4") (pinfunction "1_4") (pintype "passive"))
      (node (ref "U_ADC_PT3") (pin "18") (pinfunction "DOUT/~{DRDY}_18") (pintype "bidirectional"))
    )
    (net (code "101") (name "Net-(RN_B_PT1B-1)") (class "Default")
      (node (ref "RN_B_PT1") (pin "2") (pinfunction "1_2") (pintype "passive"))
      (node (ref "U_ADC_PT1") (pin "16") (pinfunction "~{CS}_16") (pintype "bidirectional"))
    )
    (net (code "102") (name "Net-(RN_B_PT1C-1)") (class "Default")
      (node (ref "RN_B_PT1") (pin "3") (pinfunction "1_3") (pintype "passive"))
      (node (ref "U_ADC_PT1") (pin "15") (pinfunction "START_15") (pintype "bidirectional"))
    )
    (net (code "103") (name "Net-(RN_B_PT2B-1)") (class "Default")
      (node (ref "RN_B_PT2") (pin "2") (pinfunction "1_2") (pintype "passive"))
      (node (ref "U_ADC_PT2") (pin "16") (pinfunction "~{CS}_16") (pintype "bidirectional"))
    )
    (net (code "104") (name "Net-(RN_B_PT2C-1)") (class "Default")
      (node (ref "RN_B_PT2") (pin "3") (pinfunction "1_3") (pintype "passive"))
      (node (ref "U_ADC_PT2") (pin "15") (pinfunction "START_15") (pintype "bidirectional"))
    )
    (net (code "105") (name "Net-(RN_B_PT3B-1)") (class "Default")
      (node (ref "RN_B_PT3") (pin "2") (pinfunction "1_2") (pintype "passive"))
      (node (ref "U_ADC_PT3") (pin "16") (pinfunction "~{CS}_16") (pintype "bidirectional"))
    )
    (net (code "106") (name "Net-(RN_B_PT3C-1)") (class "Default")
      (node (ref "RN_B_PT3") (pin "3") (pinfunction "1_3") (pintype "passive"))
      (node (ref "U_ADC_PT3") (pin "15") (pinfunction "START_15") (pintype "bidirectional"))
    )
    (net (code "107") (name "Net-(RN_DMS1B-1)") (class "Default")
      (node (ref "RN_DMS1") (pin "2") (pinfunction "1_2") (pintype "passive"))
      (node (ref "U_ADC_DMS1") (pin "19") (pinfunction "DIN_19") (pintype "bidirectional"))
    )
    (net (code "108") (name "Net-(RN_DMS1C-1)") (class "Default")
      (node (ref "RN_DMS1") (pin "3") (pinfunction "1_3") (pintype "passive"))
      (node (ref "U_ADC_DMS1") (pin "18") (pinfunction "DOUT/~{DRDY}_18") (pintype "bidirectional"))
    )
    (net (code "109") (name "Net-(RN_DMS1D-1)") (class "Default")
      (node (ref "RN_DMS1") (pin "4") (pinfunction "1_4") (pintype "passive"))
      (node (ref "U_ADC_DMS1") (pin "17") (pinfunction "~{DRDY}_17") (pintype "bidirectional"))
    )
    (net (code "110") (name "Net-(RN_DMS2B-1)") (class "Default")
      (node (ref "RN_DMS2") (pin "2") (pinfunction "1_2") (pintype "passive"))
      (node (ref "U_ADC_DMS2") (pin "19") (pinfunction "DIN_19") (pintype "bidirectional"))
    )
    (net (code "111") (name "Net-(RN_DMS2C-1)") (class "Default")
      (node (ref "RN_DMS2") (pin "3") (pinfunction "1_3") (pintype "passive"))
      (node (ref "U_ADC_DMS2") (pin "18") (pinfunction "DOUT/~{DRDY}_18") (pintype "bidirectional"))
    )
    (net (code "112") (name "Net-(RN_DMS2D-1)") (class "Default")
      (node (ref "RN_DMS2") (pin "4") (pinfunction "1_4") (pintype "passive"))
      (node (ref "U_ADC_DMS2") (pin "17") (pinfunction "~{DRDY}_17") (pintype "bidirectional"))
    )
    (net (code "113") (name "Net-(RN_DMS3B-1)") (class "Default")
      (node (ref "RN_DMS3") (pin "2") (pinfunction "1_2") (pintype "passive"))
      (node (ref "U_ADC_DMS3") (pin "19") (pinfunction "DIN_19") (pintype "bidirectional"))
    )
    (net (code "114") (name "Net-(RN_DMS3C-1)") (class "Default")
      (node (ref "RN_DMS3") (pin "3") (pinfunction "1_3") (pintype "passive"))
      (node (ref "U_ADC_DMS3") (pin "18") (pinfunction "DOUT/~{DRDY}_18") (pintype "bidirectional"))
    )
    (net (code "115") (name "Net-(RN_DMS3D-1)") (class "Default")
      (node (ref "RN_DMS3") (pin "4") (pinfunction "1_4") (pintype "passive"))
      (node (ref "U_ADC_DMS3") (pin "17") (pinfunction "~{DRDY}_17") (pintype "bidirectional"))
    )
    (net (code "116") (name "Net-(RN_DMS4B-1)") (class "Default")
      (node (ref "RN_DMS4") (pin "2") (pinfunction "1_2") (pintype "passive"))
      (node (ref "U_ADC_DMS4") (pin "19") (pinfunction "DIN_19") (pintype "bidirectional"))
    )
    (net (code "117") (name "Net-(RN_DMS4C-1)") (class "Default")
      (node (ref "RN_DMS4") (pin "3") (pinfunction "1_3") (pintype "passive"))
      (node (ref "U_ADC_DMS4") (pin "18") (pinfunction "DOUT/~{DRDY}_18") (pintype "bidirectional"))
    )
    (net (code "118") (name "Net-(RN_DMS4D-1)") (class "Default")
      (node (ref "RN_DMS4") (pin "4") (pinfunction "1_4") (pintype "passive"))
      (node (ref "U_ADC_DMS4") (pin "17") (pinfunction "~{DRDY}_17") (pintype "bidirectional"))
    )
    (net (code "119") (name "Net-(RN_DMS5B-1)") (class "Default")
      (node (ref "RN_DMS5") (pin "2") (pinfunction "1_2") (pintype "passive"))
      (node (ref "U_ADC_DMS5") (pin "19") (pinfunction "DIN_19") (pintype "bidirectional"))
    )
    (net (code "120") (name "Net-(RN_DMS5C-1)") (class "Default")
      (node (ref "RN_DMS5") (pin "3") (pinfunction "1_3") (pintype "passive"))
      (node (ref "U_ADC_DMS5") (pin "18") (pinfunction "DOUT/~{DRDY}_18") (pintype "bidirectional"))
    )
    (net (code "121") (name "Net-(RN_DMS5D-1)") (class "Default")
      (node (ref "RN_DMS5") (pin "4") (pinfunction "1_4") (pintype "passive"))
      (node (ref "U_ADC_DMS5") (pin "17") (pinfunction "~{DRDY}_17") (pintype "bidirectional"))
    )
    (net (code "122") (name "Net-(RN_DMS6B-1)") (class "Default")
      (node (ref "RN_DMS6") (pin "2") (pinfunction "1_2") (pintype "passive"))
      (node (ref "U_ADC_DMS6") (pin "19") (pinfunction "DIN_19") (pintype "bidirectional"))
    )
    (net (code "123") (name "Net-(RN_DMS6C-1)") (class "Default")
      (node (ref "RN_DMS6") (pin "3") (pinfunction "1_3") (pintype "passive"))
      (node (ref "U_ADC_DMS6") (pin "18") (pinfunction "DOUT/~{DRDY}_18") (pintype "bidirectional"))
    )
    (net (code "124") (name "Net-(RN_DMS6D-1)") (class "Default")
      (node (ref "RN_DMS6") (pin "4") (pinfunction "1_4") (pintype "passive"))
      (node (ref "U_ADC_DMS6") (pin "17") (pinfunction "~{DRDY}_17") (pintype "bidirectional"))
    )
    (net (code "125") (name "Net-(U$1-4)") (class "Default")
      (node (ref "R32") (pin "2") (pinfunction "2_2") (pintype "passive"))
      (node (ref "U$1") (pin "P$4") (pinfunction "4_P$4") (pintype "passive"))
    )
    (net (code "126") (name "Net-(U$2-4)") (class "Default")
      (node (ref "R4") (pin "2") (pinfunction "2_2") (pintype "passive"))
      (node (ref "U$2") (pin "P$4") (pinfunction "4_P$4") (pintype "passive"))
    )
    (net (code "127") (name "Net-(U$3-4)") (class "Default")
      (node (ref "R39") (pin "2") (pinfunction "2_2") (pintype "passive"))
      (node (ref "U$3") (pin "P$4") (pinfunction "4_P$4") (pintype "passive"))
    )
    (net (code "128") (name "Net-(U$4-4)") (class "Default")
      (node (ref "R46") (pin "2") (pinfunction "2_2") (pintype "passive"))
      (node (ref "U$4") (pin "P$4") (pinfunction "4_P$4") (pintype "passive"))
    )
    (net (code "129") (name "Net-(U$5-4)") (class "Default")
      (node (ref "R53") (pin "2") (pinfunction "2_2") (pintype "passive"))
      (node (ref "U$5") (pin "P$4") (pinfunction "4_P$4") (pintype "passive"))
    )
    (net (code "130") (name "Net-(U$6-4)") (class "Default")
      (node (ref "R60") (pin "2") (pinfunction "2_2") (pintype "passive"))
      (node (ref "U$6") (pin "P$4") (pinfunction "4_P$4") (pintype "passive"))
    )
    (net (code "131") (name "Net-(U_ADC_DMS1-AIN0{slash}IEXC)") (class "Default")
      (node (ref "C6") (pin "2") (pinfunction "2_2") (pintype "passive"))
      (node (ref "C7") (pin "1") (pinfunction "1_1") (pintype "passive"))
      (node (ref "R4") (pin "1") (pinfunction "1_1") (pintype "passive"))
      (node (ref "U_ADC_DMS1") (pin "9") (pinfunction "AIN0/IEXC_9") (pintype "bidirectional"))
    )
    (net (code "132") (name "Net-(U_ADC_DMS1-AIN1{slash}IEXC)") (class "Default")
      (node (ref "C7") (pin "2") (pinfunction "2_2") (pintype "passive"))
      (node (ref "C8") (pin "1") (pinfunction "1_1") (pintype "passive"))
      (node (ref "R5") (pin "1") (pinfunction "1_1") (pintype "passive"))
      (node (ref "U_ADC_DMS1") (pin "10") (pinfunction "AIN1/IEXC_10") (pintype "bidirectional"))
    )
    (net (code "133") (name "Net-(U_ADC_DMS1-SCLK)") (class "Default")
      (node (ref "RN_DMS1") (pin "1") (pinfunction "1_1") (pintype "passive"))
      (node (ref "U_ADC_DMS1") (pin "20") (pinfunction "SCLK_20") (pintype "bidirectional"))
    )
    (net (code "134") (name "Net-(U_ADC_DMS1-START)") (class "Default")
      (node (ref "R2") (pin "1") (pinfunction "1_1") (pintype "passive"))
      (node (ref "U_ADC_DMS1") (pin "15") (pinfunction "START_15") (pintype "bidirectional"))
    )
    (net (code "135") (name "Net-(U_ADC_DMS1-VREFOUT)") (class "Default")
      (node (ref "C4") (pin "1") (pinfunction "1_1") (pintype "passive"))
      (node (ref "U_ADC_DMS1") (pin "7") (pinfunction "VREFOUT_7") (pintype "bidirectional"))
    )
    (net (code "136") (name "Net-(U_ADC_DMS1-~{CS})") (class "Default")
      (node (ref "R3") (pin "1") (pinfunction "1_1") (pintype "passive"))
      (node (ref "U_ADC_DMS1") (pin "16") (pinfunction "~{CS}_16") (pintype "bidirectional"))
    )
    (net (code "137") (name "Net-(U_ADC_DMS1-~{RESET})") (class "Default")
      (node (ref "R1") (pin "2") (pinfunction "2_2") (pintype "passive"))
      (node (ref "U_ADC_DMS1") (pin "4") (pinfunction "~{RESET}_4") (pintype "bidirectional"))
    )
    (net (code "138") (name "Net-(U_ADC_DMS2-AIN0{slash}IEXC)") (class "Default")
      (node (ref "C12") (pin "2") (pinfunction "2_2") (pintype "passive"))
      (node (ref "C13") (pin "1") (pinfunction "1_1") (pintype "passive"))
      (node (ref "R32") (pin "1") (pinfunction "1_1") (pintype "passive"))
      (node (ref "U_ADC_DMS2") (pin "9") (pinfunction "AIN0/IEXC_9") (pintype "bidirectional"))
    )
    (net (code "139") (name "Net-(U_ADC_DMS2-AIN1{slash}IEXC)") (class "Default")
      (node (ref "C13") (pin "2") (pinfunction "2_2") (pintype "passive"))
      (node (ref "C14") (pin "1") (pinfunction "1_1") (pintype "passive"))
      (node (ref "R33") (pin "1") (pinfunction "1_1") (pintype "passive"))
      (node (ref "U_ADC_DMS2") (pin "10") (pinfunction "AIN1/IEXC_10") (pintype "bidirectional"))
    )
    (net (code "140") (name "Net-(U_ADC_DMS2-SCLK)") (class "Default")
      (node (ref "RN_DMS2") (pin "1") (pinfunction "1_1") (pintype "passive"))
      (node (ref "U_ADC_DMS2") (pin "20") (pinfunction "SCLK_20") (pintype "bidirectional"))
    )
    (net (code "141") (name "Net-(U_ADC_DMS2-START)") (class "Default")
      (node (ref "R30") (pin "1") (pinfunction "1_1") (pintype "passive"))
      (node (ref "U_ADC_DMS2") (pin "15") (pinfunction "START_15") (pintype "bidirectional"))
    )
    (net (code "142") (name "Net-(U_ADC_DMS2-VREFOUT)") (class "Default")
      (node (ref "C11") (pin "1") (pinfunction "1_1") (pintype "passive"))
      (node (ref "U_ADC_DMS2") (pin "7") (pinfunction "VREFOUT_7") (pintype "bidirectional"))
    )
    (net (code "143") (name "Net-(U_ADC_DMS2-~{CS})") (class "Default")
      (node (ref "R31") (pin "1") (pinfunction "1_1") (pintype "passive"))
      (node (ref "U_ADC_DMS2") (pin "16") (pinfunction "~{CS}_16") (pintype "bidirectional"))
    )
    (net (code "144") (name "Net-(U_ADC_DMS2-~{RESET})") (class "Default")
      (node (ref "R8") (pin "2") (pinfunction "2_2") (pintype "passive"))
      (node (ref "U_ADC_DMS2") (pin "4") (pinfunction "~{RESET}_4") (pintype "bidirectional"))
    )
    (net (code "145") (name "Net-(U_ADC_DMS3-AIN0{slash}IEXC)") (class "Default")
      (node (ref "C21") (pin "2") (pinfunction "2_2") (pintype "passive"))
      (node (ref "C22") (pin "1") (pinfunction "1_1") (pintype "passive"))
      (node (ref "R39") (pin "1") (pinfunction "1_1") (pintype "passive"))
      (node (ref "U_ADC_DMS3") (pin "9") (pinfunction "AIN0/IEXC_9") (pintype "bidirectional"))
    )
    (net (code "146") (name "Net-(U_ADC_DMS3-AIN1{slash}IEXC)") (class "Default")
      (node (ref "C22") (pin "2") (pinfunction "2_2") (pintype "passive"))
      (node (ref "C23") (pin "1") (pinfunction "1_1") (pintype "passive"))
      (node (ref "R40") (pin "1") (pinfunction "1_1") (pintype "passive"))
      (node (ref "U_ADC_DMS3") (pin "10") (pinfunction "AIN1/IEXC_10") (pintype "bidirectional"))
    )
    (net (code "147") (name "Net-(U_ADC_DMS3-SCLK)") (class "Default")
      (node (ref "RN_DMS3") (pin "1") (pinfunction "1_1") (pintype "passive"))
      (node (ref "U_ADC_DMS3") (pin "20") (pinfunction "SCLK_20") (pintype "bidirectional"))
    )
    (net (code "148") (name "Net-(U_ADC_DMS3-START)") (class "Default")
      (node (ref "R37") (pin "1") (pinfunction "1_1") (pintype "passive"))
      (node (ref "U_ADC_DMS3") (pin "15") (pinfunction "START_15") (pintype "bidirectional"))
    )
    (net (code "149") (name "Net-(U_ADC_DMS3-VREFOUT)") (class "Default")
      (node (ref "C20") (pin "1") (pinfunction "1_1") (pintype "passive"))
      (node (ref "U_ADC_DMS3") (pin "7") (pinfunction "VREFOUT_7") (pintype "bidirectional"))
    )
    (net (code "150") (name "Net-(U_ADC_DMS3-~{CS})") (class "Default")
      (node (ref "R38") (pin "1") (pinfunction "1_1") (pintype "passive"))
      (node (ref "U_ADC_DMS3") (pin "16") (pinfunction "~{CS}_16") (pintype "bidirectional"))
    )
    (net (code "151") (name "Net-(U_ADC_DMS3-~{RESET})") (class "Default")
      (node (ref "R36") (pin "2") (pinfunction "2_2") (pintype "passive"))
      (node (ref "U_ADC_DMS3") (pin "4") (pinfunction "~{RESET}_4") (pintype "bidirectional"))
    )
    (net (code "152") (name "Net-(U_ADC_DMS4-AIN0{slash}IEXC)") (class "Default")
      (node (ref "C27") (pin "2") (pinfunction "2_2") (pintype "passive"))
      (node (ref "C45") (pin "1") (pinfunction "1_1") (pintype "passive"))
      (node (ref "R46") (pin "1") (pinfunction "1_1") (pintype "passive"))
      (node (ref "U_ADC_DMS4") (pin "9") (pinfunction "AIN0/IEXC_9") (pintype "bidirectional"))
    )
    (net (code "153") (name "Net-(U_ADC_DMS4-AIN1{slash}IEXC)") (class "Default")
      (node (ref "C45") (pin "2") (pinfunction "2_2") (pintype "passive"))
      (node (ref "C46") (pin "1") (pinfunction "1_1") (pintype "passive"))
      (node (ref "R47") (pin "1") (pinfunction "1_1") (pintype "passive"))
      (node (ref "U_ADC_DMS4") (pin "10") (pinfunction "AIN1/IEXC_10") (pintype "bidirectional"))
    )
    (net (code "154") (name "Net-(U_ADC_DMS4-SCLK)") (class "Default")
      (node (ref "RN_DMS4") (pin "1") (pinfunction "1_1") (pintype "passive"))
      (node (ref "U_ADC_DMS4") (pin "20") (pinfunction "SCLK_20") (pintype "bidirectional"))
    )
    (net (code "155") (name "Net-(U_ADC_DMS4-START)") (class "Default")
      (node (ref "R44") (pin "1") (pinfunction "1_1") (pintype "passive"))
      (node (ref "U_ADC_DMS4") (pin "15") (pinfunction "START_15") (pintype "bidirectional"))
    )
    (net (code "156") (name "Net-(U_ADC_DMS4-VREFOUT)") (class "Default")
      (node (ref "C26") (pin "1") (pinfunction "1_1") (pintype "passive"))
      (node (ref "U_ADC_DMS4") (pin "7") (pinfunction "VREFOUT_7") (pintype "bidirectional"))
    )
    (net (code "157") (name "Net-(U_ADC_DMS4-~{CS})") (class "Default")
      (node (ref "R45") (pin "1") (pinfunction "1_1") (pintype "passive"))
      (node (ref "U_ADC_DMS4") (pin "16") (pinfunction "~{CS}_16") (pintype "bidirectional"))
    )
    (net (code "158") (name "Net-(U_ADC_DMS4-~{RESET})") (class "Default")
      (node (ref "R43") (pin "2") (pinfunction "2_2") (pintype "passive"))
      (node (ref "U_ADC_DMS4") (pin "4") (pinfunction "~{RESET}_4") (pintype "bidirectional"))
    )
    (net (code "159") (name "Net-(U_ADC_DMS5-AIN0{slash}IEXC)") (class "Default")
      (node (ref "C50") (pin "2") (pinfunction "2_2") (pintype "passive"))
      (node (ref "C51") (pin "1") (pinfunction "1_1") (pintype "passive"))
      (node (ref "R53") (pin "1") (pinfunction "1_1") (pintype "passive"))
      (node (ref "U_ADC_DMS5") (pin "9") (pinfunction "AIN0/IEXC_9") (pintype "bidirectional"))
    )
    (net (code "160") (name "Net-(U_ADC_DMS5-AIN1{slash}IEXC)") (class "Default")
      (node (ref "C51") (pin "2") (pinfunction "2_2") (pintype "passive"))
      (node (ref "C53") (pin "1") (pinfunction "1_1") (pintype "passive"))
      (node (ref "R54") (pin "1") (pinfunction "1_1") (pintype "passive"))
      (node (ref "U_ADC_DMS5") (pin "10") (pinfunction "AIN1/IEXC_10") (pintype "bidirectional"))
    )
    (net (code "161") (name "Net-(U_ADC_DMS5-SCLK)") (class "Default")
      (node (ref "RN_DMS5") (pin "1") (pinfunction "1_1") (pintype "passive"))
      (node (ref "U_ADC_DMS5") (pin "20") (pinfunction "SCLK_20") (pintype "bidirectional"))
    )
    (net (code "162") (name "Net-(U_ADC_DMS5-START)") (class "Default")
      (node (ref "R51") (pin "1") (pinfunction "1_1") (pintype "passive"))
      (node (ref "U_ADC_DMS5") (pin "15") (pinfunction "START_15") (pintype "bidirectional"))
    )
    (net (code "163") (name "Net-(U_ADC_DMS5-VREFOUT)") (class "Default")
      (node (ref "C49") (pin "1") (pinfunction "1_1") (pintype "passive"))
      (node (ref "U_ADC_DMS5") (pin "7") (pinfunction "VREFOUT_7") (pintype "bidirectional"))
    )
    (net (code "164") (name "Net-(U_ADC_DMS5-~{CS})") (class "Default")
      (node (ref "R52") (pin "1") (pinfunction "1_1") (pintype "passive"))
      (node (ref "U_ADC_DMS5") (pin "16") (pinfunction "~{CS}_16") (pintype "bidirectional"))
    )
    (net (code "165") (name "Net-(U_ADC_DMS5-~{RESET})") (class "Default")
      (node (ref "R50") (pin "2") (pinfunction "2_2") (pintype "passive"))
      (node (ref "U_ADC_DMS5") (pin "4") (pinfunction "~{RESET}_4") (pintype "bidirectional"))
    )
    (net (code "166") (name "Net-(U_ADC_DMS6-AIN0{slash}IEXC)") (class "Default")
      (node (ref "C57") (pin "2") (pinfunction "2_2") (pintype "passive"))
      (node (ref "C58") (pin "1") (pinfunction "1_1") (pintype "passive"))
      (node (ref "R60") (pin "1") (pinfunction "1_1") (pintype "passive"))
      (node (ref "U_ADC_DMS6") (pin "9") (pinfunction "AIN0/IEXC_9") (pintype "bidirectional"))
    )
    (net (code "167") (name "Net-(U_ADC_DMS6-AIN1{slash}IEXC)") (class "Default")
      (node (ref "C58") (pin "2") (pinfunction "2_2") (pintype "passive"))
      (node (ref "C59") (pin "1") (pinfunction "1_1") (pintype "passive"))
      (node (ref "R61") (pin "1") (pinfunction "1_1") (pintype "passive"))
      (node (ref "U_ADC_DMS6") (pin "10") (pinfunction "AIN1/IEXC_10") (pintype "bidirectional"))
    )
    (net (code "168") (name "Net-(U_ADC_DMS6-SCLK)") (class "Default")
      (node (ref "RN_DMS6") (pin "1") (pinfunction "1_1") (pintype "passive"))
      (node (ref "U_ADC_DMS6") (pin "20") (pinfunction "SCLK_20") (pintype "bidirectional"))
    )
    (net (code "169") (name "Net-(U_ADC_DMS6-START)") (class "Default")
      (node (ref "R58") (pin "1") (pinfunction "1_1") (pintype "passive"))
      (node (ref "U_ADC_DMS6") (pin "15") (pinfunction "START_15") (pintype "bidirectional"))
    )
    (net (code "170") (name "Net-(U_ADC_DMS6-VREFOUT)") (class "Default")
      (node (ref "C56") (pin "1") (pinfunction "1_1") (pintype "passive"))
      (node (ref "U_ADC_DMS6") (pin "7") (pinfunction "VREFOUT_7") (pintype "bidirectional"))
    )
    (net (code "171") (name "Net-(U_ADC_DMS6-~{CS})") (class "Default")
      (node (ref "R59") (pin "1") (pinfunction "1_1") (pintype "passive"))
      (node (ref "U_ADC_DMS6") (pin "16") (pinfunction "~{CS}_16") (pintype "bidirectional"))
    )
    (net (code "172") (name "Net-(U_ADC_DMS6-~{RESET})") (class "Default")
      (node (ref "R57") (pin "2") (pinfunction "2_2") (pintype "passive"))
      (node (ref "U_ADC_DMS6") (pin "4") (pinfunction "~{RESET}_4") (pintype "bidirectional"))
    )
    (net (code "173") (name "Net-(U_ADC_PT1-AIN1{slash}IEXC)") (class "Default")
      (node (ref "C_ICM1_PT1") (pin "2") (pinfunction "2_2") (pintype "passive"))
      (node (ref "C_IDIFF_PT1") (pin "1") (pinfunction "1_1") (pintype "passive"))
      (node (ref "R_I1_PT1") (pin "1") (pinfunction "1_1") (pintype "passive"))
      (node (ref "U_ADC_PT1") (pin "10") (pinfunction "AIN1/IEXC_10") (pintype "bidirectional"))
    )
    (net (code "174") (name "Net-(U_ADC_PT1-AIN2{slash}IEXC{slash}GPIO2)") (class "Default")
      (node (ref "C_ICM2_PT1") (pin "1") (pinfunction "1_1") (pintype "passive"))
      (node (ref "C_IDIFF_PT1") (pin "2") (pinfunction "2_2") (pintype "passive"))
      (node (ref "R_I2_PT1") (pin "1") (pinfunction "1_1") (pintype "passive"))
      (node (ref "U_ADC_PT1") (pin "11") (pinfunction "AIN2/IEXC/GPIO2_11") (pintype "bidirectional"))
    )
    (net (code "175") (name "Net-(U_ADC_PT1-REFN0{slash}GPIO1)") (class "Default")
      (node (ref "C_RCM2_PT1") (pin "1") (pinfunction "1_1") (pintype "passive"))
      (node (ref "C_RDIFF_PT1") (pin "2") (pinfunction "2_2") (pintype "passive"))
      (node (ref "R_R2_PT1") (pin "1") (pinfunction "1_1") (pintype "passive"))
      (node (ref "U_ADC_PT1") (pin "6") (pinfunction "REFN0/GPIO1_6") (pintype "bidirectional"))
    )
    (net (code "176") (name "Net-(U_ADC_PT1-REFP0{slash}GPIO0)") (class "Default")
      (node (ref "C_RCM1_PT1") (pin "2") (pinfunction "2_2") (pintype "passive"))
      (node (ref "C_RDIFF_PT1") (pin "1") (pinfunction "1_1") (pintype "passive"))
      (node (ref "R_R1_PT1") (pin "1") (pinfunction "1_1") (pintype "passive"))
      (node (ref "U_ADC_PT1") (pin "5") (pinfunction "REFP0/GPIO0_5") (pintype "bidirectional"))
    )
    (net (code "177") (name "Net-(U_ADC_PT1-VREFOUT)") (class "Default")
      (node (ref "C_VREF_PT1") (pin "1") (pinfunction "1_1") (pintype "passive"))
      (node (ref "U_ADC_PT1") (pin "7") (pinfunction "VREFOUT_7") (pintype "bidirectional"))
    )
    (net (code "178") (name "Net-(U_ADC_PT1-~{DRDY})") (class "Default")
      (node (ref "RN_B_PT1") (pin "1") (pinfunction "1_1") (pintype "passive"))
      (node (ref "U_ADC_PT1") (pin "17") (pinfunction "~{DRDY}_17") (pintype "bidirectional"))
    )
    (net (code "179") (name "Net-(U_ADC_PT1-~{RESET})") (class "Default")
      (node (ref "RN_A_PT1") (pin "1") (pinfunction "1_1") (pintype "passive"))
      (node (ref "U_ADC_PT1") (pin "4") (pinfunction "~{RESET}_4") (pintype "bidirectional"))
    )
    (net (code "180") (name "Net-(U_ADC_PT2-AIN1{slash}IEXC)") (class "Default")
      (node (ref "C_ICM1_PT2") (pin "2") (pinfunction "2_2") (pintype "passive"))
      (node (ref "C_IDIFF_PT2") (pin "1") (pinfunction "1_1") (pintype "passive"))
      (node (ref "R_I1_PT2") (pin "1") (pinfunction "1_1") (pintype "passive"))
      (node (ref "U_ADC_PT2") (pin "10") (pinfunction "AIN1/IEXC_10") (pintype "bidirectional"))
    )
    (net (code "181") (name "Net-(U_ADC_PT2-AIN2{slash}IEXC{slash}GPIO2)") (class "Default")
      (node (ref "C_ICM2_PT2") (pin "1") (pinfunction "1_1") (pintype "passive"))
      (node (ref "C_IDIFF_PT2") (pin "2") (pinfunction "2_2") (pintype "passive"))
      (node (ref "R_I2_PT2") (pin "1") (pinfunction "1_1") (pintype "passive"))
      (node (ref "U_ADC_PT2") (pin "11") (pinfunction "AIN2/IEXC/GPIO2_11") (pintype "bidirectional"))
    )
    (net (code "182") (name "Net-(U_ADC_PT2-REFN0{slash}GPIO1)") (class "Default")
      (node (ref "C_RCM2_PT2") (pin "1") (pinfunction "1_1") (pintype "passive"))
      (node (ref "C_RDIFF_PT2") (pin "2") (pinfunction "2_2") (pintype "passive"))
      (node (ref "R_R2_PT2") (pin "1") (pinfunction "1_1") (pintype "passive"))
      (node (ref "U_ADC_PT2") (pin "6") (pinfunction "REFN0/GPIO1_6") (pintype "bidirectional"))
    )
    (net (code "183") (name "Net-(U_ADC_PT2-REFP0{slash}GPIO0)") (class "Default")
      (node (ref "C_RCM1_PT2") (pin "2") (pinfunction "2_2") (pintype "passive"))
      (node (ref "C_RDIFF_PT2") (pin "1") (pinfunction "1_1") (pintype "passive"))
      (node (ref "R_R1_PT2") (pin "1") (pinfunction "1_1") (pintype "passive"))
      (node (ref "U_ADC_PT2") (pin "5") (pinfunction "REFP0/GPIO0_5") (pintype "bidirectional"))
    )
    (net (code "184") (name "Net-(U_ADC_PT2-VREFOUT)") (class "Default")
      (node (ref "C_VREF_PT2") (pin "1") (pinfunction "1_1") (pintype "passive"))
      (node (ref "U_ADC_PT2") (pin "7") (pinfunction "VREFOUT_7") (pintype "bidirectional"))
    )
    (net (code "185") (name "Net-(U_ADC_PT2-~{DRDY})") (class "Default")
      (node (ref "RN_B_PT2") (pin "1") (pinfunction "1_1") (pintype "passive"))
      (node (ref "U_ADC_PT2") (pin "17") (pinfunction "~{DRDY}_17") (pintype "bidirectional"))
    )
    (net (code "186") (name "Net-(U_ADC_PT2-~{RESET})") (class "Default")
      (node (ref "RN_A_PT2") (pin "1") (pinfunction "1_1") (pintype "passive"))
      (node (ref "U_ADC_PT2") (pin "4") (pinfunction "~{RESET}_4") (pintype "bidirectional"))
    )
    (net (code "187") (name "Net-(U_ADC_PT3-AIN1{slash}IEXC)") (class "Default")
      (node (ref "C_ICM1_PT3") (pin "2") (pinfunction "2_2") (pintype "passive"))
      (node (ref "C_IDIFF_PT3") (pin "1") (pinfunction "1_1") (pintype "passive"))
      (node (ref "R_I1_PT3") (pin "1") (pinfunction "1_1") (pintype "passive"))
      (node (ref "U_ADC_PT3") (pin "10") (pinfunction "AIN1/IEXC_10") (pintype "bidirectional"))
    )
    (net (code "188") (name "Net-(U_ADC_PT3-AIN2{slash}IEXC{slash}GPIO2)") (class "Default")
      (node (ref "C_ICM2_PT3") (pin "1") (pinfunction "1_1") (pintype "passive"))
      (node (ref "C_IDIFF_PT3") (pin "2") (pinfunction "2_2") (pintype "passive"))
      (node (ref "R_I2_PT3") (pin "1") (pinfunction "1_1") (pintype "passive"))
      (node (ref "U_ADC_PT3") (pin "11") (pinfunction "AIN2/IEXC/GPIO2_11") (pintype "bidirectional"))
    )
    (net (code "189") (name "Net-(U_ADC_PT3-REFN0{slash}GPIO1)") (class "Default")
      (node (ref "C_RCM2_PT3") (pin "1") (pinfunction "1_1") (pintype "passive"))
      (node (ref "C_RDIFF_PT3") (pin "2") (pinfunction "2_2") (pintype "passive"))
      (node (ref "R_R2_PT3") (pin "1") (pinfunction "1_1") (pintype "passive"))
      (node (ref "U_ADC_PT3") (pin "6") (pinfunction "REFN0/GPIO1_6") (pintype "bidirectional"))
    )
    (net (code "190") (name "Net-(U_ADC_PT3-REFP0{slash}GPIO0)") (class "Default")
      (node (ref "C_RCM1_PT3") (pin "2") (pinfunction "2_2") (pintype "passive"))
      (node (ref "C_RDIFF_PT3") (pin "1") (pinfunction "1_1") (pintype "passive"))
      (node (ref "R_R1_PT3") (pin "1") (pinfunction "1_1") (pintype "passive"))
      (node (ref "U_ADC_PT3") (pin "5") (pinfunction "REFP0/GPIO0_5") (pintype "bidirectional"))
    )
    (net (code "191") (name "Net-(U_ADC_PT3-VREFOUT)") (class "Default")
      (node (ref "C_VREF_PT3") (pin "1") (pinfunction "1_1") (pintype "passive"))
      (node (ref "U_ADC_PT3") (pin "7") (pinfunction "VREFOUT_7") (pintype "bidirectional"))
    )
    (net (code "192") (name "Net-(U_ADC_PT3-~{DRDY})") (class "Default")
      (node (ref "RN_B_PT3") (pin "1") (pinfunction "1_1") (pintype "passive"))
      (node (ref "U_ADC_PT3") (pin "17") (pinfunction "~{DRDY}_17") (pintype "bidirectional"))
    )
    (net (code "193") (name "Net-(U_ADC_PT3-~{RESET})") (class "Default")
      (node (ref "RN_A_PT3") (pin "1") (pinfunction "1_1") (pintype "passive"))
      (node (ref "U_ADC_PT3") (pin "4") (pinfunction "~{RESET}_4") (pintype "bidirectional"))
    )
    (net (code "194") (name "Net-(U_ADR366_3-TRIM)") (class "Default")
      (node (ref "R22") (pin "1") (pinfunction "1_1") (pintype "passive"))
      (node (ref "U_ADR366_3") (pin "5") (pinfunction "TRIM_5") (pintype "passive"))
    )
    (net (code "195") (name "Net-(U_CH340G-XI)") (class "Default")
      (node (ref "C1") (pin "1") (pinfunction "1_1") (pintype "passive"))
      (node (ref "Q1") (pin "1") (pinfunction "1_1") (pintype "passive"))
      (node (ref "U_CH340G") (pin "7") (pinfunction "XI_7") (pintype "bidirectional"))
    )
    (net (code "196") (name "Net-(U_CH340G-XO)") (class "Default")
      (node (ref "C2") (pin "1") (pinfunction "1_1") (pintype "passive"))
      (node (ref "Q1") (pin "2") (pinfunction "2_2") (pintype "passive"))
      (node (ref "U_CH340G") (pin "8") (pinfunction "XO_8") (pintype "bidirectional"))
    )
    (net (code "197") (name "Net-(U_OPTO_3-C1)") (class "Default")
      (node (ref "R11") (pin "2") (pinfunction "2_2") (pintype "passive"))
      (node (ref "U_OPTO_3") (pin "2") (pinfunction "C1_2") (pintype "bidirectional"))
    )
    (net (code "198") (name "Net-(U_OPTO_3-C2)") (class "Default")
      (node (ref "R12") (pin "2") (pinfunction "2_2") (pintype "passive"))
      (node (ref "U_OPTO_3") (pin "4") (pinfunction "C2_4") (pintype "bidirectional"))
    )
    (net (code "199") (name "Net-(U_STM32F779-BOOT0)") (class "Default")
      (node (ref "R27") (pin "1") (pinfunction "1_1") (pintype "passive"))
      (node (ref "R28") (pin "2") (pinfunction "2_2") (pintype "passive"))
      (node (ref "U_STM32F779") (pin "197") (pinfunction "BOOT0_197") (pintype "bidirectional"))
    )
    (net (code "200") (name "Net-(U_STM32F779-VCAPDSI)") (class "Default")
      (node (ref "U_STM32F779") (pin "119") (pinfunction "VCAPDSI_119") (pintype "bidirectional"))
      (node (ref "U_STM32F779") (pin "125") (pinfunction "VDD12DSI_125") (pintype "bidirectional"))
    )
    (net (code "201") (name "Net-(U_STM32F779-VCAP_1)") (class "Default")
      (node (ref "C17") (pin "2") (pinfunction "2_2") (pintype "passive"))
      (node (ref "U_STM32F779") (pin "92") (pinfunction "VCAP_1_92") (pintype "bidirectional"))
    )
    (net (code "202") (name "Net-(U_STM32F779-VCAP_2)") (class "Default")
      (node (ref "C16") (pin "2") (pinfunction "2_2") (pintype "passive"))
      (node (ref "U_STM32F779") (pin "148") (pinfunction "VCAP_2_148") (pintype "bidirectional"))
    )
    (net (code "203") (name "PDR_ON") (class "Default")
      (node (ref "R9") (pin "1") (pinfunction "1_1") (pintype "passive"))
      (node (ref "U_STM32F779") (pin "203") (pinfunction "PDR_ON_203") (pintype "bidirectional"))
    )
    (net (code "204") (name "PT11") (class "Default")
      (node (ref "R_I1_PT1") (pin "2") (pinfunction "2_2") (pintype "passive"))
      (node (ref "U_ADC_PT1") (pin "9") (pinfunction "AIN0/IEXC_9") (pintype "bidirectional"))
      (node (ref "X_PT") (pin "P$B3") (pinfunction "B3_P$B3") (pintype "passive"))
    )
    (net (code "205") (name "PT12") (class "Default")
      (node (ref "R_I2_PT1") (pin "2") (pinfunction "2_2") (pintype "passive"))
      (node (ref "U_ADC_PT1") (pin "12") (pinfunction "AIN3/IEXC/GPIO3_12") (pintype "bidirectional"))
      (node (ref "X_PT") (pin "P$B2") (pinfunction "B2_P$B2") (pintype "passive"))
    )
    (net (code "206") (name "PT13") (class "Default")
      (node (ref "R_R1_PT1") (pin "2") (pinfunction "2_2") (pintype "passive"))
      (node (ref "R_REF_PT1") (pin "2") (pinfunction "2_2") (pintype "passive"))
      (node (ref "X_PT") (pin "P$B1") (pinfunction "B1_P$B1") (pintype "passive"))
    )
    (net (code "207") (name "PT21") (class "Default")
      (node (ref "R_I1_PT2") (pin "2") (pinfunction "2_2") (pintype "passive"))
      (node (ref "U_ADC_PT2") (pin "9") (pinfunction "AIN0/IEXC_9") (pintype "bidirectional"))
      (node (ref "X_PT") (pin "P$B5") (pinfunction "B5_P$B5") (pintype "passive"))
    )
    (net (code "208") (name "PT22") (class "Default")
      (node (ref "R_I2_PT2") (pin "2") (pinfunction "2_2") (pintype "passive"))
      (node (ref "U_ADC_PT2") (pin "12") (pinfunction "AIN3/IEXC/GPIO3_12") (pintype "bidirectional"))
      (node (ref "X_PT") (pin "P$B4") (pinfunction "B4_P$B4") (pintype "passive"))
    )
    (net (code "209") (name "PT23") (class "Default")
      (node (ref "R_R1_PT2") (pin "2") (pinfunction "2_2") (pintype "passive"))
      (node (ref "R_REF_PT2") (pin "2") (pinfunction "2_2") (pintype "passive"))
      (node (ref "X_PT") (pin "P$B6") (pinfunction "B6_P$B6") (pintype "passive"))
    )
    (net (code "210") (name "PT31") (class "Default")
      (node (ref "R_I1_PT3") (pin "2") (pinfunction "2_2") (pintype "passive"))
      (node (ref "U_ADC_PT3") (pin "9") (pinfunction "AIN0/IEXC_9") (pintype "bidirectional"))
      (node (ref "X_PT") (pin "P$A1") (pinfunction "A1_P$A1") (pintype "passive"))
    )
    (net (code "211") (name "PT32") (class "Default")
      (node (ref "R_I2_PT3") (pin "2") (pinfunction "2_2") (pintype "passive"))
      (node (ref "U_ADC_PT3") (pin "12") (pinfunction "AIN3/IEXC/GPIO3_12") (pintype "bidirectional"))
      (node (ref "X_PT") (pin "P$A2") (pinfunction "A2_P$A2") (pintype "passive"))
    )
    (net (code "212") (name "PT33") (class "Default")
      (node (ref "R_R1_PT3") (pin "2") (pinfunction "2_2") (pintype "passive"))
      (node (ref "R_REF_PT3") (pin "2") (pinfunction "2_2") (pintype "passive"))
      (node (ref "X_PT") (pin "P$A3") (pinfunction "A3_P$A3") (pintype "passive"))
    )
    (net (code "213") (name "SD_CS") (class "Default")
      (node (ref "U$7") (pin "2") (pinfunction "CS_2") (pintype "input"))
      (node (ref "U_STM32F779") (pin "31") (pinfunction "PF10_31") (pintype "bidirectional"))
    )
    (net (code "214") (name "SODS") (class "Default")
      (node (ref "U_OPTO_1") (pin "2") (pinfunction "C1_2") (pintype "bidirectional"))
      (node (ref "X_MIRROR") (pin "P$A7") (pinfunction "A7_P$A7") (pintype "passive"))
      (node (ref "X_MIRROR1") (pin "P$A7") (pinfunction "A7_P$A7") (pintype "passive"))
      (node (ref "X_RXSM-DAPI") (pin "P$B6") (pinfunction "B6_P$B6") (pintype "passive"))
    )
    (net (code "215") (name "SODS_OPT") (class "Default")
      (node (ref "D8") (pin "C") (pinfunction "C_C") (pintype "passive"))
      (node (ref "RN12") (pin "8") (pinfunction "2_8") (pintype "passive"))
      (node (ref "U_OPTO_1") (pin "8") (pinfunction "COL1_8") (pintype "input"))
      (node (ref "U_STM32F779") (pin "206") (pinfunction "PI5_206") (pintype "bidirectional"))
    )
    (net (code "216") (name "SOE") (class "Default")
      (node (ref "U_OPTO_1") (pin "4") (pinfunction "C2_4") (pintype "bidirectional"))
      (node (ref "X_MIRROR") (pin "P$A6") (pinfunction "A6_P$A6") (pintype "passive"))
      (node (ref "X_MIRROR1") (pin "P$A8") (pinfunction "A8_P$A8") (pintype "passive"))
      (node (ref "X_RXSM-DAPI") (pin "P$B5") (pinfunction "B5_P$B5") (pintype "passive"))
    )
    (net (code "217") (name "SOE_OPT") (class "Default")
      (node (ref "D9") (pin "C") (pinfunction "C_C") (pintype "passive"))
      (node (ref "RN12") (pin "7") (pinfunction "2_7") (pintype "passive"))
      (node (ref "U_OPTO_1") (pin "6") (pinfunction "COL2_6") (pintype "input"))
      (node (ref "U_STM32F779") (pin "207") (pinfunction "PI6_207") (pintype "bidirectional"))
    )
    (net (code "218") (name "SPI2_MISO") (class "Default")
      (node (ref "U_FLASH2") (pin "8") (pinfunction "SO_8") (pintype "bidirectional"))
      (node (ref "U_STM32F779") (pin "106") (pinfunction "PB14_106") (pintype "bidirectional"))
    )
    (net (code "219") (name "SPI2_MOSI") (class "Default")
      (node (ref "U_FLASH2") (pin "15") (pinfunction "SI_15") (pintype "bidirectional"))
      (node (ref "U_STM32F779") (pin "107") (pinfunction "PB15_107") (pintype "bidirectional"))
    )
    (net (code "220") (name "SPI2_SCK") (class "Default")
      (node (ref "U_FLASH2") (pin "16") (pinfunction "SCK_16") (pintype "bidirectional"))
      (node (ref "U_STM32F779") (pin "105") (pinfunction "PB13_105") (pintype "bidirectional"))
    )
    (net (code "221") (name "SPI3_MISO") (class "Default")
      (node (ref "RN_A_PT1") (pin "5") (pinfunction "2_5") (pintype "passive"))
      (node (ref "RN_A_PT2") (pin "5") (pinfunction "2_5") (pintype "passive"))
      (node (ref "RN_A_PT3") (pin "5") (pinfunction "2_5") (pintype "passive"))
      (node (ref "U_STM32F779") (pin "162") (pinfunction "PC11_162") (pintype "bidirectional"))
    )
    (net (code "222") (name "SPI3_MOSI") (class "Default")
      (node (ref "RN_A_PT1") (pin "6") (pinfunction "2_6") (pintype "passive"))
      (node (ref "RN_A_PT2") (pin "6") (pinfunction "2_6") (pintype "passive"))
      (node (ref "RN_A_PT3") (pin "6") (pinfunction "2_6") (pintype "passive"))
      (node (ref "U_STM32F779") (pin "63") (pinfunction "PB2_63") (pintype "bidirectional"))
    )
    (net (code "223") (name "SPI3_SCK") (class "Default")
      (node (ref "RN_A_PT1") (pin "7") (pinfunction "2_7") (pintype "passive"))
      (node (ref "RN_A_PT2") (pin "7") (pinfunction "2_7") (pintype "passive"))
      (node (ref "RN_A_PT3") (pin "7") (pinfunction "2_7") (pintype "passive"))
      (node (ref "U_STM32F779") (pin "161") (pinfunction "PC10_161") (pintype "bidirectional"))
    )
    (net (code "224") (name "SPI4_MISO") (class "Default")
      (node (ref "RN_DMS1") (pin "6") (pinfunction "2_6") (pintype "passive"))
      (node (ref "RN_DMS2") (pin "6") (pinfunction "2_6") (pintype "passive"))
      (node (ref "RN_DMS3") (pin "6") (pinfunction "2_6") (pintype "passive"))
      (node (ref "RN_DMS4") (pin "6") (pinfunction "2_6") (pintype "passive"))
      (node (ref "RN_DMS5") (pin "6") (pinfunction "2_6") (pintype "passive"))
      (node (ref "RN_DMS6") (pin "6") (pinfunction "2_6") (pintype "passive"))
      (node (ref "U_STM32F779") (pin "4") (pinfunction "PE5_4") (pintype "bidirectional"))
    )
    (net (code "225") (name "SPI4_MOSI") (class "Default")
      (node (ref "RN_DMS1") (pin "7") (pinfunction "2_7") (pintype "passive"))
      (node (ref "RN_DMS2") (pin "7") (pinfunction "2_7") (pintype "passive"))
      (node (ref "RN_DMS3") (pin "7") (pinfunction "2_7") (pintype "passive"))
      (node (ref "RN_DMS4") (pin "7") (pinfunction "2_7") (pintype "passive"))
      (node (ref "RN_DMS5") (pin "7") (pinfunction "2_7") (pintype "passive"))
      (node (ref "RN_DMS6") (pin "7") (pinfunction "2_7") (pintype "passive"))
      (node (ref "U_STM32F779") (pin "5") (pinfunction "PE6_5") (pintype "bidirectional"))
    )
    (net (code "226") (name "SPI4_SCK") (class "Default")
      (node (ref "RN_DMS1") (pin "8") (pinfunction "2_8") (pintype "passive"))
      (node (ref "RN_DMS2") (pin "8") (pinfunction "2_8") (pintype "passive"))
      (node (ref "RN_DMS3") (pin "8") (pinfunction "2_8") (pintype "passive"))
      (node (ref "RN_DMS4") (pin "8") (pinfunction "2_8") (pintype "passive"))
      (node (ref "RN_DMS5") (pin "8") (pinfunction "2_8") (pintype "passive"))
      (node (ref "RN_DMS6") (pin "8") (pinfunction "2_8") (pintype "passive"))
      (node (ref "U_STM32F779") (pin "1") (pinfunction "PE2_1") (pintype "bidirectional"))
    )
    (net (code "227") (name "SPI5_MISO") (class "Default")
      (node (ref "U$7") (pin "7") (pinfunction "DATA_OUT_7") (pintype "output"))
      (node (ref "U_STM32F779") (pin "29") (pinfunction "PF8_29") (pintype "bidirectional"))
    )
    (net (code "228") (name "SPI5_MOSI") (class "Default")
      (node (ref "U$7") (pin "3") (pinfunction "DATA_IN_3") (pintype "input"))
      (node (ref "U_STM32F779") (pin "30") (pinfunction "PF9_30") (pintype "bidirectional"))
    )
    (net (code "229") (name "SPI5_SCK") (class "Default")
      (node (ref "U$7") (pin "5") (pinfunction "SCLK_5") (pintype "input"))
      (node (ref "U_STM32F779") (pin "28") (pinfunction "PF7_28") (pintype "bidirectional"))
    )
    (net (code "230") (name "SPI6_MISO") (class "Default")
      (node (ref "U_FLASH1") (pin "8") (pinfunction "SO_8") (pintype "bidirectional"))
      (node (ref "U_STM32F779") (pin "55") (pinfunction "PA6_55") (pintype "bidirectional"))
    )
    (net (code "231") (name "SPI6_MOSI") (class "Default")
      (node (ref "U_FLASH1") (pin "15") (pinfunction "SI_15") (pintype "bidirectional"))
      (node (ref "U_STM32F779") (pin "56") (pinfunction "PA7_56") (pintype "bidirectional"))
    )
    (net (code "232") (name "SPI6_SCK") (class "Default")
      (node (ref "U_FLASH1") (pin "16") (pinfunction "SCK_16") (pintype "bidirectional"))
      (node (ref "U_STM32F779") (pin "54") (pinfunction "PA5_54") (pintype "bidirectional"))
    )
    (net (code "233") (name "TCK") (class "Default")
      (node (ref "U_STM32F779") (pin "159") (pinfunction "PA14_159") (pintype "bidirectional"))
      (node (ref "X_PROG") (pin "9") (pinfunction "9_9") (pintype "passive"))
    )
    (net (code "234") (name "TDI") (class "Default")
      (node (ref "U_STM32F779") (pin "160") (pinfunction "PA15_160") (pintype "bidirectional"))
      (node (ref "X_PROG") (pin "5") (pinfunction "5_5") (pintype "passive"))
    )
    (net (code "235") (name "TDO") (class "Default")
      (node (ref "U_STM32F779") (pin "192") (pinfunction "PB3_192") (pintype "bidirectional"))
      (node (ref "X_PROG") (pin "13") (pinfunction "13_13") (pintype "passive"))
    )
    (net (code "236") (name "TMS") (class "Default")
      (node (ref "U_STM32F779") (pin "147") (pinfunction "PA13_147") (pintype "bidirectional"))
      (node (ref "X_PROG") (pin "7") (pinfunction "7_7") (pintype "passive"))
    )
    (net (code "237") (name "TRST") (class "Default")
      (node (ref "JP1") (pin "2") (pinfunction "2_2") (pintype "passive"))
      (node (ref "U_STM32F779") (pin "193") (pinfunction "PB4_193") (pintype "bidirectional"))
      (node (ref "X_PROG") (pin "3") (pinfunction "3_3") (pintype "passive"))
    )
    (net (code "238") (name "unconnected-(U$7-CARD_DETECT-PadCD1)") (class "Default")
      (node (ref "U$7") (pin "CD1") (pinfunction "CARD_DETECT_CD1") (pintype "passive"))
    )
    (net (code "239") (name "unconnected-(U$7-CARD_DETECT1-PadCD2)") (class "Default")
      (node (ref "U$7") (pin "CD2") (pinfunction "CARD_DETECT1_CD2") (pintype "passive"))
    )
    (net (code "240") (name "unconnected-(U$7-DAT1-Pad8)") (class "Default")
      (node (ref "U$7") (pin "8") (pinfunction "DAT1_8") (pintype "bidirectional"))
    )
    (net (code "241") (name "unconnected-(U$7-DAT2-Pad1)") (class "Default")
      (node (ref "U$7") (pin "1") (pinfunction "DAT2_1") (pintype "bidirectional"))
    )
    (net (code "242") (name "unconnected-(U_ADC_DMS1-AIN2{slash}IEXC{slash}GPIO2-Pad11)") (class "Default")
      (node (ref "U_ADC_DMS1") (pin "11") (pinfunction "AIN2/IEXC/GPIO2_11") (pintype "bidirectional"))
    )
    (net (code "243") (name "unconnected-(U_ADC_DMS1-AIN3{slash}IEXC{slash}GPIO3-Pad12)") (class "Default")
      (node (ref "U_ADC_DMS1") (pin "12") (pinfunction "AIN3/IEXC/GPIO3_12") (pintype "bidirectional"))
    )
    (net (code "244") (name "unconnected-(U_ADC_DMS1-REFN0{slash}GPIO1-Pad6)") (class "Default")
      (node (ref "U_ADC_DMS1") (pin "6") (pinfunction "REFN0/GPIO1_6") (pintype "bidirectional"))
    )
    (net (code "245") (name "unconnected-(U_ADC_DMS1-REFP0{slash}GPIO0-Pad5)") (class "Default")
      (node (ref "U_ADC_DMS1") (pin "5") (pinfunction "REFP0/GPIO0_5") (pintype "bidirectional"))
    )
    (net (code "246") (name "unconnected-(U_ADC_DMS2-AIN2{slash}IEXC{slash}GPIO2-Pad11)") (class "Default")
      (node (ref "U_ADC_DMS2") (pin "11") (pinfunction "AIN2/IEXC/GPIO2_11") (pintype "bidirectional"))
    )
    (net (code "247") (name "unconnected-(U_ADC_DMS2-AIN3{slash}IEXC{slash}GPIO3-Pad12)") (class "Default")
      (node (ref "U_ADC_DMS2") (pin "12") (pinfunction "AIN3/IEXC/GPIO3_12") (pintype "bidirectional"))
    )
    (net (code "248") (name "unconnected-(U_ADC_DMS2-REFN0{slash}GPIO1-Pad6)") (class "Default")
      (node (ref "U_ADC_DMS2") (pin "6") (pinfunction "REFN0/GPIO1_6") (pintype "bidirectional"))
    )
    (net (code "249") (name "unconnected-(U_ADC_DMS2-REFP0{slash}GPIO0-Pad5)") (class "Default")
      (node (ref "U_ADC_DMS2") (pin "5") (pinfunction "REFP0/GPIO0_5") (pintype "bidirectional"))
    )
    (net (code "250") (name "unconnected-(U_ADC_DMS3-AIN2{slash}IEXC{slash}GPIO2-Pad11)") (class "Default")
      (node (ref "U_ADC_DMS3") (pin "11") (pinfunction "AIN2/IEXC/GPIO2_11") (pintype "bidirectional"))
    )
    (net (code "251") (name "unconnected-(U_ADC_DMS3-AIN3{slash}IEXC{slash}GPIO3-Pad12)") (class "Default")
      (node (ref "U_ADC_DMS3") (pin "12") (pinfunction "AIN3/IEXC/GPIO3_12") (pintype "bidirectional"))
    )
    (net (code "252") (name "unconnected-(U_ADC_DMS3-REFN0{slash}GPIO1-Pad6)") (class "Default")
      (node (ref "U_ADC_DMS3") (pin "6") (pinfunction "REFN0/GPIO1_6") (pintype "bidirectional"))
    )
    (net (code "253") (name "unconnected-(U_ADC_DMS3-REFP0{slash}GPIO0-Pad5)") (class "Default")
      (node (ref "U_ADC_DMS3") (pin "5") (pinfunction "REFP0/GPIO0_5") (pintype "bidirectional"))
    )
    (net (code "254") (name "unconnected-(U_ADC_DMS4-AIN2{slash}IEXC{slash}GPIO2-Pad11)") (class "Default")
      (node (ref "U_ADC_DMS4") (pin "11") (pinfunction "AIN2/IEXC/GPIO2_11") (pintype "bidirectional"))
    )
    (net (code "255") (name "unconnected-(U_ADC_DMS4-AIN3{slash}IEXC{slash}GPIO3-Pad12)") (class "Default")
      (node (ref "U_ADC_DMS4") (pin "12") (pinfunction "AIN3/IEXC/GPIO3_12") (pintype "bidirectional"))
    )
    (net (code "256") (name "unconnected-(U_ADC_DMS4-REFN0{slash}GPIO1-Pad6)") (class "Default")
      (node (ref "U_ADC_DMS4") (pin "6") (pinfunction "REFN0/GPIO1_6") (pintype "bidirectional"))
    )
    (net (code "257") (name "unconnected-(U_ADC_DMS4-REFP0{slash}GPIO0-Pad5)") (class "Default")
      (node (ref "U_ADC_DMS4") (pin "5") (pinfunction "REFP0/GPIO0_5") (pintype "bidirectional"))
    )
    (net (code "258") (name "unconnected-(U_ADC_DMS5-AIN2{slash}IEXC{slash}GPIO2-Pad11)") (class "Default")
      (node (ref "U_ADC_DMS5") (pin "11") (pinfunction "AIN2/IEXC/GPIO2_11") (pintype "bidirectional"))
    )
    (net (code "259") (name "unconnected-(U_ADC_DMS5-AIN3{slash}IEXC{slash}GPIO3-Pad12)") (class "Default")
      (node (ref "U_ADC_DMS5") (pin "12") (pinfunction "AIN3/IEXC/GPIO3_12") (pintype "bidirectional"))
    )
    (net (code "260") (name "unconnected-(U_ADC_DMS5-REFN0{slash}GPIO1-Pad6)") (class "Default")
      (node (ref "U_ADC_DMS5") (pin "6") (pinfunction "REFN0/GPIO1_6") (pintype "bidirectional"))
    )
    (net (code "261") (name "unconnected-(U_ADC_DMS5-REFP0{slash}GPIO0-Pad5)") (class "Default")
      (node (ref "U_ADC_DMS5") (pin "5") (pinfunction "REFP0/GPIO0_5") (pintype "bidirectional"))
    )
    (net (code "262") (name "unconnected-(U_ADC_DMS6-AIN2{slash}IEXC{slash}GPIO2-Pad11)") (class "Default")
      (node (ref "U_ADC_DMS6") (pin "11") (pinfunction "AIN2/IEXC/GPIO2_11") (pintype "bidirectional"))
    )
    (net (code "263") (name "unconnected-(U_ADC_DMS6-AIN3{slash}IEXC{slash}GPIO3-Pad12)") (class "Default")
      (node (ref "U_ADC_DMS6") (pin "12") (pinfunction "AIN3/IEXC/GPIO3_12") (pintype "bidirectional"))
    )
    (net (code "264") (name "unconnected-(U_ADC_DMS6-REFN0{slash}GPIO1-Pad6)") (class "Default")
      (node (ref "U_ADC_DMS6") (pin "6") (pinfunction "REFN0/GPIO1_6") (pintype "bidirectional"))
    )
    (net (code "265") (name "unconnected-(U_ADC_DMS6-REFP0{slash}GPIO0-Pad5)") (class "Default")
      (node (ref "U_ADC_DMS6") (pin "5") (pinfunction "REFP0/GPIO0_5") (pintype "bidirectional"))
    )
    (net (code "266") (name "unconnected-(U_CH340G-CTS-Pad9)") (class "Default")
      (node (ref "U_CH340G") (pin "9") (pinfunction "CTS_9") (pintype "bidirectional"))
    )
    (net (code "267") (name "unconnected-(U_CH340G-DCD-Pad12)") (class "Default")
      (node (ref "U_CH340G") (pin "12") (pinfunction "DCD_12") (pintype "bidirectional"))
    )
    (net (code "268") (name "unconnected-(U_CH340G-DSR-Pad10)") (class "Default")
      (node (ref "U_CH340G") (pin "10") (pinfunction "DSR_10") (pintype "bidirectional"))
    )
    (net (code "269") (name "unconnected-(U_CH340G-DTR-Pad13)") (class "Default")
      (node (ref "U_CH340G") (pin "13") (pinfunction "DTR_13") (pintype "bidirectional"))
    )
    (net (code "270") (name "unconnected-(U_CH340G-RI-Pad11)") (class "Default")
      (node (ref "U_CH340G") (pin "11") (pinfunction "RI_11") (pintype "bidirectional"))
    )
    (net (code "271") (name "unconnected-(U_CH340G-RS232-Pad15)") (class "Default")
      (node (ref "U_CH340G") (pin "15") (pinfunction "RS232_15") (pintype "bidirectional"))
    )
    (net (code "272") (name "unconnected-(U_CH340G-RTS-Pad14)") (class "Default")
      (node (ref "U_CH340G") (pin "14") (pinfunction "RTS_14") (pintype "bidirectional"))
    )
    (net (code "273") (name "unconnected-(U_OPTO_2-C2-Pad4)") (class "Default")
      (node (ref "U_OPTO_2") (pin "4") (pinfunction "C2_4") (pintype "bidirectional"))
    )
    (net (code "274") (name "unconnected-(U_STM32F779-DSI_CKN-Pad124)") (class "Default")
      (node (ref "U_STM32F779") (pin "124") (pinfunction "DSI_CKN_124") (pintype "bidirectional"))
    )
    (net (code "275") (name "unconnected-(U_STM32F779-DSI_CKP-Pad123)") (class "Default")
      (node (ref "U_STM32F779") (pin "123") (pinfunction "DSI_CKP_123") (pintype "bidirectional"))
    )
    (net (code "276") (name "unconnected-(U_STM32F779-DSI_D0N-Pad121)") (class "Default")
      (node (ref "U_STM32F779") (pin "121") (pinfunction "DSI_D0N_121") (pintype "bidirectional"))
    )
    (net (code "277") (name "unconnected-(U_STM32F779-DSI_D0P-Pad120)") (class "Default")
      (node (ref "U_STM32F779") (pin "120") (pinfunction "DSI_D0P_120") (pintype "bidirectional"))
    )
    (net (code "278") (name "unconnected-(U_STM32F779-DSI_D1N-Pad127)") (class "Default")
      (node (ref "U_STM32F779") (pin "127") (pinfunction "DSI_D1N_127") (pintype "bidirectional"))
    )
    (net (code "279") (name "unconnected-(U_STM32F779-DSI_D1P-Pad126)") (class "Default")
      (node (ref "U_STM32F779") (pin "126") (pinfunction "DSI_D1P_126") (pintype "bidirectional"))
    )
    (net (code "280") (name "unconnected-(U_STM32F779-PA1-Pad44)") (class "Default")
      (node (ref "U_STM32F779") (pin "44") (pinfunction "PA1_44") (pintype "bidirectional"))
    )
    (net (code "281") (name "unconnected-(U_STM32F779-PA2-Pad45)") (class "Default")
      (node (ref "U_STM32F779") (pin "45") (pinfunction "PA2_45") (pintype "bidirectional"))
    )
    (net (code "282") (name "unconnected-(U_STM32F779-PA4-Pad53)") (class "Default")
      (node (ref "U_STM32F779") (pin "53") (pinfunction "PA4_53") (pintype "bidirectional"))
    )
    (net (code "283") (name "unconnected-(U_STM32F779-PB0-Pad61)") (class "Default")
      (node (ref "U_STM32F779") (pin "61") (pinfunction "PB0_61") (pintype "bidirectional"))
    )
    (net (code "284") (name "unconnected-(U_STM32F779-PB1-Pad62)") (class "Default")
      (node (ref "U_STM32F779") (pin "62") (pinfunction "PB1_62") (pintype "bidirectional"))
    )
    (net (code "285") (name "unconnected-(U_STM32F779-PB5-Pad194)") (class "Default")
      (node (ref "U_STM32F779") (pin "194") (pinfunction "PB5_194") (pintype "bidirectional"))
    )
    (net (code "286") (name "unconnected-(U_STM32F779-PB6-Pad195)") (class "Default")
      (node (ref "U_STM32F779") (pin "195") (pinfunction "PB6_195") (pintype "bidirectional"))
    )
    (net (code "287") (name "unconnected-(U_STM32F779-PB7-Pad196)") (class "Default")
      (node (ref "U_STM32F779") (pin "196") (pinfunction "PB7_196") (pintype "bidirectional"))
    )
    (net (code "288") (name "unconnected-(U_STM32F779-PB8-Pad198)") (class "Default")
      (node (ref "U_STM32F779") (pin "198") (pinfunction "PB8_198") (pintype "bidirectional"))
    )
    (net (code "289") (name "unconnected-(U_STM32F779-PB9-Pad199)") (class "Default")
      (node (ref "U_STM32F779") (pin "199") (pinfunction "PB9_199") (pintype "bidirectional"))
    )
    (net (code "290") (name "unconnected-(U_STM32F779-PB10-Pad90)") (class "Default")
      (node (ref "U_STM32F779") (pin "90") (pinfunction "PB10_90") (pintype "bidirectional"))
    )
    (net (code "291") (name "unconnected-(U_STM32F779-PB11-Pad91)") (class "Default")
      (node (ref "U_STM32F779") (pin "91") (pinfunction "PB11_91") (pintype "bidirectional"))
    )
    (net (code "292") (name "unconnected-(U_STM32F779-PC4-Pad57)") (class "Default")
      (node (ref "U_STM32F779") (pin "57") (pinfunction "PC4_57") (pintype "bidirectional"))
    )
    (net (code "293") (name "unconnected-(U_STM32F779-PC5-Pad58)") (class "Default")
      (node (ref "U_STM32F779") (pin "58") (pinfunction "PC5_58") (pintype "bidirectional"))
    )
    (net (code "294") (name "unconnected-(U_STM32F779-PC6-Pad138)") (class "Default")
      (node (ref "U_STM32F779") (pin "138") (pinfunction "PC6_138") (pintype "bidirectional"))
    )
    (net (code "295") (name "unconnected-(U_STM32F779-PC7-Pad139)") (class "Default")
      (node (ref "U_STM32F779") (pin "139") (pinfunction "PC7_139") (pintype "bidirectional"))
    )
    (net (code "296") (name "unconnected-(U_STM32F779-PC8-Pad140)") (class "Default")
      (node (ref "U_STM32F779") (pin "140") (pinfunction "PC8_140") (pintype "bidirectional"))
    )
    (net (code "297") (name "unconnected-(U_STM32F779-PC9-Pad141)") (class "Default")
      (node (ref "U_STM32F779") (pin "141") (pinfunction "PC9_141") (pintype "bidirectional"))
    )
    (net (code "298") (name "unconnected-(U_STM32F779-PC13-Pad8)") (class "Default")
      (node (ref "U_STM32F779") (pin "8") (pinfunction "PC13_8") (pintype "bidirectional"))
    )
    (net (code "299") (name "unconnected-(U_STM32F779-PC14-Pad9)") (class "Default")
      (node (ref "U_STM32F779") (pin "9") (pinfunction "PC14_9") (pintype "bidirectional"))
    )
    (net (code "300") (name "unconnected-(U_STM32F779-PC15-Pad10)") (class "Default")
      (node (ref "U_STM32F779") (pin "10") (pinfunction "PC15_10") (pintype "bidirectional"))
    )
    (net (code "301") (name "unconnected-(U_STM32F779-PD0-Pad164)") (class "Default")
      (node (ref "U_STM32F779") (pin "164") (pinfunction "PD0_164") (pintype "bidirectional"))
    )
    (net (code "302") (name "unconnected-(U_STM32F779-PD1-Pad165)") (class "Default")
      (node (ref "U_STM32F779") (pin "165") (pinfunction "PD1_165") (pintype "bidirectional"))
    )
    (net (code "303") (name "unconnected-(U_STM32F779-PD3-Pad167)") (class "Default")
      (node (ref "U_STM32F779") (pin "167") (pinfunction "PD3_167") (pintype "bidirectional"))
    )
    (net (code "304") (name "unconnected-(U_STM32F779-PD4-Pad168)") (class "Default")
      (node (ref "U_STM32F779") (pin "168") (pinfunction "PD4_168") (pintype "bidirectional"))
    )
    (net (code "305") (name "unconnected-(U_STM32F779-PD5-Pad169)") (class "Default")
      (node (ref "U_STM32F779") (pin "169") (pinfunction "PD5_169") (pintype "bidirectional"))
    )
    (net (code "306") (name "unconnected-(U_STM32F779-PD6-Pad172)") (class "Default")
      (node (ref "U_STM32F779") (pin "172") (pinfunction "PD6_172") (pintype "bidirectional"))
    )
    (net (code "307") (name "unconnected-(U_STM32F779-PD7-Pad173)") (class "Default")
      (node (ref "U_STM32F779") (pin "173") (pinfunction "PD7_173") (pintype "bidirectional"))
    )
    (net (code "308") (name "unconnected-(U_STM32F779-PE3-Pad2)") (class "Default")
      (node (ref "U_STM32F779") (pin "2") (pinfunction "PE3_2") (pintype "bidirectional"))
    )
    (net (code "309") (name "unconnected-(U_STM32F779-PE4-Pad3)") (class "Default")
      (node (ref "U_STM32F779") (pin "3") (pinfunction "PE4_3") (pintype "bidirectional"))
    )
    (net (code "310") (name "unconnected-(U_STM32F779-PE8-Pad80)") (class "Default")
      (node (ref "U_STM32F779") (pin "80") (pinfunction "PE8_80") (pintype "bidirectional"))
    )
    (net (code "311") (name "unconnected-(U_STM32F779-PE9-Pad81)") (class "Default")
      (node (ref "U_STM32F779") (pin "81") (pinfunction "PE9_81") (pintype "bidirectional"))
    )
    (net (code "312") (name "unconnected-(U_STM32F779-PE10-Pad84)") (class "Default")
      (node (ref "U_STM32F779") (pin "84") (pinfunction "PE10_84") (pintype "bidirectional"))
    )
    (net (code "313") (name "unconnected-(U_STM32F779-PE11-Pad85)") (class "Default")
      (node (ref "U_STM32F779") (pin "85") (pinfunction "PE11_85") (pintype "bidirectional"))
    )
    (net (code "314") (name "unconnected-(U_STM32F779-PE12-Pad86)") (class "Default")
      (node (ref "U_STM32F779") (pin "86") (pinfunction "PE12_86") (pintype "bidirectional"))
    )
    (net (code "315") (name "unconnected-(U_STM32F779-PE13-Pad87)") (class "Default")
      (node (ref "U_STM32F779") (pin "87") (pinfunction "PE13_87") (pintype "bidirectional"))
    )
    (net (code "316") (name "unconnected-(U_STM32F779-PE14-Pad88)") (class "Default")
      (node (ref "U_STM32F779") (pin "88") (pinfunction "PE14_88") (pintype "bidirectional"))
    )
    (net (code "317") (name "unconnected-(U_STM32F779-PE15-Pad89)") (class "Default")
      (node (ref "U_STM32F779") (pin "89") (pinfunction "PE15_89") (pintype "bidirectional"))
    )
    (net (code "318") (name "unconnected-(U_STM32F779-PF0-Pad16)") (class "Default")
      (node (ref "U_STM32F779") (pin "16") (pinfunction "PF0_16") (pintype "bidirectional"))
    )
    (net (code "319") (name "unconnected-(U_STM32F779-PF1-Pad17)") (class "Default")
      (node (ref "U_STM32F779") (pin "17") (pinfunction "PF1_17") (pintype "bidirectional"))
    )
    (net (code "320") (name "unconnected-(U_STM32F779-PF2-Pad18)") (class "Default")
      (node (ref "U_STM32F779") (pin "18") (pinfunction "PF2_18") (pintype "bidirectional"))
    )
    (net (code "321") (name "unconnected-(U_STM32F779-PF6-Pad27)") (class "Default")
      (node (ref "U_STM32F779") (pin "27") (pinfunction "PF6_27") (pintype "bidirectional"))
    )
    (net (code "322") (name "unconnected-(U_STM32F779-PF11-Pad70)") (class "Default")
      (node (ref "U_STM32F779") (pin "70") (pinfunction "PF11_70") (pintype "bidirectional"))
    )
    (net (code "323") (name "unconnected-(U_STM32F779-PF12-Pad71)") (class "Default")
      (node (ref "U_STM32F779") (pin "71") (pinfunction "PF12_71") (pintype "bidirectional"))
    )
    (net (code "324") (name "unconnected-(U_STM32F779-PG3-Pad130)") (class "Default")
      (node (ref "U_STM32F779") (pin "130") (pinfunction "PG3_130") (pintype "bidirectional"))
    )
    (net (code "325") (name "unconnected-(U_STM32F779-PG5-Pad132)") (class "Default")
      (node (ref "U_STM32F779") (pin "132") (pinfunction "PG5_132") (pintype "bidirectional"))
    )
    (net (code "326") (name "unconnected-(U_STM32F779-PG6-Pad133)") (class "Default")
      (node (ref "U_STM32F779") (pin "133") (pinfunction "PG6_133") (pintype "bidirectional"))
    )
    (net (code "327") (name "unconnected-(U_STM32F779-PG7-Pad134)") (class "Default")
      (node (ref "U_STM32F779") (pin "134") (pinfunction "PG7_134") (pintype "bidirectional"))
    )
    (net (code "328") (name "unconnected-(U_STM32F779-PG8-Pad135)") (class "Default")
      (node (ref "U_STM32F779") (pin "135") (pinfunction "PG8_135") (pintype "bidirectional"))
    )
    (net (code "329") (name "unconnected-(U_STM32F779-PG9-Pad178)") (class "Default")
      (node (ref "U_STM32F779") (pin "178") (pinfunction "PG9_178") (pintype "bidirectional"))
    )
    (net (code "330") (name "unconnected-(U_STM32F779-PG10-Pad179)") (class "Default")
      (node (ref "U_STM32F779") (pin "179") (pinfunction "PG10_179") (pintype "bidirectional"))
    )
    (net (code "331") (name "unconnected-(U_STM32F779-PG11-Pad180)") (class "Default")
      (node (ref "U_STM32F779") (pin "180") (pinfunction "PG11_180") (pintype "bidirectional"))
    )
    (net (code "332") (name "unconnected-(U_STM32F779-PG12-Pad181)") (class "Default")
      (node (ref "U_STM32F779") (pin "181") (pinfunction "PG12_181") (pintype "bidirectional"))
    )
    (net (code "333") (name "unconnected-(U_STM32F779-PG13-Pad182)") (class "Default")
      (node (ref "U_STM32F779") (pin "182") (pinfunction "PG13_182") (pintype "bidirectional"))
    )
    (net (code "334") (name "unconnected-(U_STM32F779-PG14-Pad183)") (class "Default")
      (node (ref "U_STM32F779") (pin "183") (pinfunction "PG14_183") (pintype "bidirectional"))
    )
    (net (code "335") (name "unconnected-(U_STM32F779-PG15-Pad191)") (class "Default")
      (node (ref "U_STM32F779") (pin "191") (pinfunction "PG15_191") (pintype "bidirectional"))
    )
    (net (code "336") (name "unconnected-(U_STM32F779-PH0-Pad32)") (class "Default")
      (node (ref "U_STM32F779") (pin "32") (pinfunction "PH0_32") (pintype "bidirectional"))
    )
    (net (code "337") (name "unconnected-(U_STM32F779-PH1-Pad33)") (class "Default")
      (node (ref "U_STM32F779") (pin "33") (pinfunction "PH1_33") (pintype "bidirectional"))
    )
    (net (code "338") (name "unconnected-(U_STM32F779-PH2-Pad46)") (class "Default")
      (node (ref "U_STM32F779") (pin "46") (pinfunction "PH2_46") (pintype "bidirectional"))
    )
    (net (code "339") (name "unconnected-(U_STM32F779-PH6-Pad96)") (class "Default")
      (node (ref "U_STM32F779") (pin "96") (pinfunction "PH6_96") (pintype "bidirectional"))
    )
    (net (code "340") (name "unconnected-(U_STM32F779-PH7-Pad97)") (class "Default")
      (node (ref "U_STM32F779") (pin "97") (pinfunction "PH7_97") (pintype "bidirectional"))
    )
    (net (code "341") (name "unconnected-(U_STM32F779-PH8-Pad98)") (class "Default")
      (node (ref "U_STM32F779") (pin "98") (pinfunction "PH8_98") (pintype "bidirectional"))
    )
    (net (code "342") (name "unconnected-(U_STM32F779-PH13-Pad151)") (class "Default")
      (node (ref "U_STM32F779") (pin "151") (pinfunction "PH13_151") (pintype "bidirectional"))
    )
    (net (code "343") (name "unconnected-(U_STM32F779-PH14-Pad152)") (class "Default")
      (node (ref "U_STM32F779") (pin "152") (pinfunction "PH14_152") (pintype "bidirectional"))
    )
    (net (code "344") (name "unconnected-(U_STM32F779-PH15-Pad153)") (class "Default")
      (node (ref "U_STM32F779") (pin "153") (pinfunction "PH15_153") (pintype "bidirectional"))
    )
    (net (code "345") (name "unconnected-(U_STM32F779-PI0-Pad154)") (class "Default")
      (node (ref "U_STM32F779") (pin "154") (pinfunction "PI0_154") (pintype "bidirectional"))
    )
    (net (code "346") (name "unconnected-(U_STM32F779-PI1-Pad155)") (class "Default")
      (node (ref "U_STM32F779") (pin "155") (pinfunction "PI1_155") (pintype "bidirectional"))
    )
    (net (code "347") (name "unconnected-(U_STM32F779-PI2-Pad156)") (class "Default")
      (node (ref "U_STM32F779") (pin "156") (pinfunction "PI2_156") (pintype "bidirectional"))
    )
    (net (code "348") (name "unconnected-(U_STM32F779-PI4-Pad205)") (class "Default")
      (node (ref "U_STM32F779") (pin "205") (pinfunction "PI4_205") (pintype "bidirectional"))
    )
    (net (code "349") (name "unconnected-(U_STM32F779-PI10-Pad12)") (class "Default")
      (node (ref "U_STM32F779") (pin "12") (pinfunction "PI10_12") (pintype "bidirectional"))
    )
    (net (code "350") (name "unconnected-(U_STM32F779-PI11-Pad13)") (class "Default")
      (node (ref "U_STM32F779") (pin "13") (pinfunction "PI11_13") (pintype "bidirectional"))
    )
    (net (code "351") (name "unconnected-(U_STM32F779-PI12-Pad19)") (class "Default")
      (node (ref "U_STM32F779") (pin "19") (pinfunction "PI12_19") (pintype "bidirectional"))
    )
    (net (code "352") (name "unconnected-(U_STM32F779-PI13-Pad20)") (class "Default")
      (node (ref "U_STM32F779") (pin "20") (pinfunction "PI13_20") (pintype "bidirectional"))
    )
    (net (code "353") (name "unconnected-(U_STM32F779-PI15-Pad64)") (class "Default")
      (node (ref "U_STM32F779") (pin "64") (pinfunction "PI15_64") (pintype "bidirectional"))
    )
    (net (code "354") (name "unconnected-(U_STM32F779-PJ0-Pad65)") (class "Default")
      (node (ref "U_STM32F779") (pin "65") (pinfunction "PJ0_65") (pintype "bidirectional"))
    )
    (net (code "355") (name "unconnected-(U_STM32F779-PJ1-Pad66)") (class "Default")
      (node (ref "U_STM32F779") (pin "66") (pinfunction "PJ1_66") (pintype "bidirectional"))
    )
    (net (code "356") (name "unconnected-(U_STM32F779-PJ2-Pad67)") (class "Default")
      (node (ref "U_STM32F779") (pin "67") (pinfunction "PJ2_67") (pintype "bidirectional"))
    )
    (net (code "357") (name "unconnected-(U_STM32F779-PJ3-Pad68)") (class "Default")
      (node (ref "U_STM32F779") (pin "68") (pinfunction "PJ3_68") (pintype "bidirectional"))
    )
    (net (code "358") (name "unconnected-(U_STM32F779-PJ4-Pad69)") (class "Default")
      (node (ref "U_STM32F779") (pin "69") (pinfunction "PJ4_69") (pintype "bidirectional"))
    )
    (net (code "359") (name "unconnected-(U_STM32F779-PJ5-Pad95)") (class "Default")
      (node (ref "U_STM32F779") (pin "95") (pinfunction "PJ5_95") (pintype "bidirectional"))
    )
    (net (code "360") (name "unconnected-(U_STM32F779-PJ12-Pad174)") (class "Default")
      (node (ref "U_STM32F779") (pin "174") (pinfunction "PJ12_174") (pintype "bidirectional"))
    )
    (net (code "361") (name "unconnected-(U_STM32F779-PK3-Pad186)") (class "Default")
      (node (ref "U_STM32F779") (pin "186") (pinfunction "PK3_186") (pintype "bidirectional"))
    )
    (net (code "362") (name "unconnected-(U_STM32F779-PK4-Pad187)") (class "Default")
      (node (ref "U_STM32F779") (pin "187") (pinfunction "PK4_187") (pintype "bidirectional"))
    )
    (net (code "363") (name "unconnected-(U_STM32F779-PK5-Pad188)") (class "Default")
      (node (ref "U_STM32F779") (pin "188") (pinfunction "PK5_188") (pintype "bidirectional"))
    )
    (net (code "364") (name "unconnected-(U_STM32F779-PK6-Pad189)") (class "Default")
      (node (ref "U_STM32F779") (pin "189") (pinfunction "PK6_189") (pintype "bidirectional"))
    )
    (net (code "365") (name "unconnected-(U_STM32F779-PK7-Pad190)") (class "Default")
      (node (ref "U_STM32F779") (pin "190") (pinfunction "PK7_190") (pintype "bidirectional"))
    )
    (net (code "366") (name "unconnected-(U_TRACODCDC-RMT_ON_OFF-Pad6)") (class "Default")
      (node (ref "U_TRACODCDC") (pin "6") (pinfunction "RMT_ON_OFF_6") (pintype "input"))
    )
    (net (code "367") (name "unconnected-(X_GPIO-B3-PadP$B3)") (class "Default")
      (node (ref "X_GPIO") (pin "P$B3") (pinfunction "B3_P$B3") (pintype "passive"))
    )
    (net (code "368") (name "unconnected-(X_GPIO-B4-PadP$B4)") (class "Default")
      (node (ref "X_GPIO") (pin "P$B4") (pinfunction "B4_P$B4") (pintype "passive"))
    )
    (net (code "369") (name "unconnected-(X_GPIO-B5-PadP$B5)") (class "Default")
      (node (ref "X_GPIO") (pin "P$B5") (pinfunction "B5_P$B5") (pintype "passive"))
    )
    (net (code "370") (name "unconnected-(X_GPIO-B6-PadP$B6)") (class "Default")
      (node (ref "X_GPIO") (pin "P$B6") (pinfunction "B6_P$B6") (pintype "passive"))
    )
    (net (code "371") (name "unconnected-(X_GPIO-B7-PadP$B7)") (class "Default")
      (node (ref "X_GPIO") (pin "P$B7") (pinfunction "B7_P$B7") (pintype "passive"))
    )
    (net (code "372") (name "unconnected-(X_GPIO-B8-PadP$B8)") (class "Default")
      (node (ref "X_GPIO") (pin "P$B8") (pinfunction "B8_P$B8") (pintype "passive"))
    )
    (net (code "373") (name "unconnected-(X_GPIO-B9-PadP$B9)") (class "Default")
      (node (ref "X_GPIO") (pin "P$B9") (pinfunction "B9_P$B9") (pintype "passive"))
    )
    (net (code "374") (name "unconnected-(X_GPIO-B10-PadP$B10)") (class "Default")
      (node (ref "X_GPIO") (pin "P$B10") (pinfunction "B10_P$B10") (pintype "passive"))
    )
    (net (code "375") (name "unconnected-(X_MIRROR-A11-PadP$A11)") (class "Default")
      (node (ref "X_MIRROR") (pin "P$A11") (pinfunction "A11_P$A11") (pintype "passive"))
    )
    (net (code "376") (name "unconnected-(X_MIRROR-A12-PadP$A12)") (class "Default")
      (node (ref "X_MIRROR") (pin "P$A12") (pinfunction "A12_P$A12") (pintype "passive"))
    )
    (net (code "377") (name "unconnected-(X_MIRROR-A13-PadP$A13)") (class "Default")
      (node (ref "X_MIRROR") (pin "P$A13") (pinfunction "A13_P$A13") (pintype "passive"))
    )
    (net (code "378") (name "unconnected-(X_MIRROR1-A1-PadP$A1)") (class "Default")
      (node (ref "X_MIRROR1") (pin "P$A1") (pinfunction "A1_P$A1") (pintype "passive"))
    )
    (net (code "379") (name "unconnected-(X_MIRROR1-A2-PadP$A2)") (class "Default")
      (node (ref "X_MIRROR1") (pin "P$A2") (pinfunction "A2_P$A2") (pintype "passive"))
    )
    (net (code "380") (name "unconnected-(X_MIRROR1-A3-PadP$A3)") (class "Default")
      (node (ref "X_MIRROR1") (pin "P$A3") (pinfunction "A3_P$A3") (pintype "passive"))
    )
    (net (code "381") (name "unconnected-(X_PROG-Pad2)") (class "Default")
      (node (ref "X_PROG") (pin "2") (pinfunction "2_2") (pintype "passive"))
    )
    (net (code "382") (name "unconnected-(X_PROG-Pad11)") (class "Default")
      (node (ref "X_PROG") (pin "11") (pinfunction "11_11") (pintype "passive"))
    )
    (net (code "383") (name "unconnected-(X_PROG-Pad17)") (class "Default")
      (node (ref "X_PROG") (pin "17") (pinfunction "17_17") (pintype "passive"))
    )
    (net (code "384") (name "unconnected-(X_PROG-Pad19)") (class "Default")
      (node (ref "X_PROG") (pin "19") (pinfunction "19_19") (pintype "passive"))
    )
    (net (code "385") (name "unconnected-(X_RXSM-DAPI-A7-PadP$A7)") (class "Default")
      (node (ref "X_RXSM-DAPI") (pin "P$A7") (pinfunction "A7_P$A7") (pintype "passive"))
    )
    (net (code "386") (name "unconnected-(X_RXSM-DAPI-A8-PadP$A8)") (class "Default")
      (node (ref "X_RXSM-DAPI") (pin "P$A8") (pinfunction "A8_P$A8") (pintype "passive"))
    )
    (net (code "387") (name "unconnected-(X_RXSM-DAPI-B7-PadP$B7)") (class "Default")
      (node (ref "X_RXSM-DAPI") (pin "P$B7") (pinfunction "B7_P$B7") (pintype "passive"))
    )
    (net (code "388") (name "unconnected-(X_RXSM-DAPI-B8-PadP$B8)") (class "Default")
      (node (ref "X_RXSM-DAPI") (pin "P$B8") (pinfunction "B8_P$B8") (pintype "passive"))
    )
    (net (code "389") (name "~{CS}_DMS1") (class "Default")
      (node (ref "R3") (pin "2") (pinfunction "2_2") (pintype "passive"))
      (node (ref "U_STM32F779") (pin "74") (pinfunction "PF13_74") (pintype "bidirectional"))
    )
    (net (code "390") (name "~{CS}_DMS2") (class "Default")
      (node (ref "R31") (pin "2") (pinfunction "2_2") (pintype "passive"))
      (node (ref "U_STM32F779") (pin "75") (pinfunction "PF14_75") (pintype "bidirectional"))
    )
    (net (code "391") (name "~{CS}_DMS3") (class "Default")
      (node (ref "R38") (pin "2") (pinfunction "2_2") (pintype "passive"))
      (node (ref "U_STM32F779") (pin "76") (pinfunction "PF15_76") (pintype "bidirectional"))
    )
    (net (code "392") (name "~{CS}_DMS4") (class "Default")
      (node (ref "R45") (pin "2") (pinfunction "2_2") (pintype "passive"))
      (node (ref "U_STM32F779") (pin "77") (pinfunction "PG0_77") (pintype "bidirectional"))
    )
    (net (code "393") (name "~{CS}_DMS5") (class "Default")
      (node (ref "R52") (pin "2") (pinfunction "2_2") (pintype "passive"))
      (node (ref "U_STM32F779") (pin "78") (pinfunction "PG1_78") (pintype "bidirectional"))
    )
    (net (code "394") (name "~{CS}_DMS6") (class "Default")
      (node (ref "R59") (pin "2") (pinfunction "2_2") (pintype "passive"))
      (node (ref "U_STM32F779") (pin "79") (pinfunction "PE7_79") (pintype "bidirectional"))
    )
    (net (code "395") (name "~{CS}_PT1") (class "Default")
      (node (ref "RN_B_PT1") (pin "7") (pinfunction "2_7") (pintype "passive"))
      (node (ref "U_STM32F779") (pin "117") (pinfunction "PD15_117") (pintype "bidirectional"))
    )
    (net (code "396") (name "~{CS}_PT2") (class "Default")
      (node (ref "RN_B_PT2") (pin "7") (pinfunction "2_7") (pintype "passive"))
      (node (ref "U_STM32F779") (pin "116") (pinfunction "PD14_116") (pintype "bidirectional"))
    )
    (net (code "397") (name "~{CS}_PT3") (class "Default")
      (node (ref "RN_B_PT3") (pin "7") (pinfunction "2_7") (pintype "passive"))
      (node (ref "U_STM32F779") (pin "108") (pinfunction "PD8_108") (pintype "bidirectional"))
    )
    (net (code "398") (name "~{DRDY}_DMS1") (class "Default")
      (node (ref "RN_DMS1") (pin "5") (pinfunction "2_5") (pintype "passive"))
      (node (ref "U_STM32F779") (pin "131") (pinfunction "PG4_131") (pintype "bidirectional"))
    )
    (net (code "399") (name "~{DRDY}_DMS2") (class "Default")
      (node (ref "RN_DMS2") (pin "5") (pinfunction "2_5") (pintype "passive"))
      (node (ref "U_STM32F779") (pin "142") (pinfunction "PA8_142") (pintype "bidirectional"))
    )
    (net (code "400") (name "~{DRDY}_DMS3") (class "Default")
      (node (ref "RN_DMS3") (pin "5") (pinfunction "2_5") (pintype "passive"))
      (node (ref "U_STM32F779") (pin "143") (pinfunction "PA9_143") (pintype "bidirectional"))
    )
    (net (code "401") (name "~{DRDY}_DMS4") (class "Default")
      (node (ref "RN_DMS4") (pin "5") (pinfunction "2_5") (pintype "passive"))
      (node (ref "U_STM32F779") (pin "144") (pinfunction "PA10_144") (pintype "bidirectional"))
    )
    (net (code "402") (name "~{DRDY}_DMS5") (class "Default")
      (node (ref "RN_DMS5") (pin "5") (pinfunction "2_5") (pintype "passive"))
      (node (ref "U_STM32F779") (pin "145") (pinfunction "PA11_145") (pintype "bidirectional"))
    )
    (net (code "403") (name "~{DRDY}_DMS6") (class "Default")
      (node (ref "RN_DMS6") (pin "5") (pinfunction "2_5") (pintype "passive"))
      (node (ref "U_STM32F779") (pin "146") (pinfunction "PA12_146") (pintype "bidirectional"))
    )
    (net (code "404") (name "~{DRDY}_PT1") (class "Default")
      (node (ref "RN_B_PT1") (pin "8") (pinfunction "2_8") (pintype "passive"))
      (node (ref "U_STM32F779") (pin "177") (pinfunction "PJ15_177") (pintype "bidirectional"))
    )
    (net (code "405") (name "~{DRDY}_PT2") (class "Default")
      (node (ref "RN_B_PT2") (pin "8") (pinfunction "2_8") (pintype "passive"))
      (node (ref "U_STM32F779") (pin "176") (pinfunction "PJ14_176") (pintype "bidirectional"))
    )
    (net (code "406") (name "~{DRDY}_PT3") (class "Default")
      (node (ref "RN_B_PT3") (pin "8") (pinfunction "2_8") (pintype "passive"))
      (node (ref "U_STM32F779") (pin "175") (pinfunction "PJ13_175") (pintype "bidirectional"))
    )
  )
)
